# blades_v40.net
KiCad netlist of a schematic drawn in EAGLE
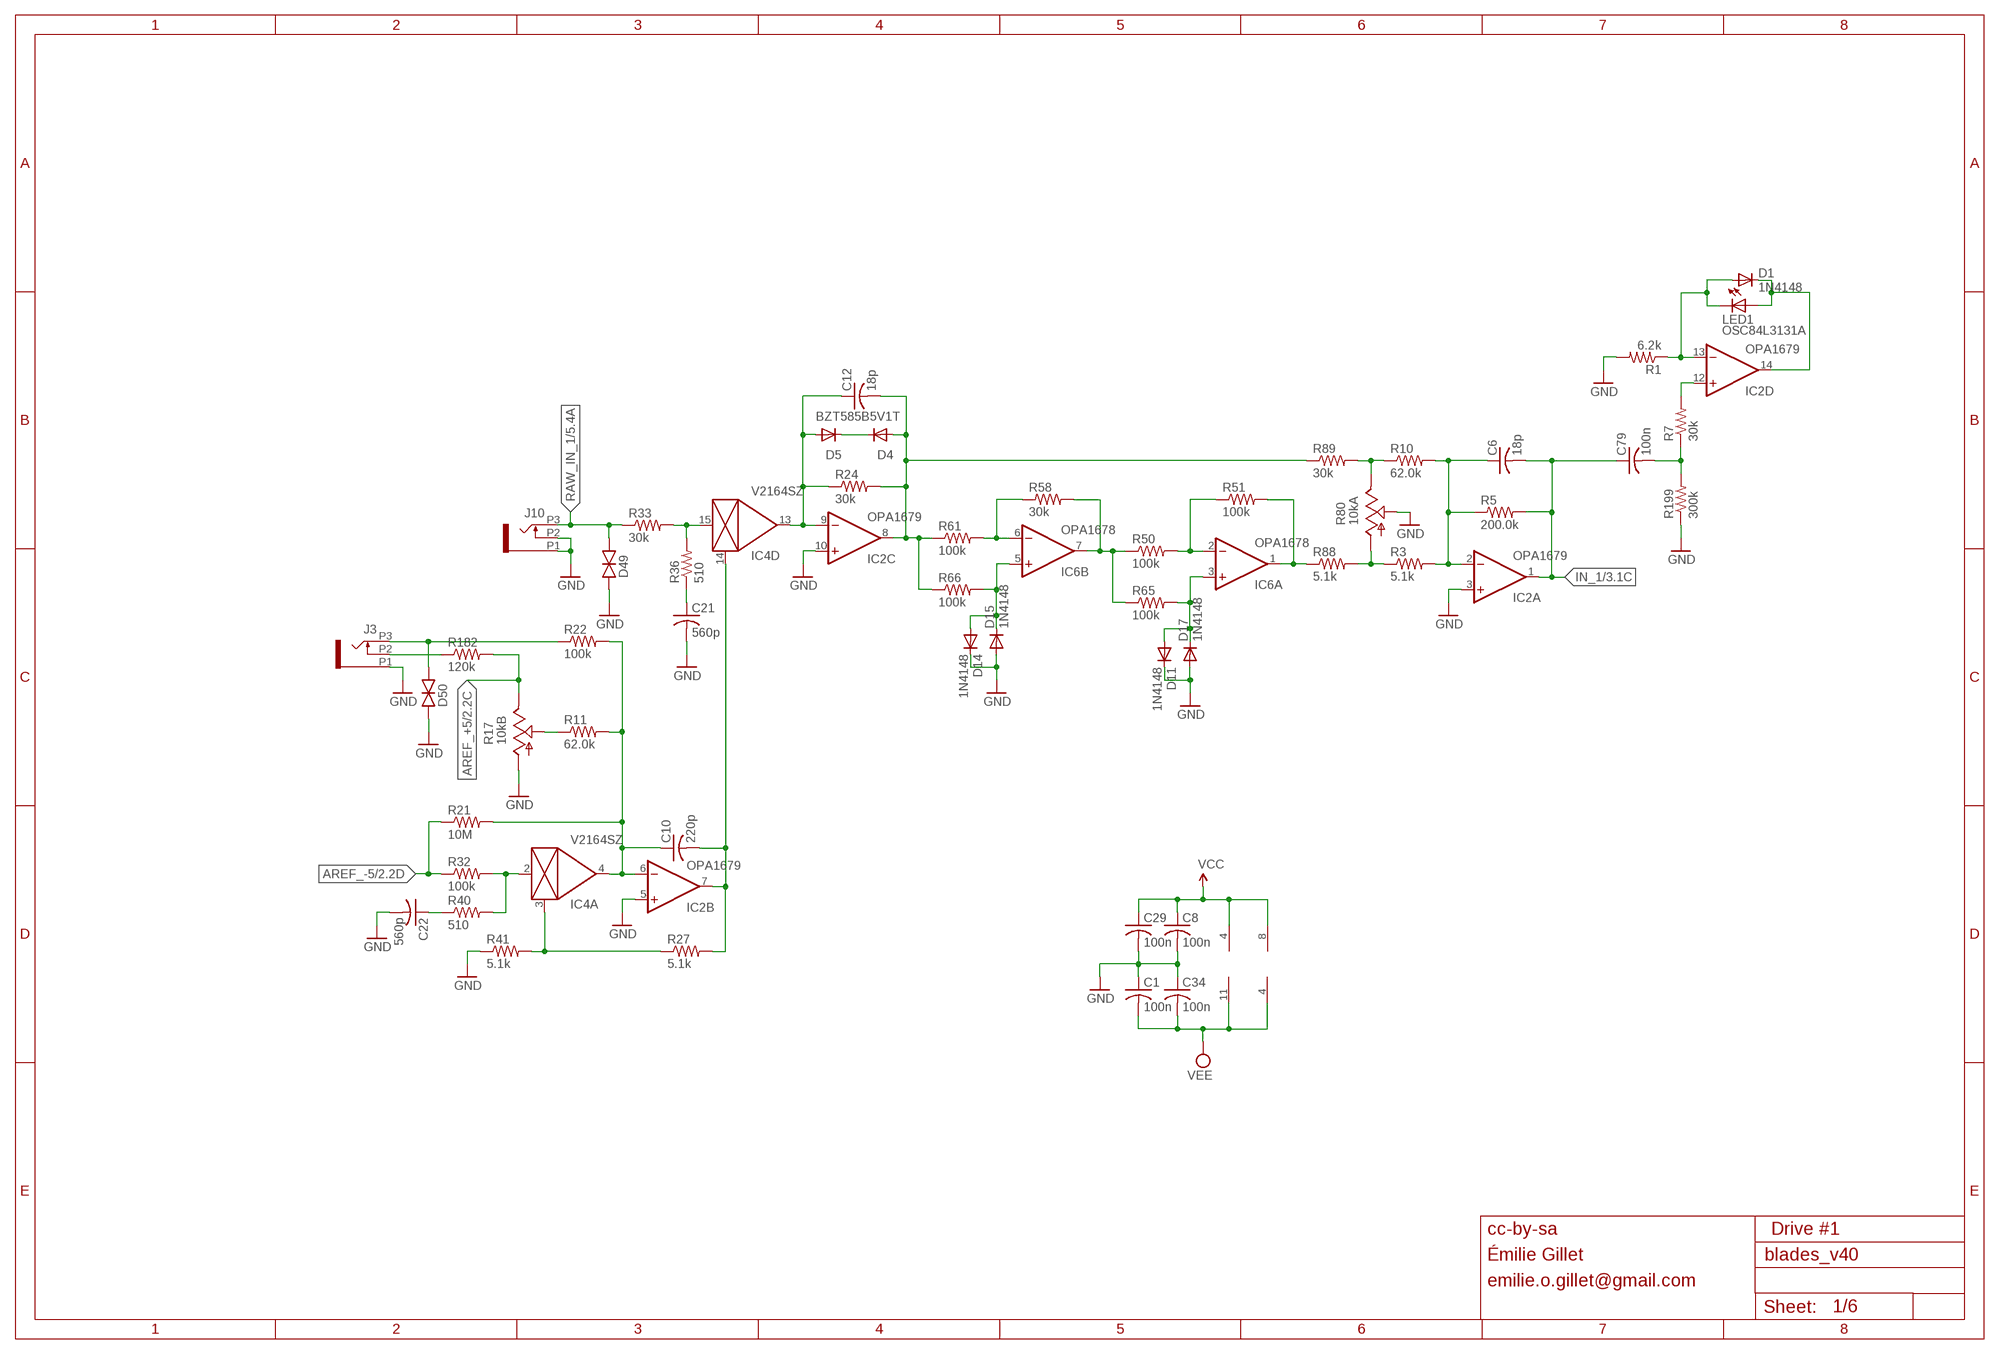
[diagram p0: schematic, sheet 1]
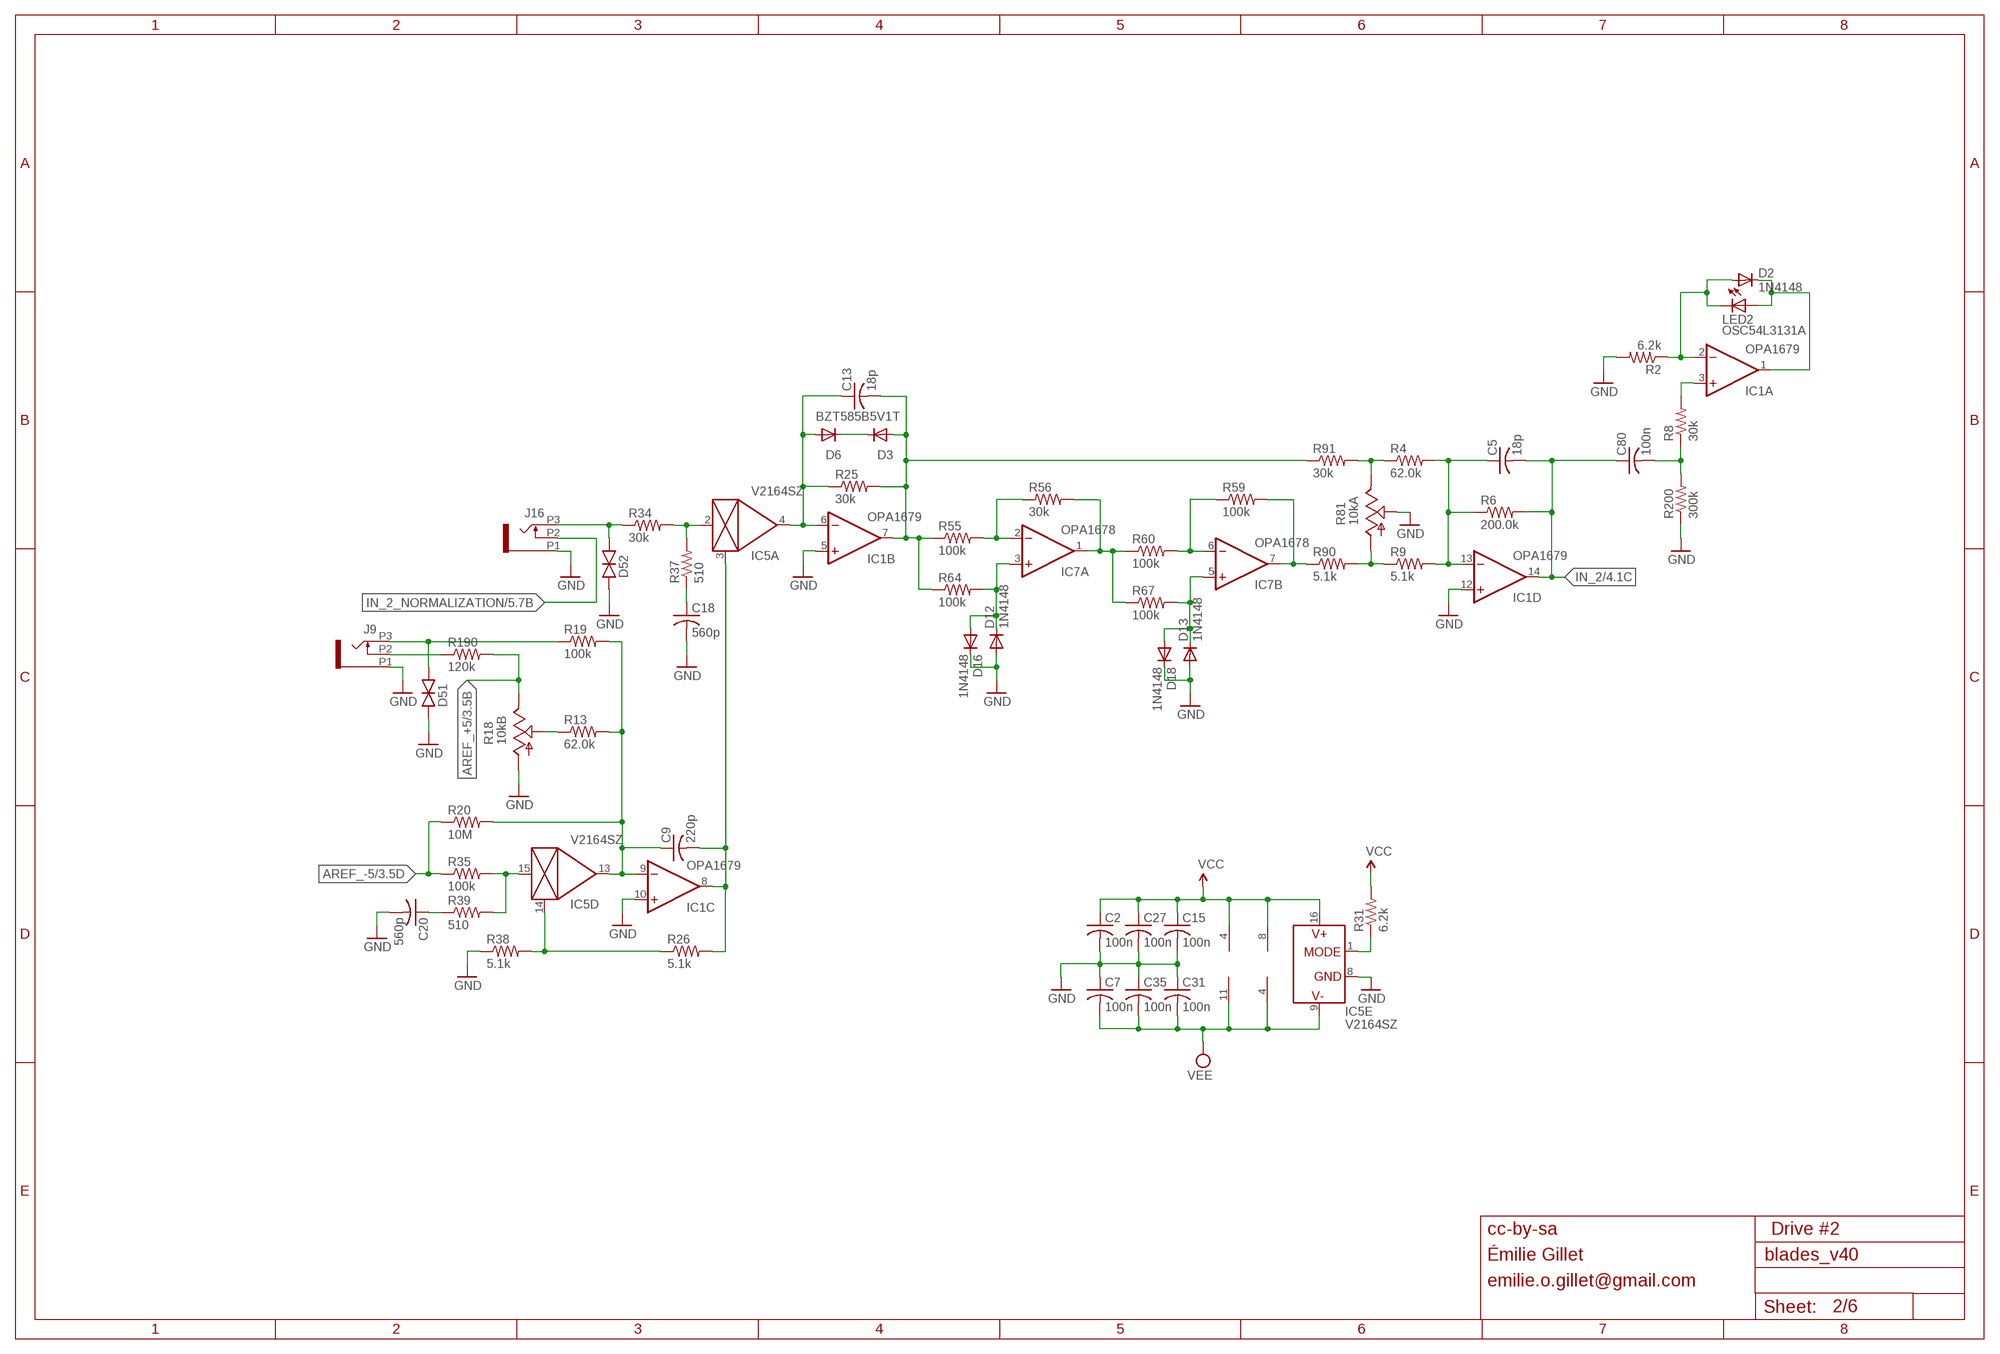
[diagram p1: schematic, sheet 2]
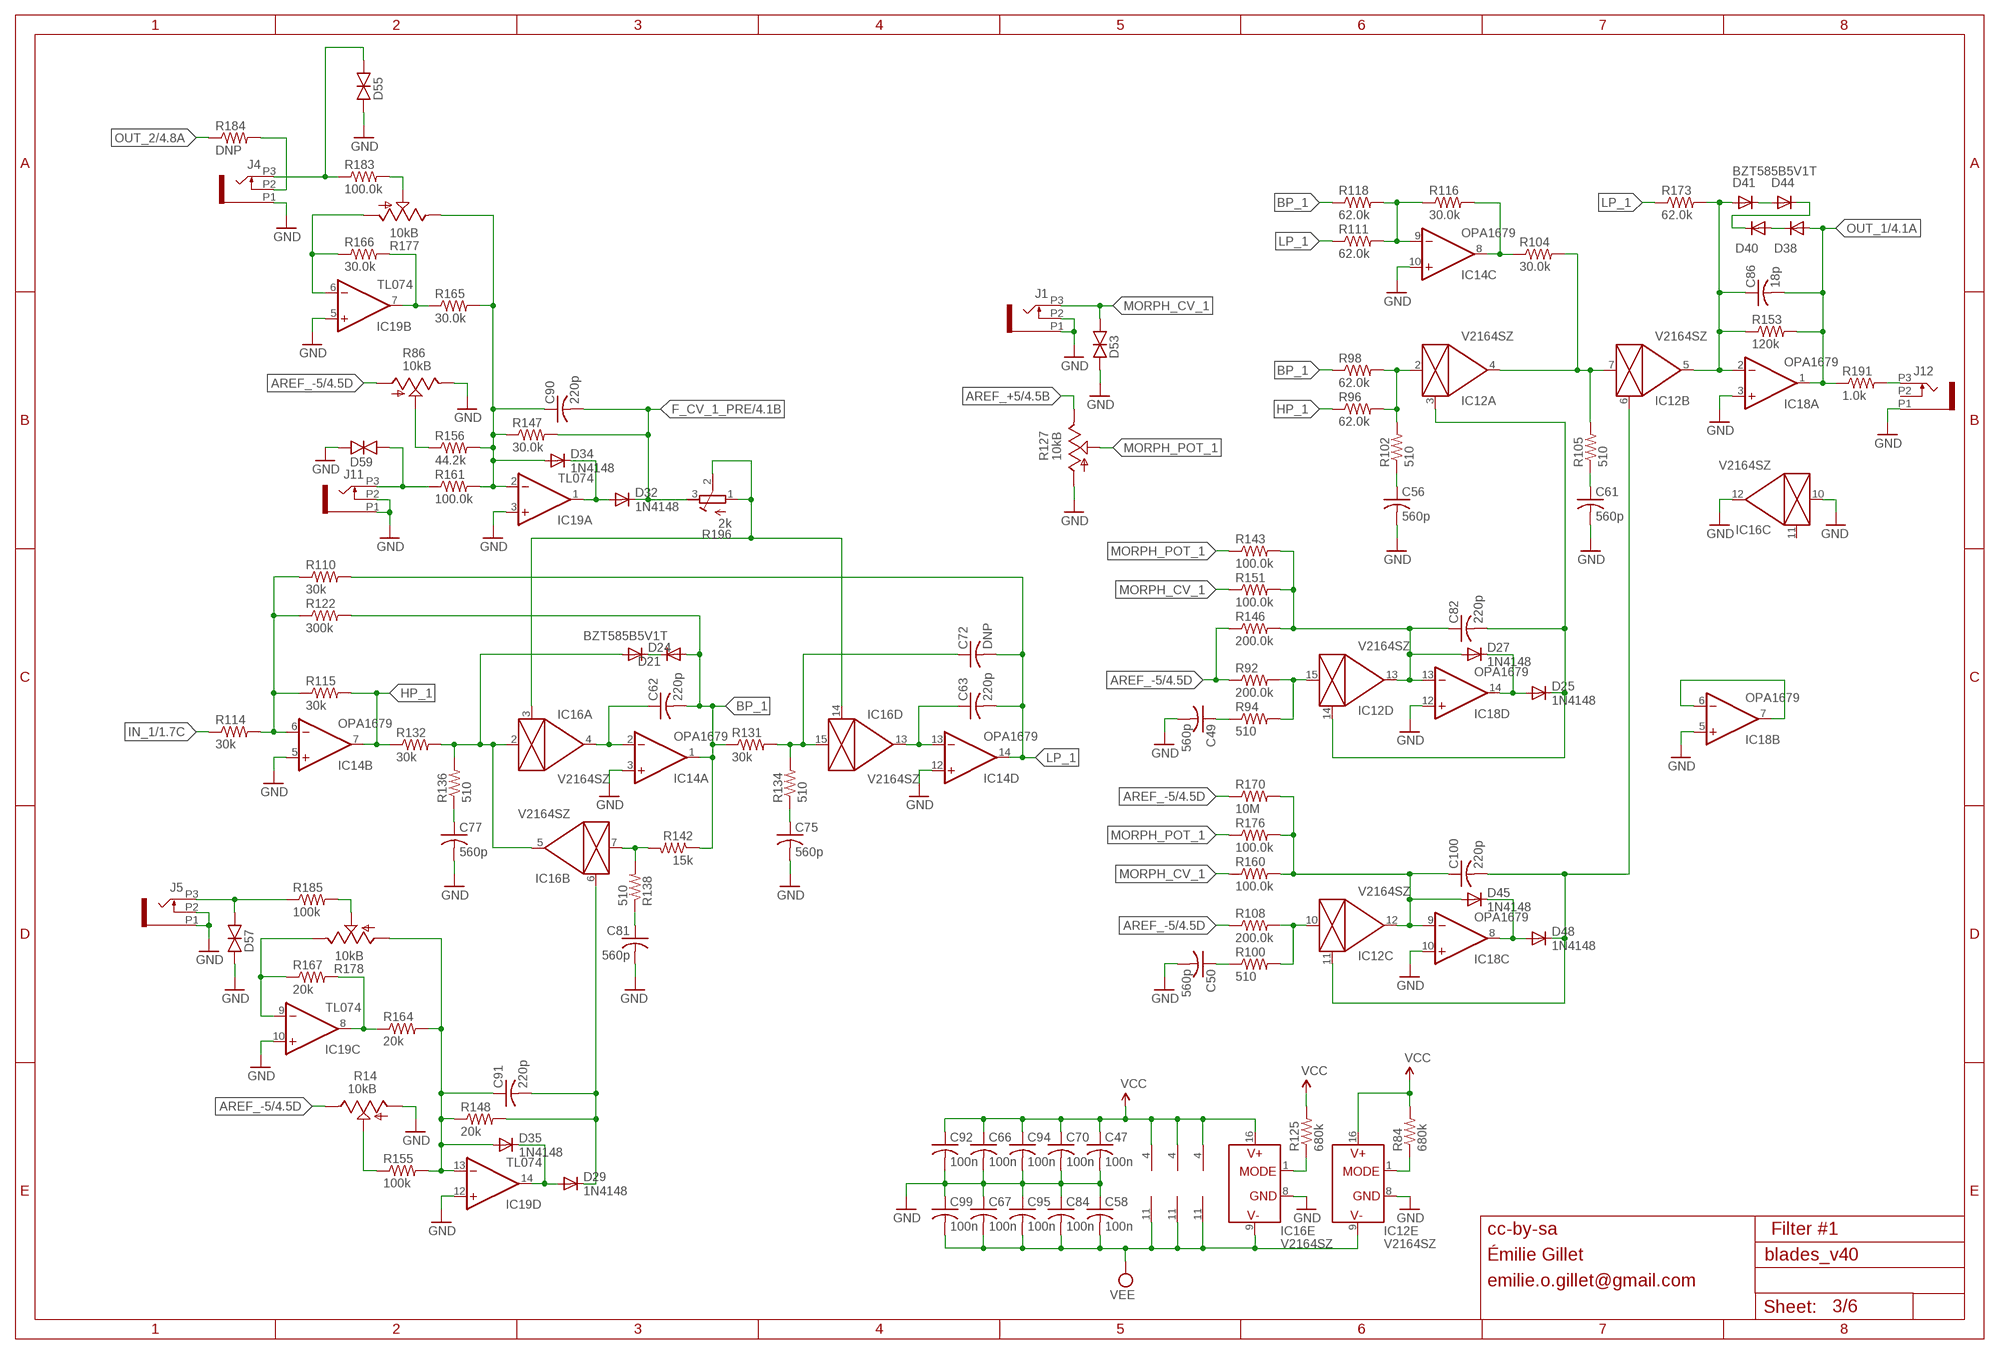
[diagram p2: schematic, sheet 3]
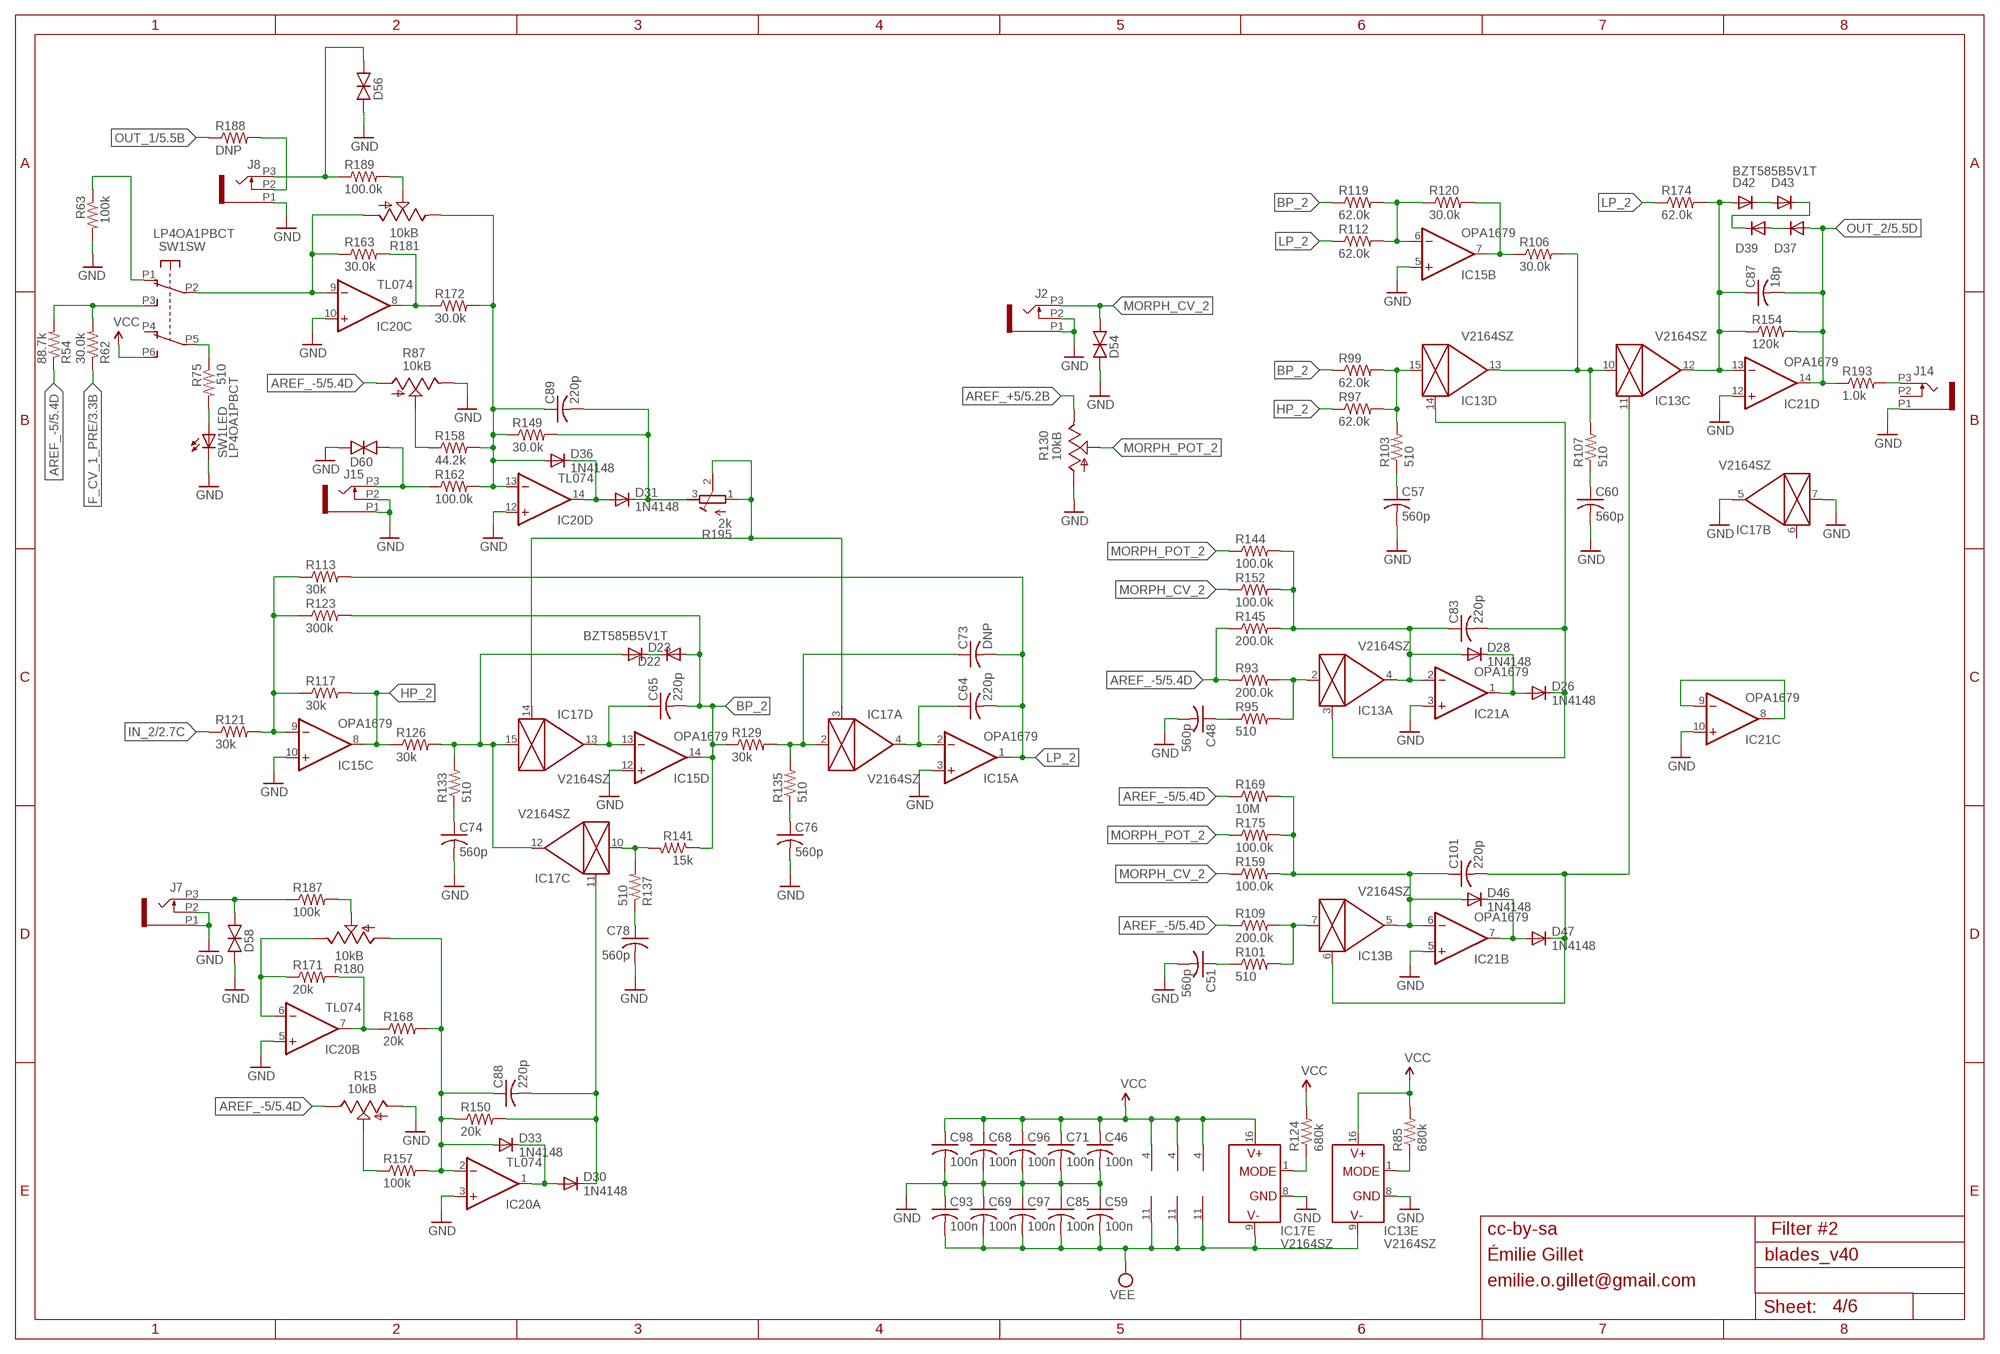
[diagram p3: schematic, sheet 4]
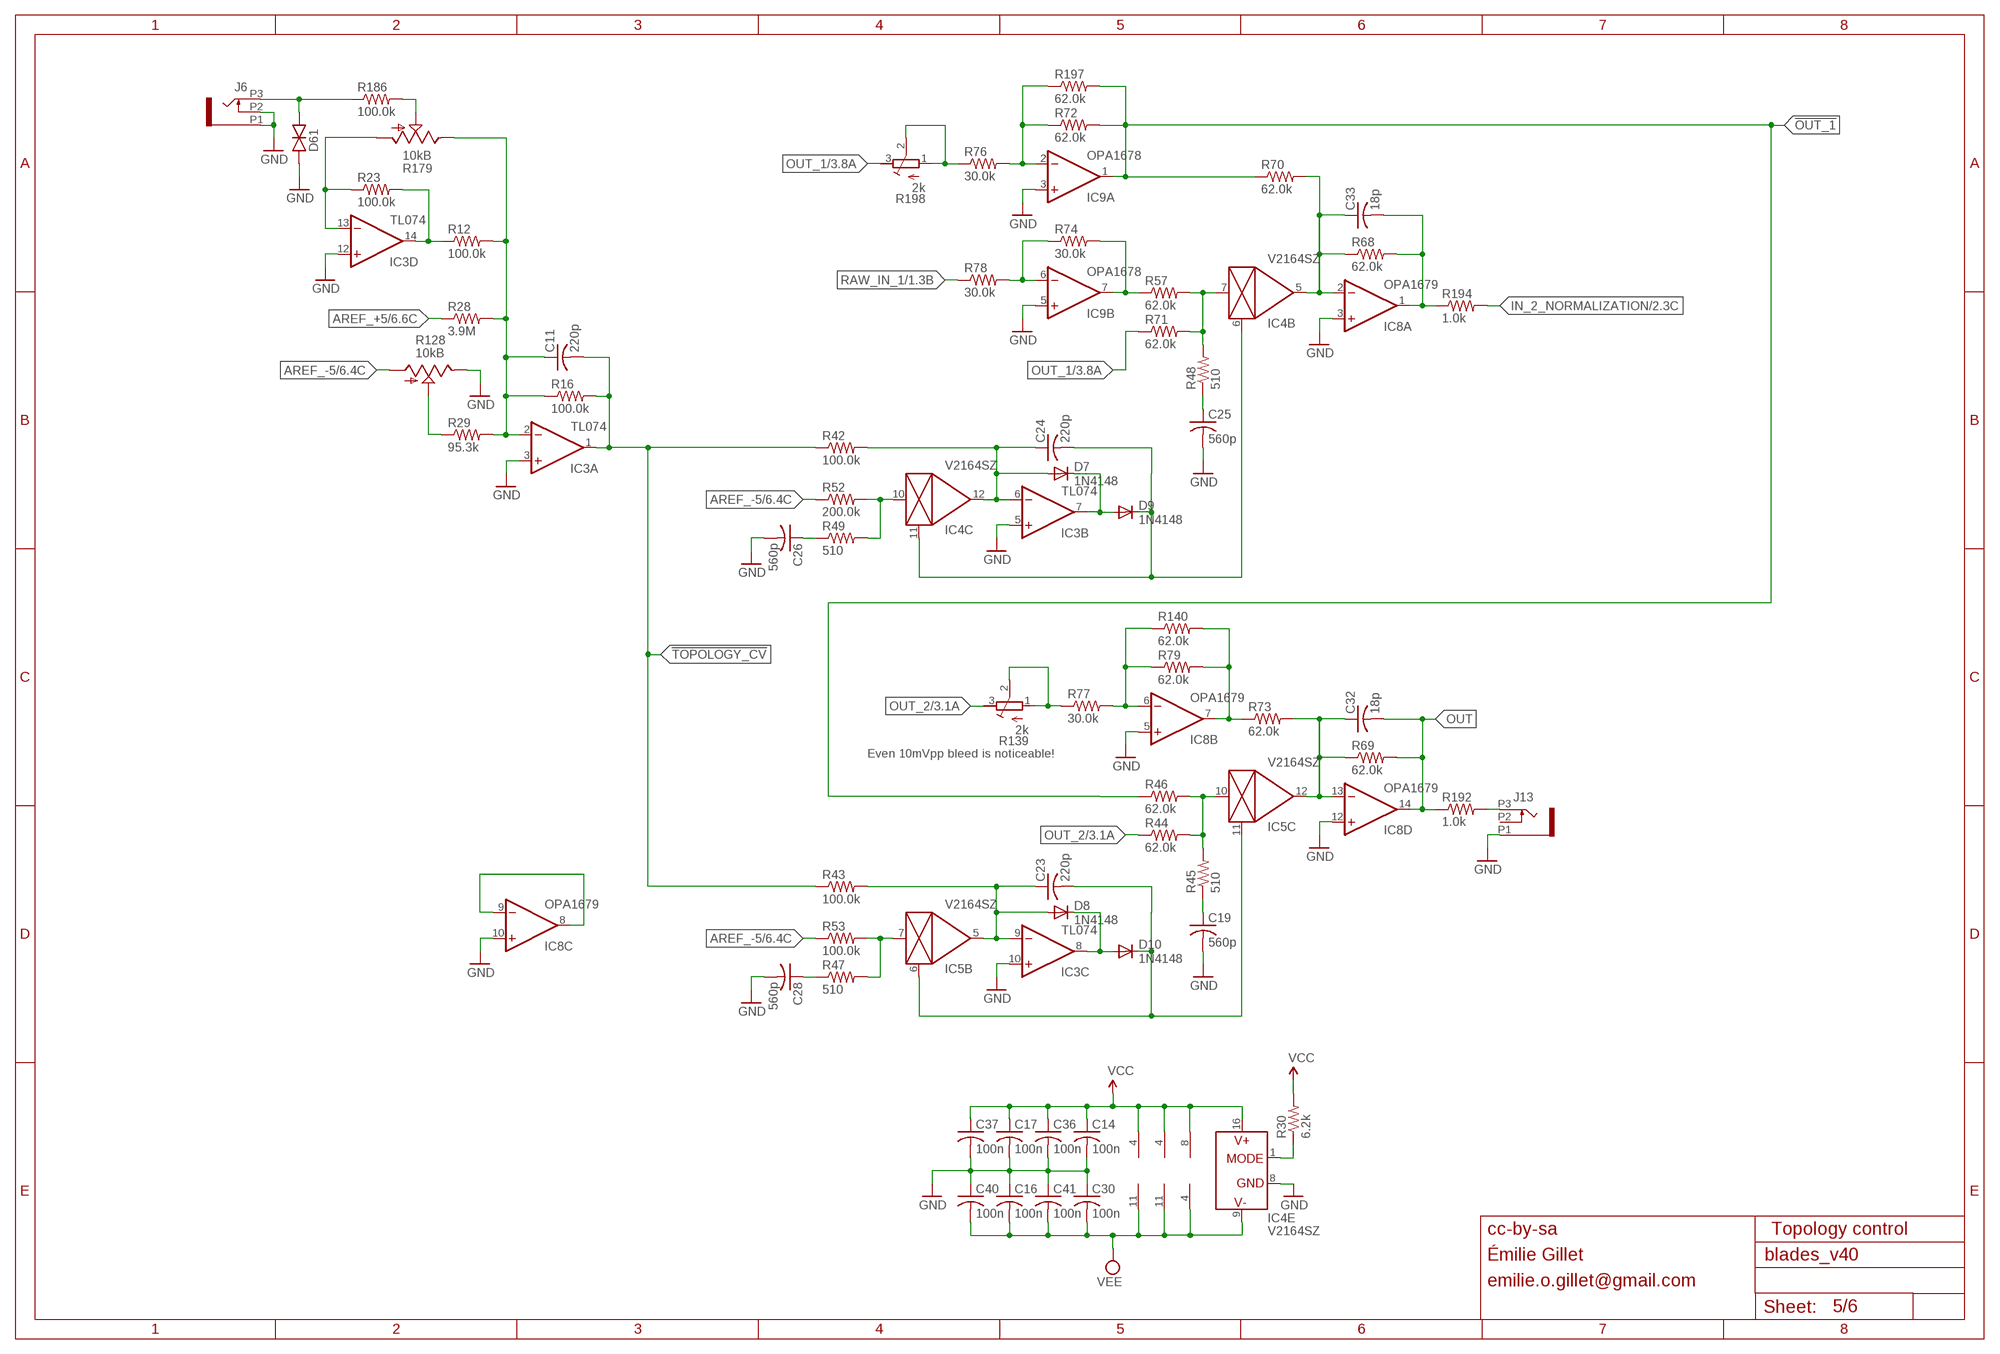
[diagram p4: schematic, sheet 5]
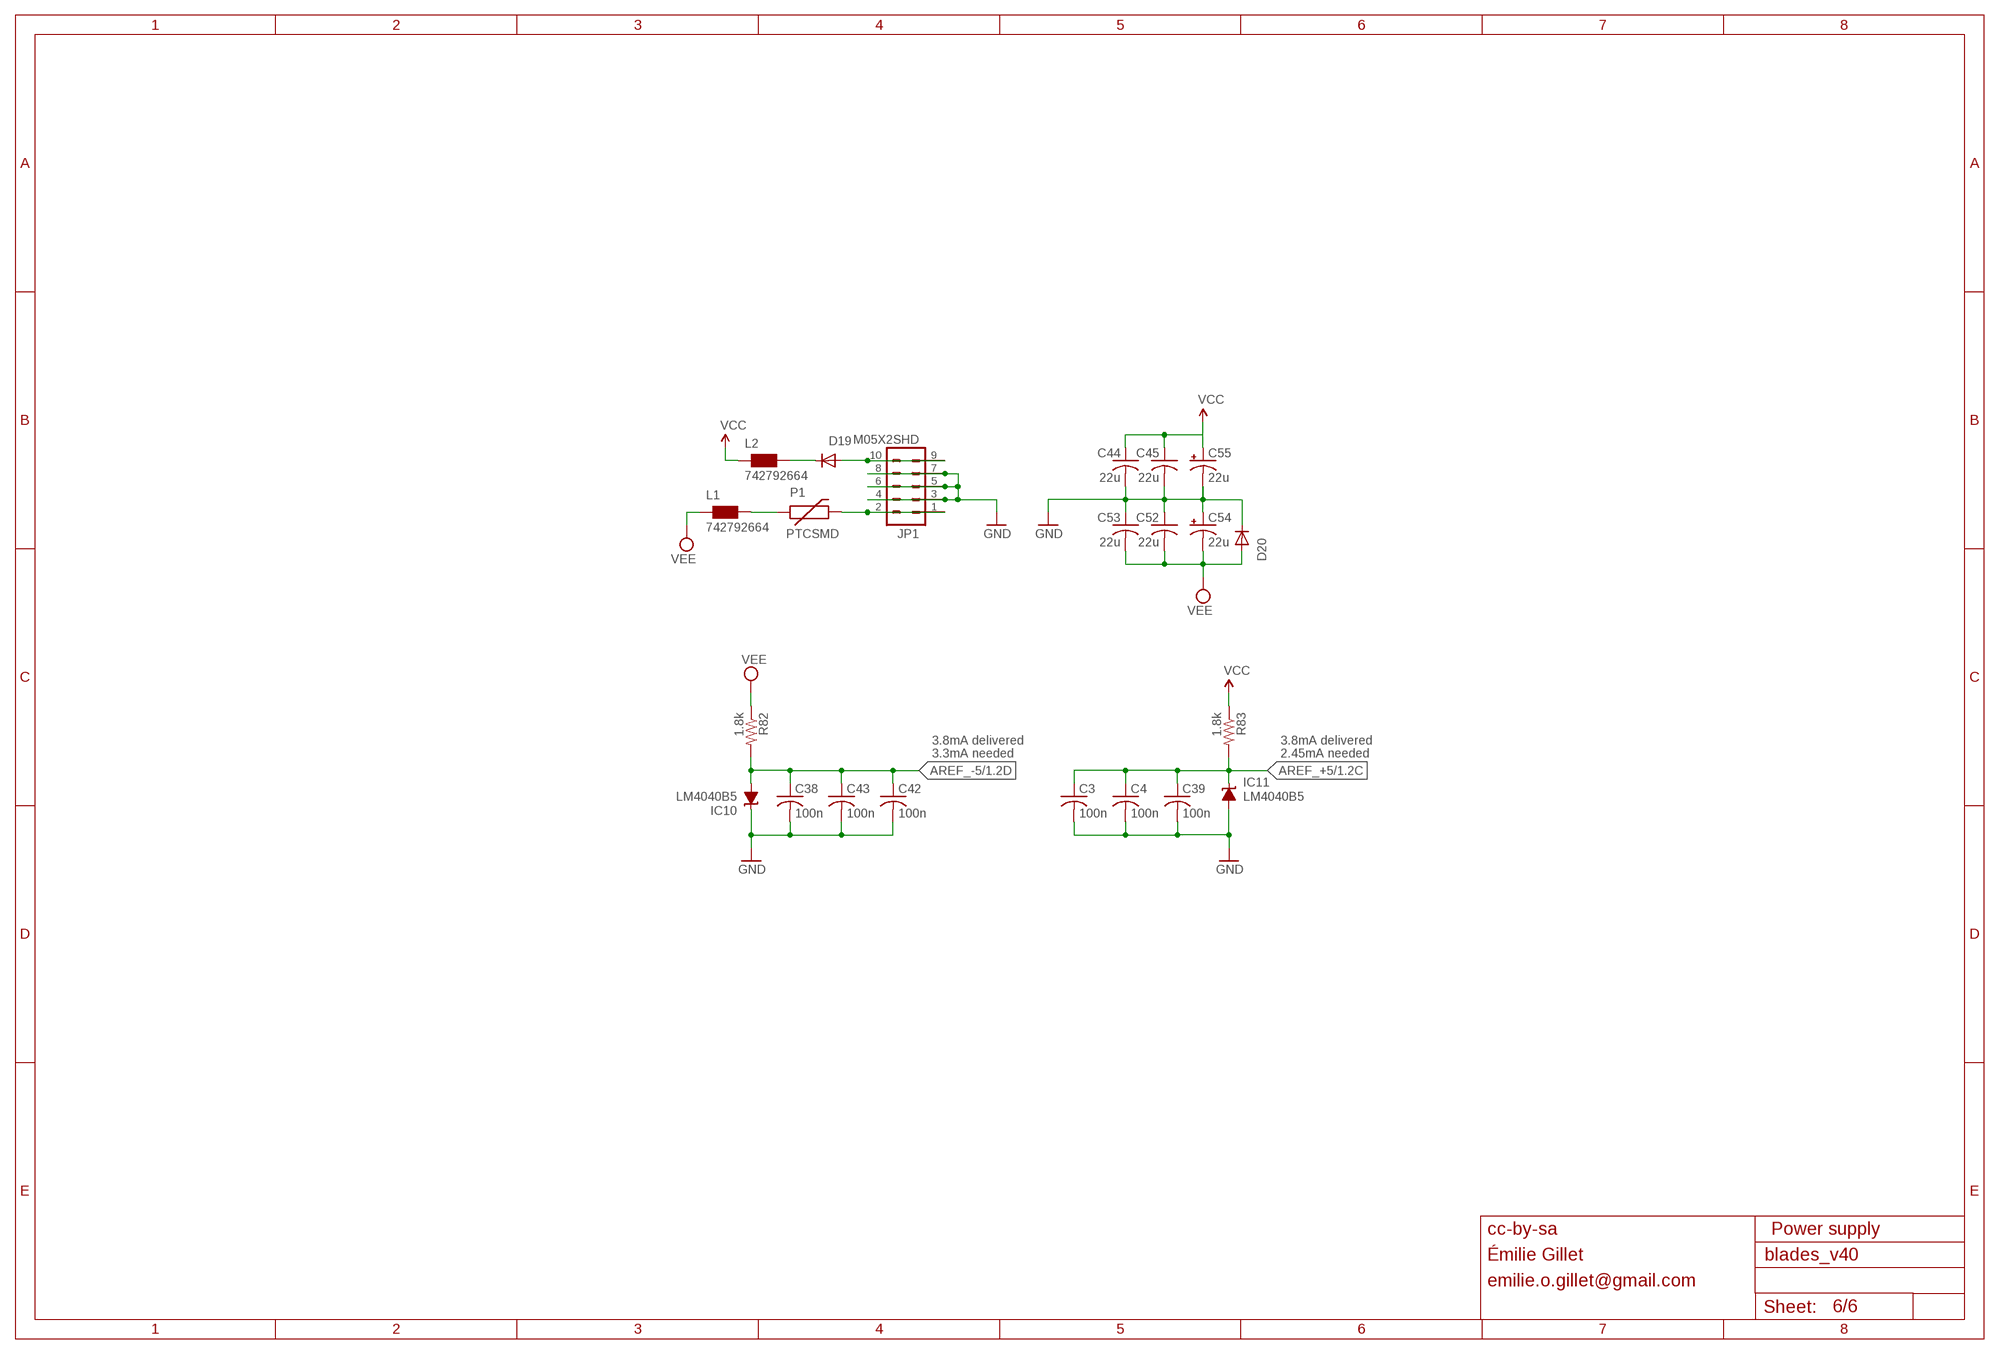
[diagram p5: schematic, sheet 6]

(export (version "E")
  (design (tool "Eeschema 10.0.6"))
  (components
    (comp (ref "C47")
      (value "100n")
      (footprint "eagle-import:C0402")
      (libsource (lib "eagle-import") (part "C-USC0402"))
    )
    (comp (ref "C49")
      (value "560p")
      (footprint "eagle-import:C0402")
      (libsource (lib "eagle-import") (part "C-USC0402"))
    )
    (comp (ref "C50")
      (value "560p")
      (footprint "eagle-import:C0402")
      (libsource (lib "eagle-import") (part "C-USC0402"))
    )
    (comp (ref "C56")
      (value "560p")
      (footprint "eagle-import:C0402")
      (libsource (lib "eagle-import") (part "C-USC0402"))
    )
    (comp (ref "C58")
      (value "100n")
      (footprint "eagle-import:C0402")
      (libsource (lib "eagle-import") (part "C-USC0402"))
    )
    (comp (ref "C61")
      (value "560p")
      (footprint "eagle-import:C0402")
      (libsource (lib "eagle-import") (part "C-USC0402"))
    )
    (comp (ref "C62")
      (value "220p")
      (footprint "eagle-import:C0402")
      (libsource (lib "eagle-import") (part "C-USC0402"))
    )
    (comp (ref "C63")
      (value "220p")
      (footprint "eagle-import:C0402")
      (libsource (lib "eagle-import") (part "C-USC0402"))
    )
    (comp (ref "C66")
      (value "100n")
      (footprint "eagle-import:C0402")
      (libsource (lib "eagle-import") (part "C-USC0402"))
    )
    (comp (ref "C67")
      (value "100n")
      (footprint "eagle-import:C0402")
      (libsource (lib "eagle-import") (part "C-USC0402"))
    )
    (comp (ref "C70")
      (value "100n")
      (footprint "eagle-import:C0402")
      (libsource (lib "eagle-import") (part "C-USC0402"))
    )
    (comp (ref "C72")
      (value "DNP")
      (footprint "eagle-import:C0402")
      (libsource (lib "eagle-import") (part "C-USC0402"))
    )
    (comp (ref "C75")
      (value "560p")
      (footprint "eagle-import:C0402")
      (libsource (lib "eagle-import") (part "C-USC0402"))
    )
    (comp (ref "C77")
      (value "560p")
      (footprint "eagle-import:C0402")
      (libsource (lib "eagle-import") (part "C-USC0402"))
    )
    (comp (ref "C81")
      (value "560p")
      (footprint "eagle-import:C0402")
      (libsource (lib "eagle-import") (part "C-USC0402"))
    )
    (comp (ref "C82")
      (value "220p")
      (footprint "eagle-import:C0402")
      (libsource (lib "eagle-import") (part "C-USC0402"))
    )
    (comp (ref "C84")
      (value "100n")
      (footprint "eagle-import:C0402")
      (libsource (lib "eagle-import") (part "C-USC0402"))
    )
    (comp (ref "C86")
      (value "18p")
      (footprint "eagle-import:C0402")
      (libsource (lib "eagle-import") (part "C-USC0402"))
    )
    (comp (ref "C90")
      (value "220p")
      (footprint "eagle-import:C0402")
      (libsource (lib "eagle-import") (part "C-USC0402"))
    )
    (comp (ref "C91")
      (value "220p")
      (footprint "eagle-import:C0402")
      (libsource (lib "eagle-import") (part "C-USC0402"))
    )
    (comp (ref "C92")
      (value "100n")
      (footprint "eagle-import:C0402")
      (libsource (lib "eagle-import") (part "C-USC0402"))
    )
    (comp (ref "C94")
      (value "100n")
      (footprint "eagle-import:C0402")
      (libsource (lib "eagle-import") (part "C-USC0402"))
    )
    (comp (ref "C95")
      (value "100n")
      (footprint "eagle-import:C0402")
      (libsource (lib "eagle-import") (part "C-USC0402"))
    )
    (comp (ref "C99")
      (value "100n")
      (footprint "eagle-import:C0402")
      (libsource (lib "eagle-import") (part "C-USC0402"))
    )
    (comp (ref "C100")
      (value "220p")
      (footprint "eagle-import:C0402")
      (libsource (lib "eagle-import") (part "C-USC0402"))
    )
    (comp (ref "D21")
      (value "BZT585B5V1T")
      (footprint "eagle-import:SOD523")
      (libsource (lib "eagle-import") (part "DIODE-SOD523"))
    )
    (comp (ref "D24")
      (value "BZT585B5V1T")
      (footprint "eagle-import:SOD523")
      (libsource (lib "eagle-import") (part "DIODE-SOD523"))
    )
    (comp (ref "D25")
      (value "1N4148")
      (footprint "eagle-import:SOD523")
      (libsource (lib "eagle-import") (part "DIODE-SOD523"))
    )
    (comp (ref "D27")
      (value "1N4148")
      (footprint "eagle-import:SOD523")
      (libsource (lib "eagle-import") (part "DIODE-SOD523"))
    )
    (comp (ref "D29")
      (value "1N4148")
      (footprint "eagle-import:SOD523")
      (libsource (lib "eagle-import") (part "DIODE-SOD523"))
    )
    (comp (ref "D32")
      (value "1N4148")
      (footprint "eagle-import:SOD523")
      (libsource (lib "eagle-import") (part "DIODE-SOD523"))
    )
    (comp (ref "D34")
      (value "1N4148")
      (footprint "eagle-import:SOD523")
      (libsource (lib "eagle-import") (part "DIODE-SOD523"))
    )
    (comp (ref "D35")
      (value "1N4148")
      (footprint "eagle-import:SOD523")
      (libsource (lib "eagle-import") (part "DIODE-SOD523"))
    )
    (comp (ref "D38")
      (value "BZT585B5V1T")
      (footprint "eagle-import:SOD523")
      (libsource (lib "eagle-import") (part "DIODE-SOD523"))
    )
    (comp (ref "D40")
      (value "BZT585B5V1T")
      (footprint "eagle-import:SOD523")
      (libsource (lib "eagle-import") (part "DIODE-SOD523"))
    )
    (comp (ref "D41")
      (value "BZT585B5V1T")
      (footprint "eagle-import:SOD523")
      (libsource (lib "eagle-import") (part "DIODE-SOD523"))
    )
    (comp (ref "D44")
      (value "BZT585B5V1T")
      (footprint "eagle-import:SOD523")
      (libsource (lib "eagle-import") (part "DIODE-SOD523"))
    )
    (comp (ref "D45")
      (value "1N4148")
      (footprint "eagle-import:SOD523")
      (libsource (lib "eagle-import") (part "DIODE-SOD523"))
    )
    (comp (ref "D48")
      (value "1N4148")
      (footprint "eagle-import:SOD523")
      (libsource (lib "eagle-import") (part "DIODE-SOD523"))
    )
    (comp (ref "D53")
      (value "TVS")
      (footprint "eagle-import:0603")
      (libsource (lib "eagle-import") (part "TVS"))
    )
    (comp (ref "D55")
      (value "TVS")
      (footprint "eagle-import:0603")
      (libsource (lib "eagle-import") (part "TVS"))
    )
    (comp (ref "D57")
      (value "TVS")
      (footprint "eagle-import:0603")
      (libsource (lib "eagle-import") (part "TVS"))
    )
    (comp (ref "D59")
      (value "TVS")
      (footprint "eagle-import:0603")
      (libsource (lib "eagle-import") (part "TVS"))
    )
    (comp (ref "IC12")
      (value "V2164SZ")
      (footprint "eagle-import:SOIC16N")
      (libsource (lib "eagle-import") (part "SSM2164S"))
    )
    (comp (ref "IC14")
      (value "OPA1679")
      (footprint "eagle-import:TSSOP14_065")
      (libsource (lib "eagle-import") (part "OPA1679PW"))
    )
    (comp (ref "IC16")
      (value "V2164SZ")
      (footprint "eagle-import:SOIC16N")
      (libsource (lib "eagle-import") (part "SSM2164S"))
    )
    (comp (ref "IC18")
      (value "OPA1679")
      (footprint "eagle-import:TSSOP14_065")
      (libsource (lib "eagle-import") (part "OPA1679PW"))
    )
    (comp (ref "IC19")
      (value "TL074")
      (footprint "eagle-import:TSSOP14_065")
      (libsource (lib "eagle-import") (part "TL074PW"))
    )
    (comp (ref "J1")
      (value "PJ301_THONKICONNTME")
      (footprint "eagle-import:WQP_PJ_301M_TME")
      (libsource (lib "eagle-import") (part "PJ301_THONKICONNTME"))
    )
    (comp (ref "J4")
      (value "PJ301_THONKICONNTME")
      (footprint "eagle-import:WQP_PJ_301M_TME")
      (libsource (lib "eagle-import") (part "PJ301_THONKICONNTME"))
    )
    (comp (ref "J5")
      (value "PJ301_THONKICONNTME")
      (footprint "eagle-import:WQP_PJ_301M_TME")
      (libsource (lib "eagle-import") (part "PJ301_THONKICONNTME"))
    )
    (comp (ref "J11")
      (value "PJ301_THONKICONNTME")
      (footprint "eagle-import:WQP_PJ_301M_TME")
      (libsource (lib "eagle-import") (part "PJ301_THONKICONNTME"))
    )
    (comp (ref "J12")
      (value "PJ301_THONKICONNTME")
      (footprint "eagle-import:WQP_PJ_301M_TME")
      (libsource (lib "eagle-import") (part "PJ301_THONKICONNTME"))
    )
    (comp (ref "R14")
      (value "10kB")
      (footprint "eagle-import:ALPS_POT_VERTICAL_PS")
      (libsource (lib "eagle-import") (part "pot-alps_POT_USVERTICAL_PS"))
    )
    (comp (ref "R84")
      (value "680k")
      (footprint "eagle-import:R0402")
      (libsource (lib "eagle-import") (part "R-US_R0402"))
    )
    (comp (ref "R86")
      (value "10kB")
      (footprint "eagle-import:ALPS_POT_VERTICAL_PS")
      (libsource (lib "eagle-import") (part "pot-alps_POT_USVERTICAL_PS"))
    )
    (comp (ref "R92")
      (value "200.0k")
      (footprint "eagle-import:R0402")
      (libsource (lib "eagle-import") (part "R-US_R0402"))
    )
    (comp (ref "R94")
      (value "510")
      (footprint "eagle-import:R0402")
      (libsource (lib "eagle-import") (part "R-US_R0402"))
    )
    (comp (ref "R96")
      (value "62.0k")
      (footprint "eagle-import:R0402")
      (libsource (lib "eagle-import") (part "R-US_R0402"))
    )
    (comp (ref "R98")
      (value "62.0k")
      (footprint "eagle-import:R0402")
      (libsource (lib "eagle-import") (part "R-US_R0402"))
    )
    (comp (ref "R100")
      (value "510")
      (footprint "eagle-import:R0402")
      (libsource (lib "eagle-import") (part "R-US_R0402"))
    )
    (comp (ref "R102")
      (value "510")
      (footprint "eagle-import:R0402")
      (libsource (lib "eagle-import") (part "R-US_R0402"))
    )
    (comp (ref "R104")
      (value "30.0k")
      (footprint "eagle-import:R0402")
      (libsource (lib "eagle-import") (part "R-US_R0402"))
    )
    (comp (ref "R105")
      (value "510")
      (footprint "eagle-import:R0402")
      (libsource (lib "eagle-import") (part "R-US_R0402"))
    )
    (comp (ref "R108")
      (value "200.0k")
      (footprint "eagle-import:R0402")
      (libsource (lib "eagle-import") (part "R-US_R0402"))
    )
    (comp (ref "R110")
      (value "30k")
      (footprint "eagle-import:R0402")
      (libsource (lib "eagle-import") (part "R-US_R0402"))
    )
    (comp (ref "R111")
      (value "62.0k")
      (footprint "eagle-import:R0402")
      (libsource (lib "eagle-import") (part "R-US_R0402"))
    )
    (comp (ref "R114")
      (value "30k")
      (footprint "eagle-import:R0402")
      (libsource (lib "eagle-import") (part "R-US_R0402"))
    )
    (comp (ref "R115")
      (value "30k")
      (footprint "eagle-import:R0402")
      (libsource (lib "eagle-import") (part "R-US_R0402"))
    )
    (comp (ref "R116")
      (value "30.0k")
      (footprint "eagle-import:R0402")
      (libsource (lib "eagle-import") (part "R-US_R0402"))
    )
    (comp (ref "R118")
      (value "62.0k")
      (footprint "eagle-import:R0402")
      (libsource (lib "eagle-import") (part "R-US_R0402"))
    )
    (comp (ref "R122")
      (value "300k")
      (footprint "eagle-import:R0402")
      (libsource (lib "eagle-import") (part "R-US_R0402"))
    )
    (comp (ref "R125")
      (value "680k")
      (footprint "eagle-import:R0402")
      (libsource (lib "eagle-import") (part "R-US_R0402"))
    )
    (comp (ref "R127")
      (value "10kB")
      (footprint "eagle-import:ALPS_POT_VERTICAL_PS")
      (libsource (lib "eagle-import") (part "pot-alps_POT_USVERTICAL_PS"))
    )
    (comp (ref "R131")
      (value "30k")
      (footprint "eagle-import:R0402")
      (libsource (lib "eagle-import") (part "R-US_R0402"))
    )
    (comp (ref "R132")
      (value "30k")
      (footprint "eagle-import:R0402")
      (libsource (lib "eagle-import") (part "R-US_R0402"))
    )
    (comp (ref "R134")
      (value "510")
      (footprint "eagle-import:R0402")
      (libsource (lib "eagle-import") (part "R-US_R0402"))
    )
    (comp (ref "R136")
      (value "510")
      (footprint "eagle-import:R0402")
      (libsource (lib "eagle-import") (part "R-US_R0402"))
    )
    (comp (ref "R138")
      (value "510")
      (footprint "eagle-import:R0402")
      (libsource (lib "eagle-import") (part "R-US_R0402"))
    )
    (comp (ref "R142")
      (value "15k")
      (footprint "eagle-import:R0402")
      (libsource (lib "eagle-import") (part "R-US_R0402"))
    )
    (comp (ref "R143")
      (value "100.0k")
      (footprint "eagle-import:R0402")
      (libsource (lib "eagle-import") (part "R-US_R0402"))
    )
    (comp (ref "R146")
      (value "200.0k")
      (footprint "eagle-import:R0402")
      (libsource (lib "eagle-import") (part "R-US_R0402"))
    )
    (comp (ref "R147")
      (value "30.0k")
      (footprint "eagle-import:R0402")
      (libsource (lib "eagle-import") (part "R-US_R0402"))
    )
    (comp (ref "R148")
      (value "20k")
      (footprint "eagle-import:R0402")
      (libsource (lib "eagle-import") (part "R-US_R0402"))
    )
    (comp (ref "R151")
      (value "100.0k")
      (footprint "eagle-import:R0402")
      (libsource (lib "eagle-import") (part "R-US_R0402"))
    )
    (comp (ref "R153")
      (value "120k")
      (footprint "eagle-import:R0402")
      (libsource (lib "eagle-import") (part "R-US_R0402"))
    )
    (comp (ref "R155")
      (value "100k")
      (footprint "eagle-import:R0402")
      (libsource (lib "eagle-import") (part "R-US_R0402"))
    )
    (comp (ref "R156")
      (value "44.2k")
      (footprint "eagle-import:R0402")
      (libsource (lib "eagle-import") (part "R-US_R0402"))
    )
    (comp (ref "R160")
      (value "100.0k")
      (footprint "eagle-import:R0402")
      (libsource (lib "eagle-import") (part "R-US_R0402"))
    )
    (comp (ref "R161")
      (value "100.0k")
      (footprint "eagle-import:R0402")
      (libsource (lib "eagle-import") (part "R-US_R0402"))
    )
    (comp (ref "R164")
      (value "20k")
      (footprint "eagle-import:R0402")
      (libsource (lib "eagle-import") (part "R-US_R0402"))
    )
    (comp (ref "R165")
      (value "30.0k")
      (footprint "eagle-import:R0402")
      (libsource (lib "eagle-import") (part "R-US_R0402"))
    )
    (comp (ref "R166")
      (value "30.0k")
      (footprint "eagle-import:R0402")
      (libsource (lib "eagle-import") (part "R-US_R0402"))
    )
    (comp (ref "R167")
      (value "20k")
      (footprint "eagle-import:R0402")
      (libsource (lib "eagle-import") (part "R-US_R0402"))
    )
    (comp (ref "R170")
      (value "10M")
      (footprint "eagle-import:R0402")
      (libsource (lib "eagle-import") (part "R-US_R0402"))
    )
    (comp (ref "R173")
      (value "62.0k")
      (footprint "eagle-import:R0402")
      (libsource (lib "eagle-import") (part "R-US_R0402"))
    )
    (comp (ref "R176")
      (value "100.0k")
      (footprint "eagle-import:R0402")
      (libsource (lib "eagle-import") (part "R-US_R0402"))
    )
    (comp (ref "R177")
      (value "10kB")
      (footprint "eagle-import:ALPS_POT_NARROW")
      (libsource (lib "eagle-import") (part "POT_USVERTICAL_NARROW"))
    )
    (comp (ref "R178")
      (value "10kB")
      (footprint "eagle-import:ALPS_POT_NARROW")
      (libsource (lib "eagle-import") (part "POT_USVERTICAL_NARROW"))
    )
    (comp (ref "R183")
      (value "100.0k")
      (footprint "eagle-import:R0402")
      (libsource (lib "eagle-import") (part "R-US_R0402"))
    )
    (comp (ref "R184")
      (value "DNP")
      (footprint "eagle-import:R0603")
      (libsource (lib "eagle-import") (part "R-US_R0603"))
    )
    (comp (ref "R185")
      (value "100k")
      (footprint "eagle-import:R0402")
      (libsource (lib "eagle-import") (part "R-US_R0402"))
    )
    (comp (ref "R191")
      (value "1.0k")
      (footprint "eagle-import:R0603")
      (libsource (lib "eagle-import") (part "R-US_R0603"))
    )
    (comp (ref "R196")
      (value "2k")
      (footprint "eagle-import:RTRIM3296W")
      (libsource (lib "eagle-import") (part "R-TRIMM3296W"))
    )
    (comp (ref "C2")
      (value "100n")
      (footprint "eagle-import:C0402")
      (libsource (lib "eagle-import") (part "C-USC0402"))
    )
    (comp (ref "C5")
      (value "18p")
      (footprint "eagle-import:C0402")
      (libsource (lib "eagle-import") (part "C-USC0402"))
    )
    (comp (ref "C7")
      (value "100n")
      (footprint "eagle-import:C0402")
      (libsource (lib "eagle-import") (part "C-USC0402"))
    )
    (comp (ref "C9")
      (value "220p")
      (footprint "eagle-import:C0402")
      (libsource (lib "eagle-import") (part "C-USC0402"))
    )
    (comp (ref "C13")
      (value "18p")
      (footprint "eagle-import:C0402")
      (libsource (lib "eagle-import") (part "C-USC0402"))
    )
    (comp (ref "C15")
      (value "100n")
      (footprint "eagle-import:C0402")
      (libsource (lib "eagle-import") (part "C-USC0402"))
    )
    (comp (ref "C18")
      (value "560p")
      (footprint "eagle-import:C0402")
      (libsource (lib "eagle-import") (part "C-USC0402"))
    )
    (comp (ref "C20")
      (value "560p")
      (footprint "eagle-import:C0402")
      (libsource (lib "eagle-import") (part "C-USC0402"))
    )
    (comp (ref "C27")
      (value "100n")
      (footprint "eagle-import:C0402")
      (libsource (lib "eagle-import") (part "C-USC0402"))
    )
    (comp (ref "C31")
      (value "100n")
      (footprint "eagle-import:C0402")
      (libsource (lib "eagle-import") (part "C-USC0402"))
    )
    (comp (ref "C35")
      (value "100n")
      (footprint "eagle-import:C0402")
      (libsource (lib "eagle-import") (part "C-USC0402"))
    )
    (comp (ref "C80")
      (value "100n")
      (footprint "eagle-import:C0402")
      (libsource (lib "eagle-import") (part "C-USC0402"))
    )
    (comp (ref "D2")
      (value "1N4148")
      (footprint "eagle-import:SOD523")
      (libsource (lib "eagle-import") (part "DIODE-SOD523"))
    )
    (comp (ref "D3")
      (value "BZT585B5V1T")
      (footprint "eagle-import:SOD523")
      (libsource (lib "eagle-import") (part "DIODE-SOD523"))
    )
    (comp (ref "D6")
      (value "BZT585B5V1T")
      (footprint "eagle-import:SOD523")
      (libsource (lib "eagle-import") (part "DIODE-SOD523"))
    )
    (comp (ref "D12")
      (value "1N4148")
      (footprint "eagle-import:SOD523")
      (libsource (lib "eagle-import") (part "DIODE-SOD523"))
    )
    (comp (ref "D13")
      (value "1N4148")
      (footprint "eagle-import:SOD523")
      (libsource (lib "eagle-import") (part "DIODE-SOD523"))
    )
    (comp (ref "D16")
      (value "1N4148")
      (footprint "eagle-import:SOD523")
      (libsource (lib "eagle-import") (part "DIODE-SOD523"))
    )
    (comp (ref "D18")
      (value "1N4148")
      (footprint "eagle-import:SOD523")
      (libsource (lib "eagle-import") (part "DIODE-SOD523"))
    )
    (comp (ref "D51")
      (value "TVS")
      (footprint "eagle-import:0603")
      (libsource (lib "eagle-import") (part "TVS"))
    )
    (comp (ref "D52")
      (value "TVS")
      (footprint "eagle-import:0603")
      (libsource (lib "eagle-import") (part "TVS"))
    )
    (comp (ref "IC1")
      (value "OPA1679")
      (footprint "eagle-import:TSSOP14_065")
      (libsource (lib "eagle-import") (part "OPA1679PW"))
    )
    (comp (ref "IC5")
      (value "V2164SZ")
      (footprint "eagle-import:SOIC16N")
      (libsource (lib "eagle-import") (part "SSM2164S"))
    )
    (comp (ref "IC7")
      (value "OPA1678")
      (footprint "eagle-import:VSSOP8")
      (libsource (lib "eagle-import") (part "OPA1678DGK"))
    )
    (comp (ref "J9")
      (value "PJ301_THONKICONNTME")
      (footprint "eagle-import:WQP_PJ_301M_TME")
      (libsource (lib "eagle-import") (part "PJ301_THONKICONNTME"))
    )
    (comp (ref "J16")
      (value "PJ301_THONKICONNTME")
      (footprint "eagle-import:WQP_PJ_301M_TME")
      (libsource (lib "eagle-import") (part "PJ301_THONKICONNTME"))
    )
    (comp (ref "LED2")
      (value "OSC54L3131A")
      (footprint "eagle-import:LED3MM")
      (libsource (lib "eagle-import") (part "LED3MM"))
    )
    (comp (ref "R2")
      (value "6.2k")
      (footprint "eagle-import:R0402")
      (libsource (lib "eagle-import") (part "R-US_R0402"))
    )
    (comp (ref "R4")
      (value "62.0k")
      (footprint "eagle-import:R0402")
      (libsource (lib "eagle-import") (part "R-US_R0402"))
    )
    (comp (ref "R6")
      (value "200.0k")
      (footprint "eagle-import:R0402")
      (libsource (lib "eagle-import") (part "R-US_R0402"))
    )
    (comp (ref "R8")
      (value "30k")
      (footprint "eagle-import:R0402")
      (libsource (lib "eagle-import") (part "R-US_R0402"))
    )
    (comp (ref "R9")
      (value "5.1k")
      (footprint "eagle-import:R0402")
      (libsource (lib "eagle-import") (part "R-US_R0402"))
    )
    (comp (ref "R13")
      (value "62.0k")
      (footprint "eagle-import:R0402")
      (libsource (lib "eagle-import") (part "R-US_R0402"))
    )
    (comp (ref "R18")
      (value "10kB")
      (footprint "eagle-import:ALPS_POT_VERTICAL_PS")
      (libsource (lib "eagle-import") (part "pot-alps_POT_USVERTICAL_PS"))
    )
    (comp (ref "R19")
      (value "100k")
      (footprint "eagle-import:R0402")
      (libsource (lib "eagle-import") (part "R-US_R0402"))
    )
    (comp (ref "R20")
      (value "10M")
      (footprint "eagle-import:R0402")
      (libsource (lib "eagle-import") (part "R-US_R0402"))
    )
    (comp (ref "R25")
      (value "30k")
      (footprint "eagle-import:R0402")
      (libsource (lib "eagle-import") (part "R-US_R0402"))
    )
    (comp (ref "R26")
      (value "5.1k")
      (footprint "eagle-import:R0402")
      (libsource (lib "eagle-import") (part "R-US_R0402"))
    )
    (comp (ref "R31")
      (value "6.2k")
      (footprint "eagle-import:R0402")
      (libsource (lib "eagle-import") (part "R-US_R0402"))
    )
    (comp (ref "R34")
      (value "30k")
      (footprint "eagle-import:R0402")
      (libsource (lib "eagle-import") (part "R-US_R0402"))
    )
    (comp (ref "R35")
      (value "100k")
      (footprint "eagle-import:R0402")
      (libsource (lib "eagle-import") (part "R-US_R0402"))
    )
    (comp (ref "R37")
      (value "510")
      (footprint "eagle-import:R0402")
      (libsource (lib "eagle-import") (part "R-US_R0402"))
    )
    (comp (ref "R38")
      (value "5.1k")
      (footprint "eagle-import:R0402")
      (libsource (lib "eagle-import") (part "R-US_R0402"))
    )
    (comp (ref "R39")
      (value "510")
      (footprint "eagle-import:R0402")
      (libsource (lib "eagle-import") (part "R-US_R0402"))
    )
    (comp (ref "R55")
      (value "100k")
      (footprint "eagle-import:R0402")
      (libsource (lib "eagle-import") (part "R-US_R0402"))
    )
    (comp (ref "R56")
      (value "30k")
      (footprint "eagle-import:R0402")
      (libsource (lib "eagle-import") (part "R-US_R0402"))
    )
    (comp (ref "R59")
      (value "100k")
      (footprint "eagle-import:R0402")
      (libsource (lib "eagle-import") (part "R-US_R0402"))
    )
    (comp (ref "R60")
      (value "100k")
      (footprint "eagle-import:R0402")
      (libsource (lib "eagle-import") (part "R-US_R0402"))
    )
    (comp (ref "R64")
      (value "100k")
      (footprint "eagle-import:R0402")
      (libsource (lib "eagle-import") (part "R-US_R0402"))
    )
    (comp (ref "R67")
      (value "100k")
      (footprint "eagle-import:R0402")
      (libsource (lib "eagle-import") (part "R-US_R0402"))
    )
    (comp (ref "R81")
      (value "10kA")
      (footprint "eagle-import:ALPS_POT_NARROW")
      (libsource (lib "eagle-import") (part "POT_USVERTICAL_NARROW"))
    )
    (comp (ref "R90")
      (value "5.1k")
      (footprint "eagle-import:R0402")
      (libsource (lib "eagle-import") (part "R-US_R0402"))
    )
    (comp (ref "R91")
      (value "30k")
      (footprint "eagle-import:R0402")
      (libsource (lib "eagle-import") (part "R-US_R0402"))
    )
    (comp (ref "R190")
      (value "120k")
      (footprint "eagle-import:R0402")
      (libsource (lib "eagle-import") (part "R-US_R0402"))
    )
    (comp (ref "R200")
      (value "300k")
      (footprint "eagle-import:R0402")
      (libsource (lib "eagle-import") (part "R-US_R0402"))
    )
    (comp (ref "C11")
      (value "220p")
      (footprint "eagle-import:C0402")
      (libsource (lib "eagle-import") (part "C-USC0402"))
    )
    (comp (ref "C14")
      (value "100n")
      (footprint "eagle-import:C0402")
      (libsource (lib "eagle-import") (part "C-USC0402"))
    )
    (comp (ref "C16")
      (value "100n")
      (footprint "eagle-import:C0402")
      (libsource (lib "eagle-import") (part "C-USC0402"))
    )
    (comp (ref "C17")
      (value "100n")
      (footprint "eagle-import:C0402")
      (libsource (lib "eagle-import") (part "C-USC0402"))
    )
    (comp (ref "C19")
      (value "560p")
      (footprint "eagle-import:C0402")
      (libsource (lib "eagle-import") (part "C-USC0402"))
    )
    (comp (ref "C23")
      (value "220p")
      (footprint "eagle-import:C0402")
      (libsource (lib "eagle-import") (part "C-USC0402"))
    )
    (comp (ref "C24")
      (value "220p")
      (footprint "eagle-import:C0402")
      (libsource (lib "eagle-import") (part "C-USC0402"))
    )
    (comp (ref "C25")
      (value "560p")
      (footprint "eagle-import:C0402")
      (libsource (lib "eagle-import") (part "C-USC0402"))
    )
    (comp (ref "C26")
      (value "560p")
      (footprint "eagle-import:C0402")
      (libsource (lib "eagle-import") (part "C-USC0402"))
    )
    (comp (ref "C28")
      (value "560p")
      (footprint "eagle-import:C0402")
      (libsource (lib "eagle-import") (part "C-USC0402"))
    )
    (comp (ref "C30")
      (value "100n")
      (footprint "eagle-import:C0402")
      (libsource (lib "eagle-import") (part "C-USC0402"))
    )
    (comp (ref "C32")
      (value "18p")
      (footprint "eagle-import:C0402")
      (libsource (lib "eagle-import") (part "C-USC0402"))
    )
    (comp (ref "C33")
      (value "18p")
      (footprint "eagle-import:C0402")
      (libsource (lib "eagle-import") (part "C-USC0402"))
    )
    (comp (ref "C36")
      (value "100n")
      (footprint "eagle-import:C0402")
      (libsource (lib "eagle-import") (part "C-USC0402"))
    )
    (comp (ref "C37")
      (value "100n")
      (footprint "eagle-import:C0402")
      (libsource (lib "eagle-import") (part "C-USC0402"))
    )
    (comp (ref "C40")
      (value "100n")
      (footprint "eagle-import:C0402")
      (libsource (lib "eagle-import") (part "C-USC0402"))
    )
    (comp (ref "C41")
      (value "100n")
      (footprint "eagle-import:C0402")
      (libsource (lib "eagle-import") (part "C-USC0402"))
    )
    (comp (ref "D7")
      (value "1N4148")
      (footprint "eagle-import:SOD523")
      (libsource (lib "eagle-import") (part "DIODE-SOD523"))
    )
    (comp (ref "D8")
      (value "1N4148")
      (footprint "eagle-import:SOD523")
      (libsource (lib "eagle-import") (part "DIODE-SOD523"))
    )
    (comp (ref "D9")
      (value "1N4148")
      (footprint "eagle-import:SOD523")
      (libsource (lib "eagle-import") (part "DIODE-SOD523"))
    )
    (comp (ref "D10")
      (value "1N4148")
      (footprint "eagle-import:SOD523")
      (libsource (lib "eagle-import") (part "DIODE-SOD523"))
    )
    (comp (ref "D61")
      (value "TVS")
      (footprint "eagle-import:0603")
      (libsource (lib "eagle-import") (part "TVS"))
    )
    (comp (ref "IC3")
      (value "TL074")
      (footprint "eagle-import:TSSOP14_065")
      (libsource (lib "eagle-import") (part "TL074PW"))
    )
    (comp (ref "IC4")
      (value "V2164SZ")
      (footprint "eagle-import:SOIC16N")
      (libsource (lib "eagle-import") (part "SSM2164S"))
    )
    (comp (ref "IC8")
      (value "OPA1679")
      (footprint "eagle-import:TSSOP14_065")
      (libsource (lib "eagle-import") (part "OPA1679PW"))
    )
    (comp (ref "IC9")
      (value "OPA1678")
      (footprint "eagle-import:VSSOP8")
      (libsource (lib "eagle-import") (part "OPA1678DGK"))
    )
    (comp (ref "J6")
      (value "PJ301_THONKICONNTME")
      (footprint "eagle-import:WQP_PJ_301M_TME")
      (libsource (lib "eagle-import") (part "PJ301_THONKICONNTME"))
    )
    (comp (ref "J13")
      (value "PJ301_THONKICONNTME")
      (footprint "eagle-import:WQP_PJ_301M_TME")
      (libsource (lib "eagle-import") (part "PJ301_THONKICONNTME"))
    )
    (comp (ref "R12")
      (value "100.0k")
      (footprint "eagle-import:R0402")
      (libsource (lib "eagle-import") (part "R-US_R0402"))
    )
    (comp (ref "R16")
      (value "100.0k")
      (footprint "eagle-import:R0402")
      (libsource (lib "eagle-import") (part "R-US_R0402"))
    )
    (comp (ref "R23")
      (value "100.0k")
      (footprint "eagle-import:R0402")
      (libsource (lib "eagle-import") (part "R-US_R0402"))
    )
    (comp (ref "R28")
      (value "3.9M")
      (footprint "eagle-import:R0402")
      (libsource (lib "eagle-import") (part "R-US_R0402"))
    )
    (comp (ref "R29")
      (value "95.3k")
      (footprint "eagle-import:R0402")
      (libsource (lib "eagle-import") (part "R-US_R0402"))
    )
    (comp (ref "R30")
      (value "6.2k")
      (footprint "eagle-import:R0402")
      (libsource (lib "eagle-import") (part "R-US_R0402"))
    )
    (comp (ref "R42")
      (value "100.0k")
      (footprint "eagle-import:R0402")
      (libsource (lib "eagle-import") (part "R-US_R0402"))
    )
    (comp (ref "R43")
      (value "100.0k")
      (footprint "eagle-import:R0402")
      (libsource (lib "eagle-import") (part "R-US_R0402"))
    )
    (comp (ref "R44")
      (value "62.0k")
      (footprint "eagle-import:R0402")
      (libsource (lib "eagle-import") (part "R-US_R0402"))
    )
    (comp (ref "R45")
      (value "510")
      (footprint "eagle-import:R0402")
      (libsource (lib "eagle-import") (part "R-US_R0402"))
    )
    (comp (ref "R46")
      (value "62.0k")
      (footprint "eagle-import:R0402")
      (libsource (lib "eagle-import") (part "R-US_R0402"))
    )
    (comp (ref "R47")
      (value "510")
      (footprint "eagle-import:R0402")
      (libsource (lib "eagle-import") (part "R-US_R0402"))
    )
    (comp (ref "R48")
      (value "510")
      (footprint "eagle-import:R0402")
      (libsource (lib "eagle-import") (part "R-US_R0402"))
    )
    (comp (ref "R49")
      (value "510")
      (footprint "eagle-import:R0402")
      (libsource (lib "eagle-import") (part "R-US_R0402"))
    )
    (comp (ref "R52")
      (value "200.0k")
      (footprint "eagle-import:R0402")
      (libsource (lib "eagle-import") (part "R-US_R0402"))
    )
    (comp (ref "R53")
      (value "100.0k")
      (footprint "eagle-import:R0402")
      (libsource (lib "eagle-import") (part "R-US_R0402"))
    )
    (comp (ref "R57")
      (value "62.0k")
      (footprint "eagle-import:R0402")
      (libsource (lib "eagle-import") (part "R-US_R0402"))
    )
    (comp (ref "R68")
      (value "62.0k")
      (footprint "eagle-import:R0402")
      (libsource (lib "eagle-import") (part "R-US_R0402"))
    )
    (comp (ref "R69")
      (value "62.0k")
      (footprint "eagle-import:R0402")
      (libsource (lib "eagle-import") (part "R-US_R0402"))
    )
    (comp (ref "R70")
      (value "62.0k")
      (footprint "eagle-import:R0402")
      (libsource (lib "eagle-import") (part "R-US_R0402"))
    )
    (comp (ref "R71")
      (value "62.0k")
      (footprint "eagle-import:R0402")
      (libsource (lib "eagle-import") (part "R-US_R0402"))
    )
    (comp (ref "R72")
      (value "62.0k")
      (footprint "eagle-import:R0402")
      (libsource (lib "eagle-import") (part "R-US_R0402"))
    )
    (comp (ref "R73")
      (value "62.0k")
      (footprint "eagle-import:R0402")
      (libsource (lib "eagle-import") (part "R-US_R0402"))
    )
    (comp (ref "R74")
      (value "30.0k")
      (footprint "eagle-import:R0402")
      (libsource (lib "eagle-import") (part "R-US_R0402"))
    )
    (comp (ref "R76")
      (value "30.0k")
      (footprint "eagle-import:R0402")
      (libsource (lib "eagle-import") (part "R-US_R0402"))
    )
    (comp (ref "R77")
      (value "30.0k")
      (footprint "eagle-import:R0402")
      (libsource (lib "eagle-import") (part "R-US_R0402"))
    )
    (comp (ref "R78")
      (value "30.0k")
      (footprint "eagle-import:R0402")
      (libsource (lib "eagle-import") (part "R-US_R0402"))
    )
    (comp (ref "R79")
      (value "62.0k")
      (footprint "eagle-import:R0402")
      (libsource (lib "eagle-import") (part "R-US_R0402"))
    )
    (comp (ref "R128")
      (value "10kB")
      (footprint "eagle-import:ALPS_POT_VERTICAL_PS")
      (libsource (lib "eagle-import") (part "pot-alps_POT_USVERTICAL_PS"))
    )
    (comp (ref "R139")
      (value "2k")
      (footprint "eagle-import:RTRIM3296W")
      (libsource (lib "eagle-import") (part "R-TRIMM3296W"))
    )
    (comp (ref "R140")
      (value "62.0k")
      (footprint "eagle-import:R0402")
      (libsource (lib "eagle-import") (part "R-US_R0402"))
    )
    (comp (ref "R179")
      (value "10kB")
      (footprint "eagle-import:ALPS_POT_NARROW")
      (libsource (lib "eagle-import") (part "POT_USVERTICAL_NARROW"))
    )
    (comp (ref "R186")
      (value "100.0k")
      (footprint "eagle-import:R0402")
      (libsource (lib "eagle-import") (part "R-US_R0402"))
    )
    (comp (ref "R192")
      (value "1.0k")
      (footprint "eagle-import:R0603")
      (libsource (lib "eagle-import") (part "R-US_R0603"))
    )
    (comp (ref "R194")
      (value "1.0k")
      (footprint "eagle-import:R0603")
      (libsource (lib "eagle-import") (part "R-US_R0603"))
    )
    (comp (ref "R197")
      (value "62.0k")
      (footprint "eagle-import:R0402")
      (libsource (lib "eagle-import") (part "R-US_R0402"))
    )
    (comp (ref "R198")
      (value "2k")
      (footprint "eagle-import:RTRIM3296W")
      (libsource (lib "eagle-import") (part "R-TRIMM3296W"))
    )
    (comp (ref "C46")
      (value "100n")
      (footprint "eagle-import:C0402")
      (libsource (lib "eagle-import") (part "C-USC0402"))
    )
    (comp (ref "C48")
      (value "560p")
      (footprint "eagle-import:C0402")
      (libsource (lib "eagle-import") (part "C-USC0402"))
    )
    (comp (ref "C51")
      (value "560p")
      (footprint "eagle-import:C0402")
      (libsource (lib "eagle-import") (part "C-USC0402"))
    )
    (comp (ref "C57")
      (value "560p")
      (footprint "eagle-import:C0402")
      (libsource (lib "eagle-import") (part "C-USC0402"))
    )
    (comp (ref "C59")
      (value "100n")
      (footprint "eagle-import:C0402")
      (libsource (lib "eagle-import") (part "C-USC0402"))
    )
    (comp (ref "C60")
      (value "560p")
      (footprint "eagle-import:C0402")
      (libsource (lib "eagle-import") (part "C-USC0402"))
    )
    (comp (ref "C64")
      (value "220p")
      (footprint "eagle-import:C0402")
      (libsource (lib "eagle-import") (part "C-USC0402"))
    )
    (comp (ref "C65")
      (value "220p")
      (footprint "eagle-import:C0402")
      (libsource (lib "eagle-import") (part "C-USC0402"))
    )
    (comp (ref "C68")
      (value "100n")
      (footprint "eagle-import:C0402")
      (libsource (lib "eagle-import") (part "C-USC0402"))
    )
    (comp (ref "C69")
      (value "100n")
      (footprint "eagle-import:C0402")
      (libsource (lib "eagle-import") (part "C-USC0402"))
    )
    (comp (ref "C71")
      (value "100n")
      (footprint "eagle-import:C0402")
      (libsource (lib "eagle-import") (part "C-USC0402"))
    )
    (comp (ref "C73")
      (value "DNP")
      (footprint "eagle-import:C0402")
      (libsource (lib "eagle-import") (part "C-USC0402"))
    )
    (comp (ref "C74")
      (value "560p")
      (footprint "eagle-import:C0402")
      (libsource (lib "eagle-import") (part "C-USC0402"))
    )
    (comp (ref "C76")
      (value "560p")
      (footprint "eagle-import:C0402")
      (libsource (lib "eagle-import") (part "C-USC0402"))
    )
    (comp (ref "C78")
      (value "560p")
      (footprint "eagle-import:C0402")
      (libsource (lib "eagle-import") (part "C-USC0402"))
    )
    (comp (ref "C83")
      (value "220p")
      (footprint "eagle-import:C0402")
      (libsource (lib "eagle-import") (part "C-USC0402"))
    )
    (comp (ref "C85")
      (value "100n")
      (footprint "eagle-import:C0402")
      (libsource (lib "eagle-import") (part "C-USC0402"))
    )
    (comp (ref "C87")
      (value "18p")
      (footprint "eagle-import:C0402")
      (libsource (lib "eagle-import") (part "C-USC0402"))
    )
    (comp (ref "C88")
      (value "220p")
      (footprint "eagle-import:C0402")
      (libsource (lib "eagle-import") (part "C-USC0402"))
    )
    (comp (ref "C89")
      (value "220p")
      (footprint "eagle-import:C0402")
      (libsource (lib "eagle-import") (part "C-USC0402"))
    )
    (comp (ref "C93")
      (value "100n")
      (footprint "eagle-import:C0402")
      (libsource (lib "eagle-import") (part "C-USC0402"))
    )
    (comp (ref "C96")
      (value "100n")
      (footprint "eagle-import:C0402")
      (libsource (lib "eagle-import") (part "C-USC0402"))
    )
    (comp (ref "C97")
      (value "100n")
      (footprint "eagle-import:C0402")
      (libsource (lib "eagle-import") (part "C-USC0402"))
    )
    (comp (ref "C98")
      (value "100n")
      (footprint "eagle-import:C0402")
      (libsource (lib "eagle-import") (part "C-USC0402"))
    )
    (comp (ref "C101")
      (value "220p")
      (footprint "eagle-import:C0402")
      (libsource (lib "eagle-import") (part "C-USC0402"))
    )
    (comp (ref "D22")
      (value "BZT585B5V1T")
      (footprint "eagle-import:SOD523")
      (libsource (lib "eagle-import") (part "DIODE-SOD523"))
    )
    (comp (ref "D23")
      (value "BZT585B5V1T")
      (footprint "eagle-import:SOD523")
      (libsource (lib "eagle-import") (part "DIODE-SOD523"))
    )
    (comp (ref "D26")
      (value "1N4148")
      (footprint "eagle-import:SOD523")
      (libsource (lib "eagle-import") (part "DIODE-SOD523"))
    )
    (comp (ref "D28")
      (value "1N4148")
      (footprint "eagle-import:SOD523")
      (libsource (lib "eagle-import") (part "DIODE-SOD523"))
    )
    (comp (ref "D30")
      (value "1N4148")
      (footprint "eagle-import:SOD523")
      (libsource (lib "eagle-import") (part "DIODE-SOD523"))
    )
    (comp (ref "D31")
      (value "1N4148")
      (footprint "eagle-import:SOD523")
      (libsource (lib "eagle-import") (part "DIODE-SOD523"))
    )
    (comp (ref "D33")
      (value "1N4148")
      (footprint "eagle-import:SOD523")
      (libsource (lib "eagle-import") (part "DIODE-SOD523"))
    )
    (comp (ref "D36")
      (value "1N4148")
      (footprint "eagle-import:SOD523")
      (libsource (lib "eagle-import") (part "DIODE-SOD523"))
    )
    (comp (ref "D37")
      (value "BZT585B5V1T")
      (footprint "eagle-import:SOD523")
      (libsource (lib "eagle-import") (part "DIODE-SOD523"))
    )
    (comp (ref "D39")
      (value "BZT585B5V1T")
      (footprint "eagle-import:SOD523")
      (libsource (lib "eagle-import") (part "DIODE-SOD523"))
    )
    (comp (ref "D42")
      (value "BZT585B5V1T")
      (footprint "eagle-import:SOD523")
      (libsource (lib "eagle-import") (part "DIODE-SOD523"))
    )
    (comp (ref "D43")
      (value "BZT585B5V1T")
      (footprint "eagle-import:SOD523")
      (libsource (lib "eagle-import") (part "DIODE-SOD523"))
    )
    (comp (ref "D46")
      (value "1N4148")
      (footprint "eagle-import:SOD523")
      (libsource (lib "eagle-import") (part "DIODE-SOD523"))
    )
    (comp (ref "D47")
      (value "1N4148")
      (footprint "eagle-import:SOD523")
      (libsource (lib "eagle-import") (part "DIODE-SOD523"))
    )
    (comp (ref "D54")
      (value "TVS")
      (footprint "eagle-import:0603")
      (libsource (lib "eagle-import") (part "TVS"))
    )
    (comp (ref "D56")
      (value "TVS")
      (footprint "eagle-import:0603")
      (libsource (lib "eagle-import") (part "TVS"))
    )
    (comp (ref "D58")
      (value "TVS")
      (footprint "eagle-import:0603")
      (libsource (lib "eagle-import") (part "TVS"))
    )
    (comp (ref "D60")
      (value "TVS")
      (footprint "eagle-import:0603")
      (libsource (lib "eagle-import") (part "TVS"))
    )
    (comp (ref "IC13")
      (value "V2164SZ")
      (footprint "eagle-import:SOIC16N")
      (libsource (lib "eagle-import") (part "SSM2164S"))
    )
    (comp (ref "IC15")
      (value "OPA1679")
      (footprint "eagle-import:TSSOP14_065")
      (libsource (lib "eagle-import") (part "OPA1679PW"))
    )
    (comp (ref "IC17")
      (value "V2164SZ")
      (footprint "eagle-import:SOIC16N")
      (libsource (lib "eagle-import") (part "SSM2164S"))
    )
    (comp (ref "IC20")
      (value "TL074")
      (footprint "eagle-import:TSSOP14_065")
      (libsource (lib "eagle-import") (part "TL074PW"))
    )
    (comp (ref "IC21")
      (value "OPA1679")
      (footprint "eagle-import:TSSOP14_065")
      (libsource (lib "eagle-import") (part "OPA1679PW"))
    )
    (comp (ref "J2")
      (value "PJ301_THONKICONNTME")
      (footprint "eagle-import:WQP_PJ_301M_TME")
      (libsource (lib "eagle-import") (part "PJ301_THONKICONNTME"))
    )
    (comp (ref "J7")
      (value "PJ301_THONKICONNTME")
      (footprint "eagle-import:WQP_PJ_301M_TME")
      (libsource (lib "eagle-import") (part "PJ301_THONKICONNTME"))
    )
    (comp (ref "J8")
      (value "PJ301_THONKICONNTME")
      (footprint "eagle-import:WQP_PJ_301M_TME")
      (libsource (lib "eagle-import") (part "PJ301_THONKICONNTME"))
    )
    (comp (ref "J14")
      (value "PJ301_THONKICONNTME")
      (footprint "eagle-import:WQP_PJ_301M_TME")
      (libsource (lib "eagle-import") (part "PJ301_THONKICONNTME"))
    )
    (comp (ref "J15")
      (value "PJ301_THONKICONNTME")
      (footprint "eagle-import:WQP_PJ_301M_TME")
      (libsource (lib "eagle-import") (part "PJ301_THONKICONNTME"))
    )
    (comp (ref "R15")
      (value "10kB")
      (footprint "eagle-import:ALPS_POT_VERTICAL_PS")
      (libsource (lib "eagle-import") (part "pot-alps_POT_USVERTICAL_PS"))
    )
    (comp (ref "R54")
      (value "88.7k")
      (footprint "eagle-import:R0402")
      (libsource (lib "eagle-import") (part "R-US_R0402"))
    )
    (comp (ref "R62")
      (value "30.0k")
      (footprint "eagle-import:R0402")
      (libsource (lib "eagle-import") (part "R-US_R0402"))
    )
    (comp (ref "R63")
      (value "100k")
      (footprint "eagle-import:R0402")
      (libsource (lib "eagle-import") (part "R-US_R0402"))
    )
    (comp (ref "R75")
      (value "510")
      (footprint "eagle-import:R0402")
      (libsource (lib "eagle-import") (part "R-US_R0402"))
    )
    (comp (ref "R85")
      (value "680k")
      (footprint "eagle-import:R0402")
      (libsource (lib "eagle-import") (part "R-US_R0402"))
    )
    (comp (ref "R87")
      (value "10kB")
      (footprint "eagle-import:ALPS_POT_VERTICAL_PS")
      (libsource (lib "eagle-import") (part "pot-alps_POT_USVERTICAL_PS"))
    )
    (comp (ref "R93")
      (value "200.0k")
      (footprint "eagle-import:R0402")
      (libsource (lib "eagle-import") (part "R-US_R0402"))
    )
    (comp (ref "R95")
      (value "510")
      (footprint "eagle-import:R0402")
      (libsource (lib "eagle-import") (part "R-US_R0402"))
    )
    (comp (ref "R97")
      (value "62.0k")
      (footprint "eagle-import:R0402")
      (libsource (lib "eagle-import") (part "R-US_R0402"))
    )
    (comp (ref "R99")
      (value "62.0k")
      (footprint "eagle-import:R0402")
      (libsource (lib "eagle-import") (part "R-US_R0402"))
    )
    (comp (ref "R101")
      (value "510")
      (footprint "eagle-import:R0402")
      (libsource (lib "eagle-import") (part "R-US_R0402"))
    )
    (comp (ref "R103")
      (value "510")
      (footprint "eagle-import:R0402")
      (libsource (lib "eagle-import") (part "R-US_R0402"))
    )
    (comp (ref "R106")
      (value "30.0k")
      (footprint "eagle-import:R0402")
      (libsource (lib "eagle-import") (part "R-US_R0402"))
    )
    (comp (ref "R107")
      (value "510")
      (footprint "eagle-import:R0402")
      (libsource (lib "eagle-import") (part "R-US_R0402"))
    )
    (comp (ref "R109")
      (value "200.0k")
      (footprint "eagle-import:R0402")
      (libsource (lib "eagle-import") (part "R-US_R0402"))
    )
    (comp (ref "R112")
      (value "62.0k")
      (footprint "eagle-import:R0402")
      (libsource (lib "eagle-import") (part "R-US_R0402"))
    )
    (comp (ref "R113")
      (value "30k")
      (footprint "eagle-import:R0402")
      (libsource (lib "eagle-import") (part "R-US_R0402"))
    )
    (comp (ref "R117")
      (value "30k")
      (footprint "eagle-import:R0402")
      (libsource (lib "eagle-import") (part "R-US_R0402"))
    )
    (comp (ref "R119")
      (value "62.0k")
      (footprint "eagle-import:R0402")
      (libsource (lib "eagle-import") (part "R-US_R0402"))
    )
    (comp (ref "R120")
      (value "30.0k")
      (footprint "eagle-import:R0402")
      (libsource (lib "eagle-import") (part "R-US_R0402"))
    )
    (comp (ref "R121")
      (value "30k")
      (footprint "eagle-import:R0402")
      (libsource (lib "eagle-import") (part "R-US_R0402"))
    )
    (comp (ref "R123")
      (value "300k")
      (footprint "eagle-import:R0402")
      (libsource (lib "eagle-import") (part "R-US_R0402"))
    )
    (comp (ref "R124")
      (value "680k")
      (footprint "eagle-import:R0402")
      (libsource (lib "eagle-import") (part "R-US_R0402"))
    )
    (comp (ref "R126")
      (value "30k")
      (footprint "eagle-import:R0402")
      (libsource (lib "eagle-import") (part "R-US_R0402"))
    )
    (comp (ref "R129")
      (value "30k")
      (footprint "eagle-import:R0402")
      (libsource (lib "eagle-import") (part "R-US_R0402"))
    )
    (comp (ref "R130")
      (value "10kB")
      (footprint "eagle-import:ALPS_POT_VERTICAL_PS")
      (libsource (lib "eagle-import") (part "pot-alps_POT_USVERTICAL_PS"))
    )
    (comp (ref "R133")
      (value "510")
      (footprint "eagle-import:R0402")
      (libsource (lib "eagle-import") (part "R-US_R0402"))
    )
    (comp (ref "R135")
      (value "510")
      (footprint "eagle-import:R0402")
      (libsource (lib "eagle-import") (part "R-US_R0402"))
    )
    (comp (ref "R137")
      (value "510")
      (footprint "eagle-import:R0402")
      (libsource (lib "eagle-import") (part "R-US_R0402"))
    )
    (comp (ref "R141")
      (value "15k")
      (footprint "eagle-import:R0402")
      (libsource (lib "eagle-import") (part "R-US_R0402"))
    )
    (comp (ref "R144")
      (value "100.0k")
      (footprint "eagle-import:R0402")
      (libsource (lib "eagle-import") (part "R-US_R0402"))
    )
    (comp (ref "R145")
      (value "200.0k")
      (footprint "eagle-import:R0402")
      (libsource (lib "eagle-import") (part "R-US_R0402"))
    )
    (comp (ref "R149")
      (value "30.0k")
      (footprint "eagle-import:R0402")
      (libsource (lib "eagle-import") (part "R-US_R0402"))
    )
    (comp (ref "R150")
      (value "20k")
      (footprint "eagle-import:R0402")
      (libsource (lib "eagle-import") (part "R-US_R0402"))
    )
    (comp (ref "R152")
      (value "100.0k")
      (footprint "eagle-import:R0402")
      (libsource (lib "eagle-import") (part "R-US_R0402"))
    )
    (comp (ref "R154")
      (value "120k")
      (footprint "eagle-import:R0402")
      (libsource (lib "eagle-import") (part "R-US_R0402"))
    )
    (comp (ref "R157")
      (value "100k")
      (footprint "eagle-import:R0402")
      (libsource (lib "eagle-import") (part "R-US_R0402"))
    )
    (comp (ref "R158")
      (value "44.2k")
      (footprint "eagle-import:R0402")
      (libsource (lib "eagle-import") (part "R-US_R0402"))
    )
    (comp (ref "R159")
      (value "100.0k")
      (footprint "eagle-import:R0402")
      (libsource (lib "eagle-import") (part "R-US_R0402"))
    )
    (comp (ref "R162")
      (value "100.0k")
      (footprint "eagle-import:R0402")
      (libsource (lib "eagle-import") (part "R-US_R0402"))
    )
    (comp (ref "R163")
      (value "30.0k")
      (footprint "eagle-import:R0402")
      (libsource (lib "eagle-import") (part "R-US_R0402"))
    )
    (comp (ref "R168")
      (value "20k")
      (footprint "eagle-import:R0402")
      (libsource (lib "eagle-import") (part "R-US_R0402"))
    )
    (comp (ref "R169")
      (value "10M")
      (footprint "eagle-import:R0402")
      (libsource (lib "eagle-import") (part "R-US_R0402"))
    )
    (comp (ref "R171")
      (value "20k")
      (footprint "eagle-import:R0402")
      (libsource (lib "eagle-import") (part "R-US_R0402"))
    )
    (comp (ref "R172")
      (value "30.0k")
      (footprint "eagle-import:R0402")
      (libsource (lib "eagle-import") (part "R-US_R0402"))
    )
    (comp (ref "R174")
      (value "62.0k")
      (footprint "eagle-import:R0402")
      (libsource (lib "eagle-import") (part "R-US_R0402"))
    )
    (comp (ref "R175")
      (value "100.0k")
      (footprint "eagle-import:R0402")
      (libsource (lib "eagle-import") (part "R-US_R0402"))
    )
    (comp (ref "R180")
      (value "10kB")
      (footprint "eagle-import:ALPS_POT_NARROW")
      (libsource (lib "eagle-import") (part "POT_USVERTICAL_NARROW"))
    )
    (comp (ref "R181")
      (value "10kB")
      (footprint "eagle-import:ALPS_POT_NARROW")
      (libsource (lib "eagle-import") (part "POT_USVERTICAL_NARROW"))
    )
    (comp (ref "R187")
      (value "100k")
      (footprint "eagle-import:R0402")
      (libsource (lib "eagle-import") (part "R-US_R0402"))
    )
    (comp (ref "R188")
      (value "DNP")
      (footprint "eagle-import:R0603")
      (libsource (lib "eagle-import") (part "R-US_R0603"))
    )
    (comp (ref "R189")
      (value "100.0k")
      (footprint "eagle-import:R0402")
      (libsource (lib "eagle-import") (part "R-US_R0402"))
    )
    (comp (ref "R193")
      (value "1.0k")
      (footprint "eagle-import:R0603")
      (libsource (lib "eagle-import") (part "R-US_R0603"))
    )
    (comp (ref "R195")
      (value "2k")
      (footprint "eagle-import:RTRIM3296W")
      (libsource (lib "eagle-import") (part "R-TRIMM3296W"))
    )
    (comp (ref "SW1")
      (value "LP4OA1PBCT")
      (footprint "eagle-import:LP4OA1PBCT")
      (libsource (lib "eagle-import") (part "LP4OA1PBCT"))
    )
    (comp (ref "C3")
      (value "100n")
      (footprint "eagle-import:C0402")
      (libsource (lib "eagle-import") (part "C-USC0402"))
    )
    (comp (ref "C4")
      (value "100n")
      (footprint "eagle-import:C0402")
      (libsource (lib "eagle-import") (part "C-USC0402"))
    )
    (comp (ref "C38")
      (value "100n")
      (footprint "eagle-import:C0402")
      (libsource (lib "eagle-import") (part "C-USC0402"))
    )
    (comp (ref "C39")
      (value "100n")
      (footprint "eagle-import:C0402")
      (libsource (lib "eagle-import") (part "C-USC0402"))
    )
    (comp (ref "C42")
      (value "100n")
      (footprint "eagle-import:C0402")
      (libsource (lib "eagle-import") (part "C-USC0402"))
    )
    (comp (ref "C43")
      (value "100n")
      (footprint "eagle-import:C0402")
      (libsource (lib "eagle-import") (part "C-USC0402"))
    )
    (comp (ref "C44")
      (value "22u")
      (footprint "eagle-import:C1206")
      (libsource (lib "eagle-import") (part "C-USC1206"))
    )
    (comp (ref "C45")
      (value "22u")
      (footprint "eagle-import:C1206")
      (libsource (lib "eagle-import") (part "C-USC1206"))
    )
    (comp (ref "C52")
      (value "22u")
      (footprint "eagle-import:C1206")
      (libsource (lib "eagle-import") (part "C-USC1206"))
    )
    (comp (ref "C53")
      (value "22u")
      (footprint "eagle-import:C1206")
      (libsource (lib "eagle-import") (part "C-USC1206"))
    )
    (comp (ref "C54")
      (value "22u")
      (footprint "eagle-import:PANASONIC_B")
      (libsource (lib "eagle-import") (part "CPOL-USB"))
    )
    (comp (ref "C55")
      (value "22u")
      (footprint "eagle-import:PANASONIC_B")
      (libsource (lib "eagle-import") (part "CPOL-USB"))
    )
    (comp (ref "D19")
      (value "1N5819HW")
      (footprint "eagle-import:SOD123")
      (libsource (lib "eagle-import") (part "DIODE-SOD123"))
    )
    (comp (ref "D20")
      (value "1N5819HW")
      (footprint "eagle-import:SOD123")
      (libsource (lib "eagle-import") (part "DIODE-SOD123"))
    )
    (comp (ref "IC10")
      (value "LM4040B5")
      (footprint "eagle-import:DBZ_R-PDSO-G3")
      (libsource (lib "eagle-import") (part "LM4041DBZB12"))
    )
    (comp (ref "IC11")
      (value "LM4040B5")
      (footprint "eagle-import:DBZ_R-PDSO-G3")
      (libsource (lib "eagle-import") (part "LM4041DBZB12"))
    )
    (comp (ref "JP1")
      (value "M05X2SHD")
      (footprint "eagle-import:2X5-SHROUDED")
      (libsource (lib "eagle-import") (part "M05X2SHD"))
    )
    (comp (ref "L1")
      (value "742792664")
      (footprint "eagle-import:0603")
      (libsource (lib "eagle-import") (part "WE-CBF_0603"))
    )
    (comp (ref "L2")
      (value "742792664")
      (footprint "eagle-import:0603")
      (libsource (lib "eagle-import") (part "WE-CBF_0603"))
    )
    (comp (ref "P1")
      (value "PTCSMD")
      (footprint "eagle-import:PTC-1206")
      (libsource (lib "eagle-import") (part "PTCSMD"))
    )
    (comp (ref "R82")
      (value "1.8k")
      (footprint "eagle-import:R0402")
      (libsource (lib "eagle-import") (part "R-US_R0402"))
    )
    (comp (ref "R83")
      (value "1.8k")
      (footprint "eagle-import:R0402")
      (libsource (lib "eagle-import") (part "R-US_R0402"))
    )
    (comp (ref "C1")
      (value "100n")
      (footprint "eagle-import:C0402")
      (libsource (lib "eagle-import") (part "C-USC0402"))
    )
    (comp (ref "C6")
      (value "18p")
      (footprint "eagle-import:C0402")
      (libsource (lib "eagle-import") (part "C-USC0402"))
    )
    (comp (ref "C8")
      (value "100n")
      (footprint "eagle-import:C0402")
      (libsource (lib "eagle-import") (part "C-USC0402"))
    )
    (comp (ref "C10")
      (value "220p")
      (footprint "eagle-import:C0402")
      (libsource (lib "eagle-import") (part "C-USC0402"))
    )
    (comp (ref "C12")
      (value "18p")
      (footprint "eagle-import:C0402")
      (libsource (lib "eagle-import") (part "C-USC0402"))
    )
    (comp (ref "C21")
      (value "560p")
      (footprint "eagle-import:C0402")
      (libsource (lib "eagle-import") (part "C-USC0402"))
    )
    (comp (ref "C22")
      (value "560p")
      (footprint "eagle-import:C0402")
      (libsource (lib "eagle-import") (part "C-USC0402"))
    )
    (comp (ref "C29")
      (value "100n")
      (footprint "eagle-import:C0402")
      (libsource (lib "eagle-import") (part "C-USC0402"))
    )
    (comp (ref "C34")
      (value "100n")
      (footprint "eagle-import:C0402")
      (libsource (lib "eagle-import") (part "C-USC0402"))
    )
    (comp (ref "C79")
      (value "100n")
      (footprint "eagle-import:C0402")
      (libsource (lib "eagle-import") (part "C-USC0402"))
    )
    (comp (ref "D1")
      (value "1N4148")
      (footprint "eagle-import:SOD523")
      (libsource (lib "eagle-import") (part "DIODE-SOD523"))
    )
    (comp (ref "D4")
      (value "BZT585B5V1T")
      (footprint "eagle-import:SOD523")
      (libsource (lib "eagle-import") (part "DIODE-SOD523"))
    )
    (comp (ref "D5")
      (value "BZT585B5V1T")
      (footprint "eagle-import:SOD523")
      (libsource (lib "eagle-import") (part "DIODE-SOD523"))
    )
    (comp (ref "D11")
      (value "1N4148")
      (footprint "eagle-import:SOD523")
      (libsource (lib "eagle-import") (part "DIODE-SOD523"))
    )
    (comp (ref "D14")
      (value "1N4148")
      (footprint "eagle-import:SOD523")
      (libsource (lib "eagle-import") (part "DIODE-SOD523"))
    )
    (comp (ref "D15")
      (value "1N4148")
      (footprint "eagle-import:SOD523")
      (libsource (lib "eagle-import") (part "DIODE-SOD523"))
    )
    (comp (ref "D17")
      (value "1N4148")
      (footprint "eagle-import:SOD523")
      (libsource (lib "eagle-import") (part "DIODE-SOD523"))
    )
    (comp (ref "D49")
      (value "TVS")
      (footprint "eagle-import:0603")
      (libsource (lib "eagle-import") (part "TVS"))
    )
    (comp (ref "D50")
      (value "TVS")
      (footprint "eagle-import:0603")
      (libsource (lib "eagle-import") (part "TVS"))
    )
    (comp (ref "IC2")
      (value "OPA1679")
      (footprint "eagle-import:TSSOP14_065")
      (libsource (lib "eagle-import") (part "OPA1679PW"))
    )
    (comp (ref "IC6")
      (value "OPA1678")
      (footprint "eagle-import:VSSOP8")
      (libsource (lib "eagle-import") (part "OPA1678DGK"))
    )
    (comp (ref "J3")
      (value "PJ301_THONKICONNTME")
      (footprint "eagle-import:WQP_PJ_301M_TME")
      (libsource (lib "eagle-import") (part "PJ301_THONKICONNTME"))
    )
    (comp (ref "J10")
      (value "PJ301_THONKICONNTME")
      (footprint "eagle-import:WQP_PJ_301M_TME")
      (libsource (lib "eagle-import") (part "PJ301_THONKICONNTME"))
    )
    (comp (ref "LED1")
      (value "OSC84L3131A")
      (footprint "eagle-import:LED3MM")
      (libsource (lib "eagle-import") (part "LED3MM"))
    )
    (comp (ref "R1")
      (value "6.2k")
      (footprint "eagle-import:R0402")
      (libsource (lib "eagle-import") (part "R-US_R0402"))
    )
    (comp (ref "R3")
      (value "5.1k")
      (footprint "eagle-import:R0402")
      (libsource (lib "eagle-import") (part "R-US_R0402"))
    )
    (comp (ref "R5")
      (value "200.0k")
      (footprint "eagle-import:R0402")
      (libsource (lib "eagle-import") (part "R-US_R0402"))
    )
    (comp (ref "R7")
      (value "30k")
      (footprint "eagle-import:R0402")
      (libsource (lib "eagle-import") (part "R-US_R0402"))
    )
    (comp (ref "R10")
      (value "62.0k")
      (footprint "eagle-import:R0402")
      (libsource (lib "eagle-import") (part "R-US_R0402"))
    )
    (comp (ref "R11")
      (value "62.0k")
      (footprint "eagle-import:R0402")
      (libsource (lib "eagle-import") (part "R-US_R0402"))
    )
    (comp (ref "R17")
      (value "10kB")
      (footprint "eagle-import:ALPS_POT_VERTICAL_PS")
      (libsource (lib "eagle-import") (part "pot-alps_POT_USVERTICAL_PS"))
    )
    (comp (ref "R21")
      (value "10M")
      (footprint "eagle-import:R0402")
      (libsource (lib "eagle-import") (part "R-US_R0402"))
    )
    (comp (ref "R22")
      (value "100k")
      (footprint "eagle-import:R0402")
      (libsource (lib "eagle-import") (part "R-US_R0402"))
    )
    (comp (ref "R24")
      (value "30k")
      (footprint "eagle-import:R0402")
      (libsource (lib "eagle-import") (part "R-US_R0402"))
    )
    (comp (ref "R27")
      (value "5.1k")
      (footprint "eagle-import:R0402")
      (libsource (lib "eagle-import") (part "R-US_R0402"))
    )
    (comp (ref "R32")
      (value "100k")
      (footprint "eagle-import:R0402")
      (libsource (lib "eagle-import") (part "R-US_R0402"))
    )
    (comp (ref "R33")
      (value "30k")
      (footprint "eagle-import:R0402")
      (libsource (lib "eagle-import") (part "R-US_R0402"))
    )
    (comp (ref "R36")
      (value "510")
      (footprint "eagle-import:R0402")
      (libsource (lib "eagle-import") (part "R-US_R0402"))
    )
    (comp (ref "R40")
      (value "510")
      (footprint "eagle-import:R0402")
      (libsource (lib "eagle-import") (part "R-US_R0402"))
    )
    (comp (ref "R41")
      (value "5.1k")
      (footprint "eagle-import:R0402")
      (libsource (lib "eagle-import") (part "R-US_R0402"))
    )
    (comp (ref "R50")
      (value "100k")
      (footprint "eagle-import:R0402")
      (libsource (lib "eagle-import") (part "R-US_R0402"))
    )
    (comp (ref "R51")
      (value "100k")
      (footprint "eagle-import:R0402")
      (libsource (lib "eagle-import") (part "R-US_R0402"))
    )
    (comp (ref "R58")
      (value "30k")
      (footprint "eagle-import:R0402")
      (libsource (lib "eagle-import") (part "R-US_R0402"))
    )
    (comp (ref "R61")
      (value "100k")
      (footprint "eagle-import:R0402")
      (libsource (lib "eagle-import") (part "R-US_R0402"))
    )
    (comp (ref "R65")
      (value "100k")
      (footprint "eagle-import:R0402")
      (libsource (lib "eagle-import") (part "R-US_R0402"))
    )
    (comp (ref "R66")
      (value "100k")
      (footprint "eagle-import:R0402")
      (libsource (lib "eagle-import") (part "R-US_R0402"))
    )
    (comp (ref "R80")
      (value "10kA")
      (footprint "eagle-import:ALPS_POT_NARROW")
      (libsource (lib "eagle-import") (part "POT_USVERTICAL_NARROW"))
    )
    (comp (ref "R88")
      (value "5.1k")
      (footprint "eagle-import:R0402")
      (libsource (lib "eagle-import") (part "R-US_R0402"))
    )
    (comp (ref "R89")
      (value "30k")
      (footprint "eagle-import:R0402")
      (libsource (lib "eagle-import") (part "R-US_R0402"))
    )
    (comp (ref "R182")
      (value "120k")
      (footprint "eagle-import:R0402")
      (libsource (lib "eagle-import") (part "R-US_R0402"))
    )
    (comp (ref "R199")
      (value "300k")
      (footprint "eagle-import:R0402")
      (libsource (lib "eagle-import") (part "R-US_R0402"))
    )
  )
  (nets
    (net (code "1") (name "AREF_+5") (class "Default")
      (node (ref "C3") (pin "1") (pinfunction "1_1") (pintype "passive"))
      (node (ref "C39") (pin "1") (pinfunction "1_1") (pintype "passive"))
      (node (ref "C4") (pin "1") (pinfunction "1_1") (pintype "passive"))
      (node (ref "IC11") (pin "1") (pinfunction "C_1") (pintype "passive"))
      (node (ref "R127") (pin "P$1") (pinfunction "E_P$1") (pintype "passive"))
      (node (ref "R130") (pin "P$1") (pinfunction "E_P$1") (pintype "passive"))
      (node (ref "R17") (pin "P$1") (pinfunction "E_P$1") (pintype "passive"))
      (node (ref "R18") (pin "P$1") (pinfunction "E_P$1") (pintype "passive"))
      (node (ref "R182") (pin "2") (pinfunction "2_2") (pintype "passive"))
      (node (ref "R190") (pin "2") (pinfunction "2_2") (pintype "passive"))
      (node (ref "R28") (pin "1") (pinfunction "1_1") (pintype "passive"))
      (node (ref "R83") (pin "2") (pinfunction "2_2") (pintype "passive"))
    )
    (net (code "2") (name "AREF_-5") (class "Default")
      (node (ref "C38") (pin "1") (pinfunction "1_1") (pintype "passive"))
      (node (ref "C42") (pin "1") (pinfunction "1_1") (pintype "passive"))
      (node (ref "C43") (pin "1") (pinfunction "1_1") (pintype "passive"))
      (node (ref "IC10") (pin "2") (pinfunction "A_2") (pintype "passive"))
      (node (ref "R108") (pin "1") (pinfunction "1_1") (pintype "passive"))
      (node (ref "R109") (pin "1") (pinfunction "1_1") (pintype "passive"))
      (node (ref "R128") (pin "P$3") (pinfunction "A_P$3") (pintype "passive"))
      (node (ref "R14") (pin "P$1") (pinfunction "E_P$1") (pintype "passive"))
      (node (ref "R145") (pin "1") (pinfunction "1_1") (pintype "passive"))
      (node (ref "R146") (pin "1") (pinfunction "1_1") (pintype "passive"))
      (node (ref "R15") (pin "P$1") (pinfunction "E_P$1") (pintype "passive"))
      (node (ref "R169") (pin "1") (pinfunction "1_1") (pintype "passive"))
      (node (ref "R170") (pin "1") (pinfunction "1_1") (pintype "passive"))
      (node (ref "R20") (pin "1") (pinfunction "1_1") (pintype "passive"))
      (node (ref "R21") (pin "1") (pinfunction "1_1") (pintype "passive"))
      (node (ref "R32") (pin "1") (pinfunction "1_1") (pintype "passive"))
      (node (ref "R35") (pin "1") (pinfunction "1_1") (pintype "passive"))
      (node (ref "R52") (pin "1") (pinfunction "1_1") (pintype "passive"))
      (node (ref "R53") (pin "1") (pinfunction "1_1") (pintype "passive"))
      (node (ref "R54") (pin "1") (pinfunction "1_1") (pintype "passive"))
      (node (ref "R82") (pin "2") (pinfunction "2_2") (pintype "passive"))
      (node (ref "R86") (pin "P$3") (pinfunction "A_P$3") (pintype "passive"))
      (node (ref "R87") (pin "P$3") (pinfunction "A_P$3") (pintype "passive"))
      (node (ref "R92") (pin "1") (pinfunction "1_1") (pintype "passive"))
      (node (ref "R93") (pin "1") (pinfunction "1_1") (pintype "passive"))
    )
    (net (code "3") (name "BP_1") (class "Default")
      (node (ref "C62") (pin "2") (pinfunction "2_2") (pintype "passive"))
      (node (ref "D21") (pin "A") (pinfunction "A_A") (pintype "passive"))
      (node (ref "IC14") (pin "1") (pinfunction "OUT_1") (pintype "output"))
      (node (ref "R118") (pin "1") (pinfunction "1_1") (pintype "passive"))
      (node (ref "R122") (pin "2") (pinfunction "2_2") (pintype "passive"))
      (node (ref "R131") (pin "1") (pinfunction "1_1") (pintype "passive"))
      (node (ref "R142") (pin "1") (pinfunction "1_1") (pintype "passive"))
      (node (ref "R98") (pin "1") (pinfunction "1_1") (pintype "passive"))
    )
    (net (code "4") (name "BP_2") (class "Default")
      (node (ref "C65") (pin "2") (pinfunction "2_2") (pintype "passive"))
      (node (ref "D22") (pin "A") (pinfunction "A_A") (pintype "passive"))
      (node (ref "IC15") (pin "14") (pinfunction "OUT_14") (pintype "output"))
      (node (ref "R119") (pin "1") (pinfunction "1_1") (pintype "passive"))
      (node (ref "R123") (pin "2") (pinfunction "2_2") (pintype "passive"))
      (node (ref "R129") (pin "1") (pinfunction "1_1") (pintype "passive"))
      (node (ref "R141") (pin "1") (pinfunction "1_1") (pintype "passive"))
      (node (ref "R99") (pin "1") (pinfunction "1_1") (pintype "passive"))
    )
    (net (code "5") (name "F_CV_1_PRE") (class "Default")
      (node (ref "C90") (pin "2") (pinfunction "2_2") (pintype "passive"))
      (node (ref "D32") (pin "C") (pinfunction "C_C") (pintype "passive"))
      (node (ref "R147") (pin "2") (pinfunction "2_2") (pintype "passive"))
      (node (ref "R196") (pin "3") (pinfunction "A_3") (pintype "passive"))
      (node (ref "R62") (pin "1") (pinfunction "1_1") (pintype "passive"))
    )
    (net (code "6") (name "GND") (class "Default")
      (node (ref "C1") (pin "1") (pinfunction "1_1") (pintype "passive"))
      (node (ref "C14") (pin "2") (pinfunction "2_2") (pintype "passive"))
      (node (ref "C15") (pin "2") (pinfunction "2_2") (pintype "passive"))
      (node (ref "C16") (pin "1") (pinfunction "1_1") (pintype "passive"))
      (node (ref "C17") (pin "2") (pinfunction "2_2") (pintype "passive"))
      (node (ref "C18") (pin "2") (pinfunction "2_2") (pintype "passive"))
      (node (ref "C19") (pin "2") (pinfunction "2_2") (pintype "passive"))
      (node (ref "C2") (pin "2") (pinfunction "2_2") (pintype "passive"))
      (node (ref "C20") (pin "2") (pinfunction "2_2") (pintype "passive"))
      (node (ref "C21") (pin "2") (pinfunction "2_2") (pintype "passive"))
      (node (ref "C22") (pin "2") (pinfunction "2_2") (pintype "passive"))
      (node (ref "C25") (pin "2") (pinfunction "2_2") (pintype "passive"))
      (node (ref "C26") (pin "2") (pinfunction "2_2") (pintype "passive"))
      (node (ref "C27") (pin "2") (pinfunction "2_2") (pintype "passive"))
      (node (ref "C28") (pin "2") (pinfunction "2_2") (pintype "passive"))
      (node (ref "C29") (pin "2") (pinfunction "2_2") (pintype "passive"))
      (node (ref "C3") (pin "2") (pinfunction "2_2") (pintype "passive"))
      (node (ref "C30") (pin "1") (pinfunction "1_1") (pintype "passive"))
      (node (ref "C31") (pin "1") (pinfunction "1_1") (pintype "passive"))
      (node (ref "C34") (pin "1") (pinfunction "1_1") (pintype "passive"))
      (node (ref "C35") (pin "1") (pinfunction "1_1") (pintype "passive"))
      (node (ref "C36") (pin "2") (pinfunction "2_2") (pintype "passive"))
      (node (ref "C37") (pin "2") (pinfunction "2_2") (pintype "passive"))
      (node (ref "C38") (pin "2") (pinfunction "2_2") (pintype "passive"))
      (node (ref "C39") (pin "2") (pinfunction "2_2") (pintype "passive"))
      (node (ref "C4") (pin "2") (pinfunction "2_2") (pintype "passive"))
      (node (ref "C40") (pin "1") (pinfunction "1_1") (pintype "passive"))
      (node (ref "C41") (pin "1") (pinfunction "1_1") (pintype "passive"))
      (node (ref "C42") (pin "2") (pinfunction "2_2") (pintype "passive"))
      (node (ref "C43") (pin "2") (pinfunction "2_2") (pintype "passive"))
      (node (ref "C44") (pin "2") (pinfunction "2_2") (pintype "passive"))
      (node (ref "C45") (pin "2") (pinfunction "2_2") (pintype "passive"))
      (node (ref "C46") (pin "2") (pinfunction "2_2") (pintype "passive"))
      (node (ref "C47") (pin "2") (pinfunction "2_2") (pintype "passive"))
      (node (ref "C48") (pin "2") (pinfunction "2_2") (pintype "passive"))
      (node (ref "C49") (pin "2") (pinfunction "2_2") (pintype "passive"))
      (node (ref "C50") (pin "2") (pinfunction "2_2") (pintype "passive"))
      (node (ref "C51") (pin "2") (pinfunction "2_2") (pintype "passive"))
      (node (ref "C52") (pin "1") (pinfunction "1_1") (pintype "passive"))
      (node (ref "C53") (pin "1") (pinfunction "1_1") (pintype "passive"))
      (node (ref "C54") (pin "+") (pinfunction "+_+") (pintype "passive"))
      (node (ref "C55") (pin "-") (pinfunction "-_-") (pintype "passive"))
      (node (ref "C56") (pin "2") (pinfunction "2_2") (pintype "passive"))
      (node (ref "C57") (pin "2") (pinfunction "2_2") (pintype "passive"))
      (node (ref "C58") (pin "1") (pinfunction "1_1") (pintype "passive"))
      (node (ref "C59") (pin "1") (pinfunction "1_1") (pintype "passive"))
      (node (ref "C60") (pin "2") (pinfunction "2_2") (pintype "passive"))
      (node (ref "C61") (pin "2") (pinfunction "2_2") (pintype "passive"))
      (node (ref "C66") (pin "2") (pinfunction "2_2") (pintype "passive"))
      (node (ref "C67") (pin "1") (pinfunction "1_1") (pintype "passive"))
      (node (ref "C68") (pin "2") (pinfunction "2_2") (pintype "passive"))
      (node (ref "C69") (pin "1") (pinfunction "1_1") (pintype "passive"))
      (node (ref "C7") (pin "1") (pinfunction "1_1") (pintype "passive"))
      (node (ref "C70") (pin "2") (pinfunction "2_2") (pintype "passive"))
      (node (ref "C71") (pin "2") (pinfunction "2_2") (pintype "passive"))
      (node (ref "C74") (pin "2") (pinfunction "2_2") (pintype "passive"))
      (node (ref "C75") (pin "2") (pinfunction "2_2") (pintype "passive"))
      (node (ref "C76") (pin "2") (pinfunction "2_2") (pintype "passive"))
      (node (ref "C77") (pin "2") (pinfunction "2_2") (pintype "passive"))
      (node (ref "C78") (pin "2") (pinfunction "2_2") (pintype "passive"))
      (node (ref "C8") (pin "2") (pinfunction "2_2") (pintype "passive"))
      (node (ref "C81") (pin "2") (pinfunction "2_2") (pintype "passive"))
      (node (ref "C84") (pin "1") (pinfunction "1_1") (pintype "passive"))
      (node (ref "C85") (pin "1") (pinfunction "1_1") (pintype "passive"))
      (node (ref "C92") (pin "2") (pinfunction "2_2") (pintype "passive"))
      (node (ref "C93") (pin "1") (pinfunction "1_1") (pintype "passive"))
      (node (ref "C94") (pin "2") (pinfunction "2_2") (pintype "passive"))
      (node (ref "C95") (pin "1") (pinfunction "1_1") (pintype "passive"))
      (node (ref "C96") (pin "2") (pinfunction "2_2") (pintype "passive"))
      (node (ref "C97") (pin "1") (pinfunction "1_1") (pintype "passive"))
      (node (ref "C98") (pin "2") (pinfunction "2_2") (pintype "passive"))
      (node (ref "C99") (pin "1") (pinfunction "1_1") (pintype "passive"))
      (node (ref "D11") (pin "C") (pinfunction "C_C") (pintype "passive"))
      (node (ref "D12") (pin "A") (pinfunction "A_A") (pintype "passive"))
      (node (ref "D13") (pin "A") (pinfunction "A_A") (pintype "passive"))
      (node (ref "D14") (pin "C") (pinfunction "C_C") (pintype "passive"))
      (node (ref "D15") (pin "A") (pinfunction "A_A") (pintype "passive"))
      (node (ref "D16") (pin "C") (pinfunction "C_C") (pintype "passive"))
      (node (ref "D17") (pin "A") (pinfunction "A_A") (pintype "passive"))
      (node (ref "D18") (pin "C") (pinfunction "C_C") (pintype "passive"))
      (node (ref "D20") (pin "C") (pinfunction "C_C") (pintype "passive"))
      (node (ref "D49") (pin "1") (pinfunction "A_1") (pintype "passive"))
      (node (ref "D50") (pin "1") (pinfunction "A_1") (pintype "passive"))
      (node (ref "D51") (pin "1") (pinfunction "A_1") (pintype "passive"))
      (node (ref "D52") (pin "1") (pinfunction "A_1") (pintype "passive"))
      (node (ref "D53") (pin "1") (pinfunction "A_1") (pintype "passive"))
      (node (ref "D54") (pin "1") (pinfunction "A_1") (pintype "passive"))
      (node (ref "D55") (pin "1") (pinfunction "A_1") (pintype "passive"))
      (node (ref "D56") (pin "1") (pinfunction "A_1") (pintype "passive"))
      (node (ref "D57") (pin "1") (pinfunction "A_1") (pintype "passive"))
      (node (ref "D58") (pin "1") (pinfunction "A_1") (pintype "passive"))
      (node (ref "D59") (pin "1") (pinfunction "A_1") (pintype "passive"))
      (node (ref "D60") (pin "1") (pinfunction "A_1") (pintype "passive"))
      (node (ref "D61") (pin "1") (pinfunction "A_1") (pintype "passive"))
      (node (ref "IC1") (pin "10") (pinfunction "+IN_10") (pintype "input"))
      (node (ref "IC1") (pin "12") (pinfunction "+IN_12") (pintype "input"))
      (node (ref "IC1") (pin "5") (pinfunction "+IN_5") (pintype "input"))
      (node (ref "IC10") (pin "1") (pinfunction "C_1") (pintype "passive"))
      (node (ref "IC11") (pin "2") (pinfunction "A_2") (pintype "passive"))
      (node (ref "IC12") (pin "8") (pinfunction "GND_8") (pintype "power_in"))
      (node (ref "IC13") (pin "8") (pinfunction "GND_8") (pintype "power_in"))
      (node (ref "IC14") (pin "10") (pinfunction "+IN_10") (pintype "input"))
      (node (ref "IC14") (pin "12") (pinfunction "+IN_12") (pintype "input"))
      (node (ref "IC14") (pin "3") (pinfunction "+IN_3") (pintype "input"))
      (node (ref "IC14") (pin "5") (pinfunction "+IN_5") (pintype "input"))
      (node (ref "IC15") (pin "10") (pinfunction "+IN_10") (pintype "input"))
      (node (ref "IC15") (pin "12") (pinfunction "+IN_12") (pintype "input"))
      (node (ref "IC15") (pin "3") (pinfunction "+IN_3") (pintype "input"))
      (node (ref "IC15") (pin "5") (pinfunction "+IN_5") (pintype "input"))
      (node (ref "IC16") (pin "10") (pinfunction "IN_10") (pintype "input"))
      (node (ref "IC16") (pin "12") (pinfunction "OUT_12") (pintype "output"))
      (node (ref "IC16") (pin "8") (pinfunction "GND_8") (pintype "power_in"))
      (node (ref "IC17") (pin "5") (pinfunction "OUT_5") (pintype "output"))
      (node (ref "IC17") (pin "7") (pinfunction "IN_7") (pintype "input"))
      (node (ref "IC17") (pin "8") (pinfunction "GND_8") (pintype "power_in"))
      (node (ref "IC18") (pin "10") (pinfunction "+IN_10") (pintype "input"))
      (node (ref "IC18") (pin "12") (pinfunction "+IN_12") (pintype "input"))
      (node (ref "IC18") (pin "3") (pinfunction "+IN_3") (pintype "input"))
      (node (ref "IC18") (pin "5") (pinfunction "+IN_5") (pintype "input"))
      (node (ref "IC19") (pin "10") (pinfunction "+IN_10") (pintype "input"))
      (node (ref "IC19") (pin "12") (pinfunction "+IN_12") (pintype "input"))
      (node (ref "IC19") (pin "3") (pinfunction "+IN_3") (pintype "input"))
      (node (ref "IC19") (pin "5") (pinfunction "+IN_5") (pintype "input"))
      (node (ref "IC2") (pin "10") (pinfunction "+IN_10") (pintype "input"))
      (node (ref "IC2") (pin "3") (pinfunction "+IN_3") (pintype "input"))
      (node (ref "IC2") (pin "5") (pinfunction "+IN_5") (pintype "input"))
      (node (ref "IC20") (pin "10") (pinfunction "+IN_10") (pintype "input"))
      (node (ref "IC20") (pin "12") (pinfunction "+IN_12") (pintype "input"))
      (node (ref "IC20") (pin "3") (pinfunction "+IN_3") (pintype "input"))
      (node (ref "IC20") (pin "5") (pinfunction "+IN_5") (pintype "input"))
      (node (ref "IC21") (pin "10") (pinfunction "+IN_10") (pintype "input"))
      (node (ref "IC21") (pin "12") (pinfunction "+IN_12") (pintype "input"))
      (node (ref "IC21") (pin "3") (pinfunction "+IN_3") (pintype "input"))
      (node (ref "IC21") (pin "5") (pinfunction "+IN_5") (pintype "input"))
      (node (ref "IC3") (pin "10") (pinfunction "+IN_10") (pintype "input"))
      (node (ref "IC3") (pin "12") (pinfunction "+IN_12") (pintype "input"))
      (node (ref "IC3") (pin "3") (pinfunction "+IN_3") (pintype "input"))
      (node (ref "IC3") (pin "5") (pinfunction "+IN_5") (pintype "input"))
      (node (ref "IC4") (pin "8") (pinfunction "GND_8") (pintype "power_in"))
      (node (ref "IC5") (pin "8") (pinfunction "GND_8") (pintype "power_in"))
      (node (ref "IC8") (pin "10") (pinfunction "+IN_10") (pintype "input"))
      (node (ref "IC8") (pin "12") (pinfunction "+IN_12") (pintype "input"))
      (node (ref "IC8") (pin "3") (pinfunction "+IN_3") (pintype "input"))
      (node (ref "IC8") (pin "5") (pinfunction "+IN_5") (pintype "input"))
      (node (ref "IC9") (pin "3") (pinfunction "+IN_3") (pintype "input"))
      (node (ref "IC9") (pin "5") (pinfunction "+IN_5") (pintype "input"))
      (node (ref "J1") (pin "P1") (pinfunction "1_P1") (pintype "passive"))
      (node (ref "J1") (pin "P2") (pinfunction "2_P2") (pintype "passive"))
      (node (ref "J10") (pin "P1") (pinfunction "1_P1") (pintype "passive"))
      (node (ref "J10") (pin "P2") (pinfunction "2_P2") (pintype "passive"))
      (node (ref "J11") (pin "P1") (pinfunction "1_P1") (pintype "passive"))
      (node (ref "J11") (pin "P2") (pinfunction "2_P2") (pintype "passive"))
      (node (ref "J12") (pin "P1") (pinfunction "1_P1") (pintype "passive"))
      (node (ref "J13") (pin "P1") (pinfunction "1_P1") (pintype "passive"))
      (node (ref "J14") (pin "P1") (pinfunction "1_P1") (pintype "passive"))
      (node (ref "J15") (pin "P1") (pinfunction "1_P1") (pintype "passive"))
      (node (ref "J15") (pin "P2") (pinfunction "2_P2") (pintype "passive"))
      (node (ref "J16") (pin "P1") (pinfunction "1_P1") (pintype "passive"))
      (node (ref "J2") (pin "P1") (pinfunction "1_P1") (pintype "passive"))
      (node (ref "J2") (pin "P2") (pinfunction "2_P2") (pintype "passive"))
      (node (ref "J3") (pin "P1") (pinfunction "1_P1") (pintype "passive"))
      (node (ref "J4") (pin "P1") (pinfunction "1_P1") (pintype "passive"))
      (node (ref "J5") (pin "P1") (pinfunction "1_P1") (pintype "passive"))
      (node (ref "J5") (pin "P2") (pinfunction "2_P2") (pintype "passive"))
      (node (ref "J6") (pin "P1") (pinfunction "1_P1") (pintype "passive"))
      (node (ref "J6") (pin "P2") (pinfunction "2_P2") (pintype "passive"))
      (node (ref "J7") (pin "P1") (pinfunction "1_P1") (pintype "passive"))
      (node (ref "J7") (pin "P2") (pinfunction "2_P2") (pintype "passive"))
      (node (ref "J8") (pin "P1") (pinfunction "1_P1") (pintype "passive"))
      (node (ref "J9") (pin "P1") (pinfunction "1_P1") (pintype "passive"))
      (node (ref "JP1") (pin "3") (pinfunction "3_3") (pintype "passive"))
      (node (ref "JP1") (pin "4") (pinfunction "4_4") (pintype "passive"))
      (node (ref "JP1") (pin "5") (pinfunction "5_5") (pintype "passive"))
      (node (ref "JP1") (pin "6") (pinfunction "6_6") (pintype "passive"))
      (node (ref "JP1") (pin "7") (pinfunction "7_7") (pintype "passive"))
      (node (ref "JP1") (pin "8") (pinfunction "8_8") (pintype "passive"))
      (node (ref "R1") (pin "2") (pinfunction "2_2") (pintype "passive"))
      (node (ref "R127") (pin "P$3") (pinfunction "A_P$3") (pintype "passive"))
      (node (ref "R128") (pin "P$1") (pinfunction "E_P$1") (pintype "passive"))
      (node (ref "R130") (pin "P$3") (pinfunction "A_P$3") (pintype "passive"))
      (node (ref "R14") (pin "P$3") (pinfunction "A_P$3") (pintype "passive"))
      (node (ref "R15") (pin "P$3") (pinfunction "A_P$3") (pintype "passive"))
      (node (ref "R17") (pin "P$3") (pinfunction "A_P$3") (pintype "passive"))
      (node (ref "R18") (pin "P$3") (pinfunction "A_P$3") (pintype "passive"))
      (node (ref "R199") (pin "1") (pinfunction "1_1") (pintype "passive"))
      (node (ref "R2") (pin "2") (pinfunction "2_2") (pintype "passive"))
      (node (ref "R200") (pin "1") (pinfunction "1_1") (pintype "passive"))
      (node (ref "R38") (pin "1") (pinfunction "1_1") (pintype "passive"))
      (node (ref "R41") (pin "1") (pinfunction "1_1") (pintype "passive"))
      (node (ref "R63") (pin "2") (pinfunction "2_2") (pintype "passive"))
      (node (ref "R80") (pin "P$2") (pinfunction "S_P$2") (pintype "passive"))
      (node (ref "R81") (pin "P$2") (pinfunction "S_P$2") (pintype "passive"))
      (node (ref "R86") (pin "P$1") (pinfunction "E_P$1") (pintype "passive"))
      (node (ref "R87") (pin "P$1") (pinfunction "E_P$1") (pintype "passive"))
      (node (ref "SW1") (pin "L2") (pinfunction "L2_L2") (pintype "passive"))
    )
    (net (code "7") (name "HP_1") (class "Default")
      (node (ref "IC14") (pin "7") (pinfunction "OUT_7") (pintype "output"))
      (node (ref "R115") (pin "2") (pinfunction "2_2") (pintype "passive"))
      (node (ref "R132") (pin "1") (pinfunction "1_1") (pintype "passive"))
      (node (ref "R96") (pin "1") (pinfunction "1_1") (pintype "passive"))
    )
    (net (code "8") (name "HP_2") (class "Default")
      (node (ref "IC15") (pin "8") (pinfunction "OUT_8") (pintype "output"))
      (node (ref "R117") (pin "2") (pinfunction "2_2") (pintype "passive"))
      (node (ref "R126") (pin "1") (pinfunction "1_1") (pintype "passive"))
      (node (ref "R97") (pin "1") (pinfunction "1_1") (pintype "passive"))
    )
    (net (code "9") (name "IN_1") (class "Default")
      (node (ref "C6") (pin "2") (pinfunction "2_2") (pintype "passive"))
      (node (ref "C79") (pin "1") (pinfunction "1_1") (pintype "passive"))
      (node (ref "IC2") (pin "1") (pinfunction "OUT_1") (pintype "output"))
      (node (ref "R114") (pin "1") (pinfunction "1_1") (pintype "passive"))
      (node (ref "R5") (pin "2") (pinfunction "2_2") (pintype "passive"))
    )
    (net (code "10") (name "IN_2") (class "Default")
      (node (ref "C5") (pin "2") (pinfunction "2_2") (pintype "passive"))
      (node (ref "C80") (pin "1") (pinfunction "1_1") (pintype "passive"))
      (node (ref "IC1") (pin "14") (pinfunction "OUT_14") (pintype "output"))
      (node (ref "R121") (pin "1") (pinfunction "1_1") (pintype "passive"))
      (node (ref "R6") (pin "2") (pinfunction "2_2") (pintype "passive"))
    )
    (net (code "11") (name "IN_2_NORMALIZATION") (class "Default")
      (node (ref "J16") (pin "P2") (pinfunction "2_P2") (pintype "passive"))
      (node (ref "R194") (pin "2") (pinfunction "2_2") (pintype "passive"))
    )
    (net (code "12") (name "LP_1") (class "Default")
      (node (ref "C63") (pin "2") (pinfunction "2_2") (pintype "passive"))
      (node (ref "C72") (pin "2") (pinfunction "2_2") (pintype "passive"))
      (node (ref "IC14") (pin "14") (pinfunction "OUT_14") (pintype "output"))
      (node (ref "R110") (pin "2") (pinfunction "2_2") (pintype "passive"))
      (node (ref "R111") (pin "1") (pinfunction "1_1") (pintype "passive"))
      (node (ref "R173") (pin "1") (pinfunction "1_1") (pintype "passive"))
    )
    (net (code "13") (name "LP_2") (class "Default")
      (node (ref "C64") (pin "2") (pinfunction "2_2") (pintype "passive"))
      (node (ref "C73") (pin "2") (pinfunction "2_2") (pintype "passive"))
      (node (ref "IC15") (pin "1") (pinfunction "OUT_1") (pintype "output"))
      (node (ref "R112") (pin "1") (pinfunction "1_1") (pintype "passive"))
      (node (ref "R113") (pin "2") (pinfunction "2_2") (pintype "passive"))
      (node (ref "R174") (pin "1") (pinfunction "1_1") (pintype "passive"))
    )
    (net (code "14") (name "MORPH_CV_1") (class "Default")
      (node (ref "D53") (pin "2") (pinfunction "C_2") (pintype "passive"))
      (node (ref "J1") (pin "P3") (pinfunction "3_P3") (pintype "passive"))
      (node (ref "R151") (pin "1") (pinfunction "1_1") (pintype "passive"))
      (node (ref "R160") (pin "1") (pinfunction "1_1") (pintype "passive"))
    )
    (net (code "15") (name "MORPH_CV_2") (class "Default")
      (node (ref "D54") (pin "2") (pinfunction "C_2") (pintype "passive"))
      (node (ref "J2") (pin "P3") (pinfunction "3_P3") (pintype "passive"))
      (node (ref "R152") (pin "1") (pinfunction "1_1") (pintype "passive"))
      (node (ref "R159") (pin "1") (pinfunction "1_1") (pintype "passive"))
    )
    (net (code "16") (name "MORPH_POT_1") (class "Default")
      (node (ref "R127") (pin "P$2") (pinfunction "S_P$2") (pintype "passive"))
      (node (ref "R143") (pin "1") (pinfunction "1_1") (pintype "passive"))
      (node (ref "R176") (pin "1") (pinfunction "1_1") (pintype "passive"))
    )
    (net (code "17") (name "MORPH_POT_2") (class "Default")
      (node (ref "R130") (pin "P$2") (pinfunction "S_P$2") (pintype "passive"))
      (node (ref "R144") (pin "1") (pinfunction "1_1") (pintype "passive"))
      (node (ref "R175") (pin "1") (pinfunction "1_1") (pintype "passive"))
    )
    (net (code "18") (name "Net-(C18-Pad1)") (class "Default")
      (node (ref "C18") (pin "1") (pinfunction "1_1") (pintype "passive"))
      (node (ref "R37") (pin "1") (pinfunction "1_1") (pintype "passive"))
    )
    (net (code "19") (name "Net-(C19-Pad1)") (class "Default")
      (node (ref "C19") (pin "1") (pinfunction "1_1") (pintype "passive"))
      (node (ref "R45") (pin "1") (pinfunction "1_1") (pintype "passive"))
    )
    (net (code "20") (name "Net-(C20-Pad1)") (class "Default")
      (node (ref "C20") (pin "1") (pinfunction "1_1") (pintype "passive"))
      (node (ref "R39") (pin "1") (pinfunction "1_1") (pintype "passive"))
    )
    (net (code "21") (name "Net-(C21-Pad1)") (class "Default")
      (node (ref "C21") (pin "1") (pinfunction "1_1") (pintype "passive"))
      (node (ref "R36") (pin "1") (pinfunction "1_1") (pintype "passive"))
    )
    (net (code "22") (name "Net-(C22-Pad1)") (class "Default")
      (node (ref "C22") (pin "1") (pinfunction "1_1") (pintype "passive"))
      (node (ref "R40") (pin "1") (pinfunction "1_1") (pintype "passive"))
    )
    (net (code "23") (name "Net-(C25-Pad1)") (class "Default")
      (node (ref "C25") (pin "1") (pinfunction "1_1") (pintype "passive"))
      (node (ref "R48") (pin "1") (pinfunction "1_1") (pintype "passive"))
    )
    (net (code "24") (name "Net-(C26-Pad1)") (class "Default")
      (node (ref "C26") (pin "1") (pinfunction "1_1") (pintype "passive"))
      (node (ref "R49") (pin "1") (pinfunction "1_1") (pintype "passive"))
    )
    (net (code "25") (name "Net-(C28-Pad1)") (class "Default")
      (node (ref "C28") (pin "1") (pinfunction "1_1") (pintype "passive"))
      (node (ref "R47") (pin "1") (pinfunction "1_1") (pintype "passive"))
    )
    (net (code "26") (name "Net-(C48-Pad1)") (class "Default")
      (node (ref "C48") (pin "1") (pinfunction "1_1") (pintype "passive"))
      (node (ref "R95") (pin "1") (pinfunction "1_1") (pintype "passive"))
    )
    (net (code "27") (name "Net-(C49-Pad1)") (class "Default")
      (node (ref "C49") (pin "1") (pinfunction "1_1") (pintype "passive"))
      (node (ref "R94") (pin "1") (pinfunction "1_1") (pintype "passive"))
    )
    (net (code "28") (name "Net-(C50-Pad1)") (class "Default")
      (node (ref "C50") (pin "1") (pinfunction "1_1") (pintype "passive"))
      (node (ref "R100") (pin "1") (pinfunction "1_1") (pintype "passive"))
    )
    (net (code "29") (name "Net-(C51-Pad1)") (class "Default")
      (node (ref "C51") (pin "1") (pinfunction "1_1") (pintype "passive"))
      (node (ref "R101") (pin "1") (pinfunction "1_1") (pintype "passive"))
    )
    (net (code "30") (name "Net-(C56-Pad1)") (class "Default")
      (node (ref "C56") (pin "1") (pinfunction "1_1") (pintype "passive"))
      (node (ref "R102") (pin "1") (pinfunction "1_1") (pintype "passive"))
    )
    (net (code "31") (name "Net-(C57-Pad1)") (class "Default")
      (node (ref "C57") (pin "1") (pinfunction "1_1") (pintype "passive"))
      (node (ref "R103") (pin "1") (pinfunction "1_1") (pintype "passive"))
    )
    (net (code "32") (name "Net-(C60-Pad1)") (class "Default")
      (node (ref "C60") (pin "1") (pinfunction "1_1") (pintype "passive"))
      (node (ref "R107") (pin "1") (pinfunction "1_1") (pintype "passive"))
    )
    (net (code "33") (name "Net-(C61-Pad1)") (class "Default")
      (node (ref "C61") (pin "1") (pinfunction "1_1") (pintype "passive"))
      (node (ref "R105") (pin "1") (pinfunction "1_1") (pintype "passive"))
    )
    (net (code "34") (name "Net-(C74-Pad1)") (class "Default")
      (node (ref "C74") (pin "1") (pinfunction "1_1") (pintype "passive"))
      (node (ref "R133") (pin "1") (pinfunction "1_1") (pintype "passive"))
    )
    (net (code "35") (name "Net-(C75-Pad1)") (class "Default")
      (node (ref "C75") (pin "1") (pinfunction "1_1") (pintype "passive"))
      (node (ref "R134") (pin "1") (pinfunction "1_1") (pintype "passive"))
    )
    (net (code "36") (name "Net-(C76-Pad1)") (class "Default")
      (node (ref "C76") (pin "1") (pinfunction "1_1") (pintype "passive"))
      (node (ref "R135") (pin "1") (pinfunction "1_1") (pintype "passive"))
    )
    (net (code "37") (name "Net-(C77-Pad1)") (class "Default")
      (node (ref "C77") (pin "1") (pinfunction "1_1") (pintype "passive"))
      (node (ref "R136") (pin "1") (pinfunction "1_1") (pintype "passive"))
    )
    (net (code "38") (name "Net-(C78-Pad1)") (class "Default")
      (node (ref "C78") (pin "1") (pinfunction "1_1") (pintype "passive"))
      (node (ref "R137") (pin "1") (pinfunction "1_1") (pintype "passive"))
    )
    (net (code "39") (name "Net-(C79-Pad2)") (class "Default")
      (node (ref "C79") (pin "2") (pinfunction "2_2") (pintype "passive"))
      (node (ref "R199") (pin "2") (pinfunction "2_2") (pintype "passive"))
      (node (ref "R7") (pin "1") (pinfunction "1_1") (pintype "passive"))
    )
    (net (code "40") (name "Net-(C80-Pad2)") (class "Default")
      (node (ref "C80") (pin "2") (pinfunction "2_2") (pintype "passive"))
      (node (ref "R200") (pin "2") (pinfunction "2_2") (pintype "passive"))
      (node (ref "R8") (pin "1") (pinfunction "1_1") (pintype "passive"))
    )
    (net (code "41") (name "Net-(C81-Pad1)") (class "Default")
      (node (ref "C81") (pin "1") (pinfunction "1_1") (pintype "passive"))
      (node (ref "R138") (pin "1") (pinfunction "1_1") (pintype "passive"))
    )
    (net (code "42") (name "Net-(D3-PadC)") (class "Default")
      (node (ref "D3") (pin "C") (pinfunction "C_C") (pintype "passive"))
      (node (ref "D6") (pin "C") (pinfunction "C_C") (pintype "passive"))
    )
    (net (code "43") (name "Net-(D4-PadC)") (class "Default")
      (node (ref "D4") (pin "C") (pinfunction "C_C") (pintype "passive"))
      (node (ref "D5") (pin "C") (pinfunction "C_C") (pintype "passive"))
    )
    (net (code "44") (name "Net-(D19-PadA)") (class "Default")
      (node (ref "D19") (pin "A") (pinfunction "A_A") (pintype "passive"))
      (node (ref "JP1") (pin "10") (pinfunction "10_10") (pintype "passive"))
      (node (ref "JP1") (pin "9") (pinfunction "9_9") (pintype "passive"))
    )
    (net (code "45") (name "Net-(D19-PadC)") (class "Default")
      (node (ref "D19") (pin "C") (pinfunction "C_C") (pintype "passive"))
      (node (ref "L2") (pin "2") (pinfunction "2_2") (pintype "passive"))
    )
    (net (code "46") (name "Net-(D21-PadC)") (class "Default")
      (node (ref "D21") (pin "C") (pinfunction "C_C") (pintype "passive"))
      (node (ref "D24") (pin "C") (pinfunction "C_C") (pintype "passive"))
    )
    (net (code "47") (name "Net-(D22-PadC)") (class "Default")
      (node (ref "D22") (pin "C") (pinfunction "C_C") (pintype "passive"))
      (node (ref "D23") (pin "C") (pinfunction "C_C") (pintype "passive"))
    )
    (net (code "48") (name "Net-(D37-PadC)") (class "Default")
      (node (ref "D37") (pin "C") (pinfunction "C_C") (pintype "passive"))
      (node (ref "D39") (pin "A") (pinfunction "A_A") (pintype "passive"))
    )
    (net (code "49") (name "Net-(D38-PadC)") (class "Default")
      (node (ref "D38") (pin "C") (pinfunction "C_C") (pintype "passive"))
      (node (ref "D40") (pin "A") (pinfunction "A_A") (pintype "passive"))
    )
    (net (code "50") (name "Net-(D39-PadC)") (class "Default")
      (node (ref "D39") (pin "C") (pinfunction "C_C") (pintype "passive"))
      (node (ref "D43") (pin "C") (pinfunction "C_C") (pintype "passive"))
    )
    (net (code "51") (name "Net-(D40-PadC)") (class "Default")
      (node (ref "D40") (pin "C") (pinfunction "C_C") (pintype "passive"))
      (node (ref "D44") (pin "C") (pinfunction "C_C") (pintype "passive"))
    )
    (net (code "52") (name "Net-(D41-PadC)") (class "Default")
      (node (ref "D41") (pin "C") (pinfunction "C_C") (pintype "passive"))
      (node (ref "D44") (pin "A") (pinfunction "A_A") (pintype "passive"))
    )
    (net (code "53") (name "Net-(D42-PadC)") (class "Default")
      (node (ref "D42") (pin "C") (pinfunction "C_C") (pintype "passive"))
      (node (ref "D43") (pin "A") (pinfunction "A_A") (pintype "passive"))
    )
    (net (code "54") (name "Net-(D50-C)") (class "Default")
      (node (ref "D50") (pin "2") (pinfunction "C_2") (pintype "passive"))
      (node (ref "J3") (pin "P3") (pinfunction "3_P3") (pintype "passive"))
      (node (ref "R22") (pin "1") (pinfunction "1_1") (pintype "passive"))
    )
    (net (code "55") (name "Net-(D51-C)") (class "Default")
      (node (ref "D51") (pin "2") (pinfunction "C_2") (pintype "passive"))
      (node (ref "J9") (pin "P3") (pinfunction "3_P3") (pintype "passive"))
      (node (ref "R19") (pin "1") (pinfunction "1_1") (pintype "passive"))
    )
    (net (code "56") (name "Net-(D52-C)") (class "Default")
      (node (ref "D52") (pin "2") (pinfunction "C_2") (pintype "passive"))
      (node (ref "J16") (pin "P3") (pinfunction "3_P3") (pintype "passive"))
      (node (ref "R34") (pin "1") (pinfunction "1_1") (pintype "passive"))
    )
    (net (code "57") (name "Net-(D55-C)") (class "Default")
      (node (ref "D55") (pin "2") (pinfunction "C_2") (pintype "passive"))
      (node (ref "J4") (pin "P3") (pinfunction "3_P3") (pintype "passive"))
      (node (ref "R183") (pin "1") (pinfunction "1_1") (pintype "passive"))
    )
    (net (code "58") (name "Net-(D56-C)") (class "Default")
      (node (ref "D56") (pin "2") (pinfunction "C_2") (pintype "passive"))
      (node (ref "J8") (pin "P3") (pinfunction "3_P3") (pintype "passive"))
      (node (ref "R189") (pin "1") (pinfunction "1_1") (pintype "passive"))
    )
    (net (code "59") (name "Net-(D57-C)") (class "Default")
      (node (ref "D57") (pin "2") (pinfunction "C_2") (pintype "passive"))
      (node (ref "J5") (pin "P3") (pinfunction "3_P3") (pintype "passive"))
      (node (ref "R185") (pin "1") (pinfunction "1_1") (pintype "passive"))
    )
    (net (code "60") (name "Net-(D58-C)") (class "Default")
      (node (ref "D58") (pin "2") (pinfunction "C_2") (pintype "passive"))
      (node (ref "J7") (pin "P3") (pinfunction "3_P3") (pintype "passive"))
      (node (ref "R187") (pin "1") (pinfunction "1_1") (pintype "passive"))
    )
    (net (code "61") (name "Net-(D59-C)") (class "Default")
      (node (ref "D59") (pin "2") (pinfunction "C_2") (pintype "passive"))
      (node (ref "J11") (pin "P3") (pinfunction "3_P3") (pintype "passive"))
      (node (ref "R161") (pin "1") (pinfunction "1_1") (pintype "passive"))
    )
    (net (code "62") (name "Net-(D60-C)") (class "Default")
      (node (ref "D60") (pin "2") (pinfunction "C_2") (pintype "passive"))
      (node (ref "J15") (pin "P3") (pinfunction "3_P3") (pintype "passive"))
      (node (ref "R162") (pin "1") (pinfunction "1_1") (pintype "passive"))
    )
    (net (code "63") (name "Net-(D61-C)") (class "Default")
      (node (ref "D61") (pin "2") (pinfunction "C_2") (pintype "passive"))
      (node (ref "J6") (pin "P3") (pinfunction "3_P3") (pintype "passive"))
      (node (ref "R186") (pin "1") (pinfunction "1_1") (pintype "passive"))
    )
    (net (code "64") (name "Net-(IC1A-+IN)") (class "Default")
      (node (ref "IC1") (pin "3") (pinfunction "+IN_3") (pintype "input"))
      (node (ref "R8") (pin "2") (pinfunction "2_2") (pintype "passive"))
    )
    (net (code "65") (name "Net-(IC1A--IN)") (class "Default")
      (node (ref "D2") (pin "A") (pinfunction "A_A") (pintype "passive"))
      (node (ref "IC1") (pin "2") (pinfunction "-IN_2") (pintype "input"))
      (node (ref "LED2") (pin "K") (pinfunction "C_K") (pintype "passive"))
      (node (ref "R2") (pin "1") (pinfunction "1_1") (pintype "passive"))
    )
    (net (code "66") (name "Net-(IC1A-OUT)") (class "Default")
      (node (ref "D2") (pin "C") (pinfunction "C_C") (pintype "passive"))
      (node (ref "IC1") (pin "1") (pinfunction "OUT_1") (pintype "output"))
      (node (ref "LED2") (pin "A") (pinfunction "A_A") (pintype "passive"))
    )
    (net (code "67") (name "Net-(IC1B--IN)") (class "Default")
      (node (ref "C13") (pin "1") (pinfunction "1_1") (pintype "passive"))
      (node (ref "D6") (pin "A") (pinfunction "A_A") (pintype "passive"))
      (node (ref "IC1") (pin "6") (pinfunction "-IN_6") (pintype "input"))
      (node (ref "IC5") (pin "4") (pinfunction "OUT_4") (pintype "output"))
      (node (ref "R25") (pin "1") (pinfunction "1_1") (pintype "passive"))
    )
    (net (code "68") (name "Net-(IC1B-OUT)") (class "Default")
      (node (ref "C13") (pin "2") (pinfunction "2_2") (pintype "passive"))
      (node (ref "D3") (pin "A") (pinfunction "A_A") (pintype "passive"))
      (node (ref "IC1") (pin "7") (pinfunction "OUT_7") (pintype "output"))
      (node (ref "R25") (pin "2") (pinfunction "2_2") (pintype "passive"))
      (node (ref "R55") (pin "1") (pinfunction "1_1") (pintype "passive"))
      (node (ref "R64") (pin "1") (pinfunction "1_1") (pintype "passive"))
      (node (ref "R91") (pin "1") (pinfunction "1_1") (pintype "passive"))
    )
    (net (code "69") (name "Net-(IC1C--IN)") (class "Default")
      (node (ref "C9") (pin "1") (pinfunction "1_1") (pintype "passive"))
      (node (ref "IC1") (pin "9") (pinfunction "-IN_9") (pintype "input"))
      (node (ref "IC5") (pin "13") (pinfunction "OUT_13") (pintype "output"))
      (node (ref "R13") (pin "2") (pinfunction "2_2") (pintype "passive"))
      (node (ref "R19") (pin "2") (pinfunction "2_2") (pintype "passive"))
      (node (ref "R20") (pin "2") (pinfunction "2_2") (pintype "passive"))
    )
    (net (code "70") (name "Net-(IC1C-OUT)") (class "Default")
      (node (ref "C9") (pin "2") (pinfunction "2_2") (pintype "passive"))
      (node (ref "IC1") (pin "8") (pinfunction "OUT_8") (pintype "output"))
      (node (ref "IC5") (pin "3") (pinfunction "CTRL_3") (pintype "input"))
      (node (ref "R26") (pin "2") (pinfunction "2_2") (pintype "passive"))
    )
    (net (code "71") (name "Net-(IC1D--IN)") (class "Default")
      (node (ref "C5") (pin "1") (pinfunction "1_1") (pintype "passive"))
      (node (ref "IC1") (pin "13") (pinfunction "-IN_13") (pintype "input"))
      (node (ref "R4") (pin "2") (pinfunction "2_2") (pintype "passive"))
      (node (ref "R6") (pin "1") (pinfunction "1_1") (pintype "passive"))
      (node (ref "R9") (pin "2") (pinfunction "2_2") (pintype "passive"))
    )
    (net (code "72") (name "Net-(IC2A--IN)") (class "Default")
      (node (ref "C6") (pin "1") (pinfunction "1_1") (pintype "passive"))
      (node (ref "IC2") (pin "2") (pinfunction "-IN_2") (pintype "input"))
      (node (ref "R10") (pin "2") (pinfunction "2_2") (pintype "passive"))
      (node (ref "R3") (pin "2") (pinfunction "2_2") (pintype "passive"))
      (node (ref "R5") (pin "1") (pinfunction "1_1") (pintype "passive"))
    )
    (net (code "73") (name "Net-(IC2B--IN)") (class "Default")
      (node (ref "C10") (pin "1") (pinfunction "1_1") (pintype "passive"))
      (node (ref "IC2") (pin "6") (pinfunction "-IN_6") (pintype "input"))
      (node (ref "IC4") (pin "4") (pinfunction "OUT_4") (pintype "output"))
      (node (ref "R11") (pin "2") (pinfunction "2_2") (pintype "passive"))
      (node (ref "R21") (pin "2") (pinfunction "2_2") (pintype "passive"))
      (node (ref "R22") (pin "2") (pinfunction "2_2") (pintype "passive"))
    )
    (net (code "74") (name "Net-(IC2B-OUT)") (class "Default")
      (node (ref "C10") (pin "2") (pinfunction "2_2") (pintype "passive"))
      (node (ref "IC2") (pin "7") (pinfunction "OUT_7") (pintype "output"))
      (node (ref "IC4") (pin "14") (pinfunction "CTRL_14") (pintype "input"))
      (node (ref "R27") (pin "2") (pinfunction "2_2") (pintype "passive"))
    )
    (net (code "75") (name "Net-(IC2C--IN)") (class "Default")
      (node (ref "C12") (pin "1") (pinfunction "1_1") (pintype "passive"))
      (node (ref "D5") (pin "A") (pinfunction "A_A") (pintype "passive"))
      (node (ref "IC2") (pin "9") (pinfunction "-IN_9") (pintype "input"))
      (node (ref "IC4") (pin "13") (pinfunction "OUT_13") (pintype "output"))
      (node (ref "R24") (pin "1") (pinfunction "1_1") (pintype "passive"))
    )
    (net (code "76") (name "Net-(IC2C-OUT)") (class "Default")
      (node (ref "C12") (pin "2") (pinfunction "2_2") (pintype "passive"))
      (node (ref "D4") (pin "A") (pinfunction "A_A") (pintype "passive"))
      (node (ref "IC2") (pin "8") (pinfunction "OUT_8") (pintype "output"))
      (node (ref "R24") (pin "2") (pinfunction "2_2") (pintype "passive"))
      (node (ref "R61") (pin "1") (pinfunction "1_1") (pintype "passive"))
      (node (ref "R66") (pin "1") (pinfunction "1_1") (pintype "passive"))
      (node (ref "R89") (pin "1") (pinfunction "1_1") (pintype "passive"))
    )
    (net (code "77") (name "Net-(IC2D-+IN)") (class "Default")
      (node (ref "IC2") (pin "12") (pinfunction "+IN_12") (pintype "input"))
      (node (ref "R7") (pin "2") (pinfunction "2_2") (pintype "passive"))
    )
    (net (code "78") (name "Net-(IC2D--IN)") (class "Default")
      (node (ref "D1") (pin "A") (pinfunction "A_A") (pintype "passive"))
      (node (ref "IC2") (pin "13") (pinfunction "-IN_13") (pintype "input"))
      (node (ref "LED1") (pin "K") (pinfunction "C_K") (pintype "passive"))
      (node (ref "R1") (pin "1") (pinfunction "1_1") (pintype "passive"))
    )
    (net (code "79") (name "Net-(IC2D-OUT)") (class "Default")
      (node (ref "D1") (pin "C") (pinfunction "C_C") (pintype "passive"))
      (node (ref "IC2") (pin "14") (pinfunction "OUT_14") (pintype "output"))
      (node (ref "LED1") (pin "A") (pinfunction "A_A") (pintype "passive"))
    )
    (net (code "80") (name "Net-(IC3A--IN)") (class "Default")
      (node (ref "C11") (pin "1") (pinfunction "1_1") (pintype "passive"))
      (node (ref "IC3") (pin "2") (pinfunction "-IN_2") (pintype "input"))
      (node (ref "R12") (pin "2") (pinfunction "2_2") (pintype "passive"))
      (node (ref "R16") (pin "1") (pinfunction "1_1") (pintype "passive"))
      (node (ref "R179") (pin "P$1") (pinfunction "E_P$1") (pintype "passive"))
      (node (ref "R28") (pin "2") (pinfunction "2_2") (pintype "passive"))
      (node (ref "R29") (pin "2") (pinfunction "2_2") (pintype "passive"))
    )
    (net (code "81") (name "Net-(IC3B--IN)") (class "Default")
      (node (ref "C24") (pin "1") (pinfunction "1_1") (pintype "passive"))
      (node (ref "D7") (pin "A") (pinfunction "A_A") (pintype "passive"))
      (node (ref "IC3") (pin "6") (pinfunction "-IN_6") (pintype "input"))
      (node (ref "IC4") (pin "12") (pinfunction "OUT_12") (pintype "output"))
      (node (ref "R42") (pin "2") (pinfunction "2_2") (pintype "passive"))
    )
    (net (code "82") (name "Net-(IC3B-OUT)") (class "Default")
      (node (ref "D7") (pin "C") (pinfunction "C_C") (pintype "passive"))
      (node (ref "D9") (pin "A") (pinfunction "A_A") (pintype "passive"))
      (node (ref "IC3") (pin "7") (pinfunction "OUT_7") (pintype "output"))
    )
    (net (code "83") (name "Net-(IC3C--IN)") (class "Default")
      (node (ref "C23") (pin "1") (pinfunction "1_1") (pintype "passive"))
      (node (ref "D8") (pin "A") (pinfunction "A_A") (pintype "passive"))
      (node (ref "IC3") (pin "9") (pinfunction "-IN_9") (pintype "input"))
      (node (ref "IC5") (pin "5") (pinfunction "OUT_5") (pintype "output"))
      (node (ref "R43") (pin "2") (pinfunction "2_2") (pintype "passive"))
    )
    (net (code "84") (name "Net-(IC3C-OUT)") (class "Default")
      (node (ref "D10") (pin "A") (pinfunction "A_A") (pintype "passive"))
      (node (ref "D8") (pin "C") (pinfunction "C_C") (pintype "passive"))
      (node (ref "IC3") (pin "8") (pinfunction "OUT_8") (pintype "output"))
    )
    (net (code "85") (name "Net-(IC3D--IN)") (class "Default")
      (node (ref "IC3") (pin "13") (pinfunction "-IN_13") (pintype "input"))
      (node (ref "R179") (pin "P$3") (pinfunction "A_P$3") (pintype "passive"))
      (node (ref "R23") (pin "1") (pinfunction "1_1") (pintype "passive"))
    )
    (net (code "86") (name "Net-(IC3D-OUT)") (class "Default")
      (node (ref "IC3") (pin "14") (pinfunction "OUT_14") (pintype "output"))
      (node (ref "R12") (pin "1") (pinfunction "1_1") (pintype "passive"))
      (node (ref "R23") (pin "2") (pinfunction "2_2") (pintype "passive"))
    )
    (net (code "87") (name "Net-(IC4A-CTRL)") (class "Default")
      (node (ref "IC4") (pin "3") (pinfunction "CTRL_3") (pintype "input"))
      (node (ref "R27") (pin "1") (pinfunction "1_1") (pintype "passive"))
      (node (ref "R41") (pin "2") (pinfunction "2_2") (pintype "passive"))
    )
    (net (code "88") (name "Net-(IC4A-IN)") (class "Default")
      (node (ref "IC4") (pin "2") (pinfunction "IN_2") (pintype "input"))
      (node (ref "R32") (pin "2") (pinfunction "2_2") (pintype "passive"))
      (node (ref "R40") (pin "2") (pinfunction "2_2") (pintype "passive"))
    )
    (net (code "89") (name "Net-(IC4B-CTRL)") (class "Default")
      (node (ref "C24") (pin "2") (pinfunction "2_2") (pintype "passive"))
      (node (ref "D9") (pin "C") (pinfunction "C_C") (pintype "passive"))
      (node (ref "IC4") (pin "11") (pinfunction "CTRL_11") (pintype "input"))
      (node (ref "IC4") (pin "6") (pinfunction "CTRL_6") (pintype "input"))
    )
    (net (code "90") (name "Net-(IC4B-IN)") (class "Default")
      (node (ref "IC4") (pin "7") (pinfunction "IN_7") (pintype "input"))
      (node (ref "R48") (pin "2") (pinfunction "2_2") (pintype "passive"))
      (node (ref "R57") (pin "2") (pinfunction "2_2") (pintype "passive"))
      (node (ref "R71") (pin "2") (pinfunction "2_2") (pintype "passive"))
    )
    (net (code "91") (name "Net-(IC4B-OUT)") (class "Default")
      (node (ref "C33") (pin "1") (pinfunction "1_1") (pintype "passive"))
      (node (ref "IC4") (pin "5") (pinfunction "OUT_5") (pintype "output"))
      (node (ref "IC8") (pin "2") (pinfunction "-IN_2") (pintype "input"))
      (node (ref "R68") (pin "1") (pinfunction "1_1") (pintype "passive"))
      (node (ref "R70") (pin "2") (pinfunction "2_2") (pintype "passive"))
    )
    (net (code "92") (name "Net-(IC4C-IN)") (class "Default")
      (node (ref "IC4") (pin "10") (pinfunction "IN_10") (pintype "input"))
      (node (ref "R49") (pin "2") (pinfunction "2_2") (pintype "passive"))
      (node (ref "R52") (pin "2") (pinfunction "2_2") (pintype "passive"))
    )
    (net (code "93") (name "Net-(IC4D-IN)") (class "Default")
      (node (ref "IC4") (pin "15") (pinfunction "IN_15") (pintype "input"))
      (node (ref "R33") (pin "2") (pinfunction "2_2") (pintype "passive"))
      (node (ref "R36") (pin "2") (pinfunction "2_2") (pintype "passive"))
    )
    (net (code "94") (name "Net-(IC4E-MODE)") (class "Default")
      (node (ref "IC4") (pin "1") (pinfunction "MODE_1") (pintype "input"))
      (node (ref "R30") (pin "1") (pinfunction "1_1") (pintype "passive"))
    )
    (net (code "95") (name "Net-(IC5A-IN)") (class "Default")
      (node (ref "IC5") (pin "2") (pinfunction "IN_2") (pintype "input"))
      (node (ref "R34") (pin "2") (pinfunction "2_2") (pintype "passive"))
      (node (ref "R37") (pin "2") (pinfunction "2_2") (pintype "passive"))
    )
    (net (code "96") (name "Net-(IC5B-CTRL)") (class "Default")
      (node (ref "C23") (pin "2") (pinfunction "2_2") (pintype "passive"))
      (node (ref "D10") (pin "C") (pinfunction "C_C") (pintype "passive"))
      (node (ref "IC5") (pin "11") (pinfunction "CTRL_11") (pintype "input"))
      (node (ref "IC5") (pin "6") (pinfunction "CTRL_6") (pintype "input"))
    )
    (net (code "97") (name "Net-(IC5B-IN)") (class "Default")
      (node (ref "IC5") (pin "7") (pinfunction "IN_7") (pintype "input"))
      (node (ref "R47") (pin "2") (pinfunction "2_2") (pintype "passive"))
      (node (ref "R53") (pin "2") (pinfunction "2_2") (pintype "passive"))
    )
    (net (code "98") (name "Net-(IC5C-IN)") (class "Default")
      (node (ref "IC5") (pin "10") (pinfunction "IN_10") (pintype "input"))
      (node (ref "R44") (pin "2") (pinfunction "2_2") (pintype "passive"))
      (node (ref "R45") (pin "2") (pinfunction "2_2") (pintype "passive"))
      (node (ref "R46") (pin "2") (pinfunction "2_2") (pintype "passive"))
    )
    (net (code "99") (name "Net-(IC5C-OUT)") (class "Default")
      (node (ref "C32") (pin "1") (pinfunction "1_1") (pintype "passive"))
      (node (ref "IC5") (pin "12") (pinfunction "OUT_12") (pintype "output"))
      (node (ref "IC8") (pin "13") (pinfunction "-IN_13") (pintype "input"))
      (node (ref "R69") (pin "1") (pinfunction "1_1") (pintype "passive"))
      (node (ref "R73") (pin "2") (pinfunction "2_2") (pintype "passive"))
    )
    (net (code "100") (name "Net-(IC5D-CTRL)") (class "Default")
      (node (ref "IC5") (pin "14") (pinfunction "CTRL_14") (pintype "input"))
      (node (ref "R26") (pin "1") (pinfunction "1_1") (pintype "passive"))
      (node (ref "R38") (pin "2") (pinfunction "2_2") (pintype "passive"))
    )
    (net (code "101") (name "Net-(IC5D-IN)") (class "Default")
      (node (ref "IC5") (pin "15") (pinfunction "IN_15") (pintype "input"))
      (node (ref "R35") (pin "2") (pinfunction "2_2") (pintype "passive"))
      (node (ref "R39") (pin "2") (pinfunction "2_2") (pintype "passive"))
    )
    (net (code "102") (name "Net-(IC5E-MODE)") (class "Default")
      (node (ref "IC5") (pin "1") (pinfunction "MODE_1") (pintype "input"))
      (node (ref "R31") (pin "1") (pinfunction "1_1") (pintype "passive"))
    )
    (net (code "103") (name "Net-(IC6A-+IN)") (class "Default")
      (node (ref "D11") (pin "A") (pinfunction "A_A") (pintype "passive"))
      (node (ref "D17") (pin "C") (pinfunction "C_C") (pintype "passive"))
      (node (ref "IC6") (pin "3") (pinfunction "+IN_3") (pintype "input"))
      (node (ref "R65") (pin "2") (pinfunction "2_2") (pintype "passive"))
    )
    (net (code "104") (name "Net-(IC6A--IN)") (class "Default")
      (node (ref "IC6") (pin "2") (pinfunction "-IN_2") (pintype "input"))
      (node (ref "R50") (pin "2") (pinfunction "2_2") (pintype "passive"))
      (node (ref "R51") (pin "1") (pinfunction "1_1") (pintype "passive"))
    )
    (net (code "105") (name "Net-(IC6A-OUT)") (class "Default")
      (node (ref "IC6") (pin "1") (pinfunction "OUT_1") (pintype "output"))
      (node (ref "R51") (pin "2") (pinfunction "2_2") (pintype "passive"))
      (node (ref "R88") (pin "1") (pinfunction "1_1") (pintype "passive"))
    )
    (net (code "106") (name "Net-(IC6B-+IN)") (class "Default")
      (node (ref "D14") (pin "A") (pinfunction "A_A") (pintype "passive"))
      (node (ref "D15") (pin "C") (pinfunction "C_C") (pintype "passive"))
      (node (ref "IC6") (pin "5") (pinfunction "+IN_5") (pintype "input"))
      (node (ref "R66") (pin "2") (pinfunction "2_2") (pintype "passive"))
    )
    (net (code "107") (name "Net-(IC6B--IN)") (class "Default")
      (node (ref "IC6") (pin "6") (pinfunction "-IN_6") (pintype "input"))
      (node (ref "R58") (pin "1") (pinfunction "1_1") (pintype "passive"))
      (node (ref "R61") (pin "2") (pinfunction "2_2") (pintype "passive"))
    )
    (net (code "108") (name "Net-(IC6B-OUT)") (class "Default")
      (node (ref "IC6") (pin "7") (pinfunction "OUT_7") (pintype "output"))
      (node (ref "R50") (pin "1") (pinfunction "1_1") (pintype "passive"))
      (node (ref "R58") (pin "2") (pinfunction "2_2") (pintype "passive"))
      (node (ref "R65") (pin "1") (pinfunction "1_1") (pintype "passive"))
    )
    (net (code "109") (name "Net-(IC7A-+IN)") (class "Default")
      (node (ref "D12") (pin "C") (pinfunction "C_C") (pintype "passive"))
      (node (ref "D16") (pin "A") (pinfunction "A_A") (pintype "passive"))
      (node (ref "IC7") (pin "3") (pinfunction "+IN_3") (pintype "input"))
      (node (ref "R64") (pin "2") (pinfunction "2_2") (pintype "passive"))
    )
    (net (code "110") (name "Net-(IC7A--IN)") (class "Default")
      (node (ref "IC7") (pin "2") (pinfunction "-IN_2") (pintype "input"))
      (node (ref "R55") (pin "2") (pinfunction "2_2") (pintype "passive"))
      (node (ref "R56") (pin "1") (pinfunction "1_1") (pintype "passive"))
    )
    (net (code "111") (name "Net-(IC7A-OUT)") (class "Default")
      (node (ref "IC7") (pin "1") (pinfunction "OUT_1") (pintype "output"))
      (node (ref "R56") (pin "2") (pinfunction "2_2") (pintype "passive"))
      (node (ref "R60") (pin "1") (pinfunction "1_1") (pintype "passive"))
      (node (ref "R67") (pin "1") (pinfunction "1_1") (pintype "passive"))
    )
    (net (code "112") (name "Net-(IC7B-+IN)") (class "Default")
      (node (ref "D13") (pin "C") (pinfunction "C_C") (pintype "passive"))
      (node (ref "D18") (pin "A") (pinfunction "A_A") (pintype "passive"))
      (node (ref "IC7") (pin "5") (pinfunction "+IN_5") (pintype "input"))
      (node (ref "R67") (pin "2") (pinfunction "2_2") (pintype "passive"))
    )
    (net (code "113") (name "Net-(IC7B--IN)") (class "Default")
      (node (ref "IC7") (pin "6") (pinfunction "-IN_6") (pintype "input"))
      (node (ref "R59") (pin "1") (pinfunction "1_1") (pintype "passive"))
      (node (ref "R60") (pin "2") (pinfunction "2_2") (pintype "passive"))
    )
    (net (code "114") (name "Net-(IC7B-OUT)") (class "Default")
      (node (ref "IC7") (pin "7") (pinfunction "OUT_7") (pintype "output"))
      (node (ref "R59") (pin "2") (pinfunction "2_2") (pintype "passive"))
      (node (ref "R90") (pin "1") (pinfunction "1_1") (pintype "passive"))
    )
    (net (code "115") (name "Net-(IC8A-OUT)") (class "Default")
      (node (ref "C33") (pin "2") (pinfunction "2_2") (pintype "passive"))
      (node (ref "IC8") (pin "1") (pinfunction "OUT_1") (pintype "output"))
      (node (ref "R194") (pin "1") (pinfunction "1_1") (pintype "passive"))
      (node (ref "R68") (pin "2") (pinfunction "2_2") (pintype "passive"))
    )
    (net (code "116") (name "Net-(IC8B--IN)") (class "Default")
      (node (ref "IC8") (pin "6") (pinfunction "-IN_6") (pintype "input"))
      (node (ref "R140") (pin "1") (pinfunction "1_1") (pintype "passive"))
      (node (ref "R77") (pin "2") (pinfunction "2_2") (pintype "passive"))
      (node (ref "R79") (pin "1") (pinfunction "1_1") (pintype "passive"))
    )
    (net (code "117") (name "Net-(IC8B-OUT)") (class "Default")
      (node (ref "IC8") (pin "7") (pinfunction "OUT_7") (pintype "output"))
      (node (ref "R140") (pin "2") (pinfunction "2_2") (pintype "passive"))
      (node (ref "R73") (pin "1") (pinfunction "1_1") (pintype "passive"))
      (node (ref "R79") (pin "2") (pinfunction "2_2") (pintype "passive"))
    )
    (net (code "118") (name "Net-(IC8C--IN)") (class "Default")
      (node (ref "IC8") (pin "8") (pinfunction "OUT_8") (pintype "output"))
      (node (ref "IC8") (pin "9") (pinfunction "-IN_9") (pintype "input"))
    )
    (net (code "119") (name "Net-(IC9A--IN)") (class "Default")
      (node (ref "IC9") (pin "2") (pinfunction "-IN_2") (pintype "input"))
      (node (ref "R197") (pin "1") (pinfunction "1_1") (pintype "passive"))
      (node (ref "R72") (pin "1") (pinfunction "1_1") (pintype "passive"))
      (node (ref "R76") (pin "2") (pinfunction "2_2") (pintype "passive"))
    )
    (net (code "120") (name "Net-(IC9B--IN)") (class "Default")
      (node (ref "IC9") (pin "6") (pinfunction "-IN_6") (pintype "input"))
      (node (ref "R74") (pin "1") (pinfunction "1_1") (pintype "passive"))
      (node (ref "R78") (pin "2") (pinfunction "2_2") (pintype "passive"))
    )
    (net (code "121") (name "Net-(IC9B-OUT)") (class "Default")
      (node (ref "IC9") (pin "7") (pinfunction "OUT_7") (pintype "output"))
      (node (ref "R57") (pin "1") (pinfunction "1_1") (pintype "passive"))
      (node (ref "R74") (pin "2") (pinfunction "2_2") (pintype "passive"))
    )
    (net (code "122") (name "Net-(IC12A-CTRL)") (class "Default")
      (node (ref "C82") (pin "2") (pinfunction "2_2") (pintype "passive"))
      (node (ref "D25") (pin "C") (pinfunction "C_C") (pintype "passive"))
      (node (ref "IC12") (pin "14") (pinfunction "CTRL_14") (pintype "input"))
      (node (ref "IC12") (pin "3") (pinfunction "CTRL_3") (pintype "input"))
    )
    (net (code "123") (name "Net-(IC12A-IN)") (class "Default")
      (node (ref "IC12") (pin "2") (pinfunction "IN_2") (pintype "input"))
      (node (ref "R102") (pin "2") (pinfunction "2_2") (pintype "passive"))
      (node (ref "R96") (pin "2") (pinfunction "2_2") (pintype "passive"))
      (node (ref "R98") (pin "2") (pinfunction "2_2") (pintype "passive"))
    )
    (net (code "124") (name "Net-(IC12A-OUT)") (class "Default")
      (node (ref "IC12") (pin "4") (pinfunction "OUT_4") (pintype "output"))
      (node (ref "IC12") (pin "7") (pinfunction "IN_7") (pintype "input"))
      (node (ref "R104") (pin "2") (pinfunction "2_2") (pintype "passive"))
      (node (ref "R105") (pin "2") (pinfunction "2_2") (pintype "passive"))
    )
    (net (code "125") (name "Net-(IC12B-CTRL)") (class "Default")
      (node (ref "C100") (pin "2") (pinfunction "2_2") (pintype "passive"))
      (node (ref "D48") (pin "C") (pinfunction "C_C") (pintype "passive"))
      (node (ref "IC12") (pin "11") (pinfunction "CTRL_11") (pintype "input"))
      (node (ref "IC12") (pin "6") (pinfunction "CTRL_6") (pintype "input"))
    )
    (net (code "126") (name "Net-(IC12B-OUT)") (class "Default")
      (node (ref "C86") (pin "1") (pinfunction "1_1") (pintype "passive"))
      (node (ref "D41") (pin "A") (pinfunction "A_A") (pintype "passive"))
      (node (ref "IC12") (pin "5") (pinfunction "OUT_5") (pintype "output"))
      (node (ref "IC18") (pin "2") (pinfunction "-IN_2") (pintype "input"))
      (node (ref "R153") (pin "1") (pinfunction "1_1") (pintype "passive"))
      (node (ref "R173") (pin "2") (pinfunction "2_2") (pintype "passive"))
    )
    (net (code "127") (name "Net-(IC12C-IN)") (class "Default")
      (node (ref "IC12") (pin "10") (pinfunction "IN_10") (pintype "input"))
      (node (ref "R100") (pin "2") (pinfunction "2_2") (pintype "passive"))
      (node (ref "R108") (pin "2") (pinfunction "2_2") (pintype "passive"))
    )
    (net (code "128") (name "Net-(IC12C-OUT)") (class "Default")
      (node (ref "C100") (pin "1") (pinfunction "1_1") (pintype "passive"))
      (node (ref "D45") (pin "A") (pinfunction "A_A") (pintype "passive"))
      (node (ref "IC12") (pin "12") (pinfunction "OUT_12") (pintype "output"))
      (node (ref "IC18") (pin "9") (pinfunction "-IN_9") (pintype "input"))
      (node (ref "R160") (pin "2") (pinfunction "2_2") (pintype "passive"))
      (node (ref "R170") (pin "2") (pinfunction "2_2") (pintype "passive"))
      (node (ref "R176") (pin "2") (pinfunction "2_2") (pintype "passive"))
    )
    (net (code "129") (name "Net-(IC12D-IN)") (class "Default")
      (node (ref "IC12") (pin "15") (pinfunction "IN_15") (pintype "input"))
      (node (ref "R92") (pin "2") (pinfunction "2_2") (pintype "passive"))
      (node (ref "R94") (pin "2") (pinfunction "2_2") (pintype "passive"))
    )
    (net (code "130") (name "Net-(IC12D-OUT)") (class "Default")
      (node (ref "C82") (pin "1") (pinfunction "1_1") (pintype "passive"))
      (node (ref "D27") (pin "A") (pinfunction "A_A") (pintype "passive"))
      (node (ref "IC12") (pin "13") (pinfunction "OUT_13") (pintype "output"))
      (node (ref "IC18") (pin "13") (pinfunction "-IN_13") (pintype "input"))
      (node (ref "R143") (pin "2") (pinfunction "2_2") (pintype "passive"))
      (node (ref "R146") (pin "2") (pinfunction "2_2") (pintype "passive"))
      (node (ref "R151") (pin "2") (pinfunction "2_2") (pintype "passive"))
    )
    (net (code "131") (name "Net-(IC12E-MODE)") (class "Default")
      (node (ref "IC12") (pin "1") (pinfunction "MODE_1") (pintype "input"))
      (node (ref "R84") (pin "1") (pinfunction "1_1") (pintype "passive"))
    )
    (net (code "132") (name "Net-(IC13A-CTRL)") (class "Default")
      (node (ref "C83") (pin "2") (pinfunction "2_2") (pintype "passive"))
      (node (ref "D26") (pin "C") (pinfunction "C_C") (pintype "passive"))
      (node (ref "IC13") (pin "14") (pinfunction "CTRL_14") (pintype "input"))
      (node (ref "IC13") (pin "3") (pinfunction "CTRL_3") (pintype "input"))
    )
    (net (code "133") (name "Net-(IC13A-IN)") (class "Default")
      (node (ref "IC13") (pin "2") (pinfunction "IN_2") (pintype "input"))
      (node (ref "R93") (pin "2") (pinfunction "2_2") (pintype "passive"))
      (node (ref "R95") (pin "2") (pinfunction "2_2") (pintype "passive"))
    )
    (net (code "134") (name "Net-(IC13A-OUT)") (class "Default")
      (node (ref "C83") (pin "1") (pinfunction "1_1") (pintype "passive"))
      (node (ref "D28") (pin "A") (pinfunction "A_A") (pintype "passive"))
      (node (ref "IC13") (pin "4") (pinfunction "OUT_4") (pintype "output"))
      (node (ref "IC21") (pin "2") (pinfunction "-IN_2") (pintype "input"))
      (node (ref "R144") (pin "2") (pinfunction "2_2") (pintype "passive"))
      (node (ref "R145") (pin "2") (pinfunction "2_2") (pintype "passive"))
      (node (ref "R152") (pin "2") (pinfunction "2_2") (pintype "passive"))
    )
    (net (code "135") (name "Net-(IC13B-CTRL)") (class "Default")
      (node (ref "C101") (pin "2") (pinfunction "2_2") (pintype "passive"))
      (node (ref "D47") (pin "C") (pinfunction "C_C") (pintype "passive"))
      (node (ref "IC13") (pin "11") (pinfunction "CTRL_11") (pintype "input"))
      (node (ref "IC13") (pin "6") (pinfunction "CTRL_6") (pintype "input"))
    )
    (net (code "136") (name "Net-(IC13B-IN)") (class "Default")
      (node (ref "IC13") (pin "7") (pinfunction "IN_7") (pintype "input"))
      (node (ref "R101") (pin "2") (pinfunction "2_2") (pintype "passive"))
      (node (ref "R109") (pin "2") (pinfunction "2_2") (pintype "passive"))
    )
    (net (code "137") (name "Net-(IC13B-OUT)") (class "Default")
      (node (ref "C101") (pin "1") (pinfunction "1_1") (pintype "passive"))
      (node (ref "D46") (pin "A") (pinfunction "A_A") (pintype "passive"))
      (node (ref "IC13") (pin "5") (pinfunction "OUT_5") (pintype "output"))
      (node (ref "IC21") (pin "6") (pinfunction "-IN_6") (pintype "input"))
      (node (ref "R159") (pin "2") (pinfunction "2_2") (pintype "passive"))
      (node (ref "R169") (pin "2") (pinfunction "2_2") (pintype "passive"))
      (node (ref "R175") (pin "2") (pinfunction "2_2") (pintype "passive"))
    )
    (net (code "138") (name "Net-(IC13C-IN)") (class "Default")
      (node (ref "IC13") (pin "10") (pinfunction "IN_10") (pintype "input"))
      (node (ref "IC13") (pin "13") (pinfunction "OUT_13") (pintype "output"))
      (node (ref "R106") (pin "2") (pinfunction "2_2") (pintype "passive"))
      (node (ref "R107") (pin "2") (pinfunction "2_2") (pintype "passive"))
    )
    (net (code "139") (name "Net-(IC13C-OUT)") (class "Default")
      (node (ref "C87") (pin "1") (pinfunction "1_1") (pintype "passive"))
      (node (ref "D42") (pin "A") (pinfunction "A_A") (pintype "passive"))
      (node (ref "IC13") (pin "12") (pinfunction "OUT_12") (pintype "output"))
      (node (ref "IC21") (pin "13") (pinfunction "-IN_13") (pintype "input"))
      (node (ref "R154") (pin "1") (pinfunction "1_1") (pintype "passive"))
      (node (ref "R174") (pin "2") (pinfunction "2_2") (pintype "passive"))
    )
    (net (code "140") (name "Net-(IC13D-IN)") (class "Default")
      (node (ref "IC13") (pin "15") (pinfunction "IN_15") (pintype "input"))
      (node (ref "R103") (pin "2") (pinfunction "2_2") (pintype "passive"))
      (node (ref "R97") (pin "2") (pinfunction "2_2") (pintype "passive"))
      (node (ref "R99") (pin "2") (pinfunction "2_2") (pintype "passive"))
    )
    (net (code "141") (name "Net-(IC13E-MODE)") (class "Default")
      (node (ref "IC13") (pin "1") (pinfunction "MODE_1") (pintype "input"))
      (node (ref "R85") (pin "1") (pinfunction "1_1") (pintype "passive"))
    )
    (net (code "142") (name "Net-(IC14A--IN)") (class "Default")
      (node (ref "C62") (pin "1") (pinfunction "1_1") (pintype "passive"))
      (node (ref "IC14") (pin "2") (pinfunction "-IN_2") (pintype "input"))
      (node (ref "IC16") (pin "4") (pinfunction "OUT_4") (pintype "output"))
    )
    (net (code "143") (name "Net-(IC14B--IN)") (class "Default")
      (node (ref "IC14") (pin "6") (pinfunction "-IN_6") (pintype "input"))
      (node (ref "R110") (pin "1") (pinfunction "1_1") (pintype "passive"))
      (node (ref "R114") (pin "2") (pinfunction "2_2") (pintype "passive"))
      (node (ref "R115") (pin "1") (pinfunction "1_1") (pintype "passive"))
      (node (ref "R122") (pin "1") (pinfunction "1_1") (pintype "passive"))
    )
    (net (code "144") (name "Net-(IC14C--IN)") (class "Default")
      (node (ref "IC14") (pin "9") (pinfunction "-IN_9") (pintype "input"))
      (node (ref "R111") (pin "2") (pinfunction "2_2") (pintype "passive"))
      (node (ref "R116") (pin "1") (pinfunction "1_1") (pintype "passive"))
      (node (ref "R118") (pin "2") (pinfunction "2_2") (pintype "passive"))
    )
    (net (code "145") (name "Net-(IC14C-OUT)") (class "Default")
      (node (ref "IC14") (pin "8") (pinfunction "OUT_8") (pintype "output"))
      (node (ref "R104") (pin "1") (pinfunction "1_1") (pintype "passive"))
      (node (ref "R116") (pin "2") (pinfunction "2_2") (pintype "passive"))
    )
    (net (code "146") (name "Net-(IC14D--IN)") (class "Default")
      (node (ref "C63") (pin "1") (pinfunction "1_1") (pintype "passive"))
      (node (ref "IC14") (pin "13") (pinfunction "-IN_13") (pintype "input"))
      (node (ref "IC16") (pin "13") (pinfunction "OUT_13") (pintype "output"))
    )
    (net (code "147") (name "Net-(IC15A--IN)") (class "Default")
      (node (ref "C64") (pin "1") (pinfunction "1_1") (pintype "passive"))
      (node (ref "IC15") (pin "2") (pinfunction "-IN_2") (pintype "input"))
      (node (ref "IC17") (pin "4") (pinfunction "OUT_4") (pintype "output"))
    )
    (net (code "148") (name "Net-(IC15B--IN)") (class "Default")
      (node (ref "IC15") (pin "6") (pinfunction "-IN_6") (pintype "input"))
      (node (ref "R112") (pin "2") (pinfunction "2_2") (pintype "passive"))
      (node (ref "R119") (pin "2") (pinfunction "2_2") (pintype "passive"))
      (node (ref "R120") (pin "1") (pinfunction "1_1") (pintype "passive"))
    )
    (net (code "149") (name "Net-(IC15B-OUT)") (class "Default")
      (node (ref "IC15") (pin "7") (pinfunction "OUT_7") (pintype "output"))
      (node (ref "R106") (pin "1") (pinfunction "1_1") (pintype "passive"))
      (node (ref "R120") (pin "2") (pinfunction "2_2") (pintype "passive"))
    )
    (net (code "150") (name "Net-(IC15C--IN)") (class "Default")
      (node (ref "IC15") (pin "9") (pinfunction "-IN_9") (pintype "input"))
      (node (ref "R113") (pin "1") (pinfunction "1_1") (pintype "passive"))
      (node (ref "R117") (pin "1") (pinfunction "1_1") (pintype "passive"))
      (node (ref "R121") (pin "2") (pinfunction "2_2") (pintype "passive"))
      (node (ref "R123") (pin "1") (pinfunction "1_1") (pintype "passive"))
    )
    (net (code "151") (name "Net-(IC15D--IN)") (class "Default")
      (node (ref "C65") (pin "1") (pinfunction "1_1") (pintype "passive"))
      (node (ref "IC15") (pin "13") (pinfunction "-IN_13") (pintype "input"))
      (node (ref "IC17") (pin "13") (pinfunction "OUT_13") (pintype "output"))
    )
    (net (code "152") (name "Net-(IC16A-CTRL)") (class "Default")
      (node (ref "IC16") (pin "14") (pinfunction "CTRL_14") (pintype "input"))
      (node (ref "IC16") (pin "3") (pinfunction "CTRL_3") (pintype "input"))
      (node (ref "R196") (pin "1") (pinfunction "E_1") (pintype "passive"))
      (node (ref "R196") (pin "2") (pinfunction "S_2") (pintype "passive"))
    )
    (net (code "153") (name "Net-(IC16A-IN)") (class "Default")
      (node (ref "D24") (pin "A") (pinfunction "A_A") (pintype "passive"))
      (node (ref "IC16") (pin "2") (pinfunction "IN_2") (pintype "input"))
      (node (ref "IC16") (pin "5") (pinfunction "OUT_5") (pintype "output"))
      (node (ref "R132") (pin "2") (pinfunction "2_2") (pintype "passive"))
      (node (ref "R136") (pin "2") (pinfunction "2_2") (pintype "passive"))
    )
    (net (code "154") (name "Net-(IC16B-CTRL)") (class "Default")
      (node (ref "C91") (pin "2") (pinfunction "2_2") (pintype "passive"))
      (node (ref "D29") (pin "C") (pinfunction "C_C") (pintype "passive"))
      (node (ref "IC16") (pin "6") (pinfunction "CTRL_6") (pintype "input"))
      (node (ref "R148") (pin "2") (pinfunction "2_2") (pintype "passive"))
    )
    (net (code "155") (name "Net-(IC16B-IN)") (class "Default")
      (node (ref "IC16") (pin "7") (pinfunction "IN_7") (pintype "input"))
      (node (ref "R138") (pin "2") (pinfunction "2_2") (pintype "passive"))
      (node (ref "R142") (pin "2") (pinfunction "2_2") (pintype "passive"))
    )
    (net (code "156") (name "Net-(IC16D-IN)") (class "Default")
      (node (ref "C72") (pin "1") (pinfunction "1_1") (pintype "passive"))
      (node (ref "IC16") (pin "15") (pinfunction "IN_15") (pintype "input"))
      (node (ref "R131") (pin "2") (pinfunction "2_2") (pintype "passive"))
      (node (ref "R134") (pin "2") (pinfunction "2_2") (pintype "passive"))
    )
    (net (code "157") (name "Net-(IC16E-MODE)") (class "Default")
      (node (ref "IC16") (pin "1") (pinfunction "MODE_1") (pintype "input"))
      (node (ref "R125") (pin "1") (pinfunction "1_1") (pintype "passive"))
    )
    (net (code "158") (name "Net-(IC17A-CTRL)") (class "Default")
      (node (ref "IC17") (pin "14") (pinfunction "CTRL_14") (pintype "input"))
      (node (ref "IC17") (pin "3") (pinfunction "CTRL_3") (pintype "input"))
      (node (ref "R195") (pin "1") (pinfunction "E_1") (pintype "passive"))
      (node (ref "R195") (pin "2") (pinfunction "S_2") (pintype "passive"))
    )
    (net (code "159") (name "Net-(IC17A-IN)") (class "Default")
      (node (ref "C73") (pin "1") (pinfunction "1_1") (pintype "passive"))
      (node (ref "IC17") (pin "2") (pinfunction "IN_2") (pintype "input"))
      (node (ref "R129") (pin "2") (pinfunction "2_2") (pintype "passive"))
      (node (ref "R135") (pin "2") (pinfunction "2_2") (pintype "passive"))
    )
    (net (code "160") (name "Net-(IC17C-CTRL)") (class "Default")
      (node (ref "C88") (pin "2") (pinfunction "2_2") (pintype "passive"))
      (node (ref "D30") (pin "C") (pinfunction "C_C") (pintype "passive"))
      (node (ref "IC17") (pin "11") (pinfunction "CTRL_11") (pintype "input"))
      (node (ref "R150") (pin "2") (pinfunction "2_2") (pintype "passive"))
    )
    (net (code "161") (name "Net-(IC17C-IN)") (class "Default")
      (node (ref "IC17") (pin "10") (pinfunction "IN_10") (pintype "input"))
      (node (ref "R137") (pin "2") (pinfunction "2_2") (pintype "passive"))
      (node (ref "R141") (pin "2") (pinfunction "2_2") (pintype "passive"))
    )
    (net (code "162") (name "Net-(IC17C-OUT)") (class "Default")
      (node (ref "D23") (pin "A") (pinfunction "A_A") (pintype "passive"))
      (node (ref "IC17") (pin "12") (pinfunction "OUT_12") (pintype "output"))
      (node (ref "IC17") (pin "15") (pinfunction "IN_15") (pintype "input"))
      (node (ref "R126") (pin "2") (pinfunction "2_2") (pintype "passive"))
      (node (ref "R133") (pin "2") (pinfunction "2_2") (pintype "passive"))
    )
    (net (code "163") (name "Net-(IC17E-MODE)") (class "Default")
      (node (ref "IC17") (pin "1") (pinfunction "MODE_1") (pintype "input"))
      (node (ref "R124") (pin "1") (pinfunction "1_1") (pintype "passive"))
    )
    (net (code "164") (name "Net-(IC18B--IN)") (class "Default")
      (node (ref "IC18") (pin "6") (pinfunction "-IN_6") (pintype "input"))
      (node (ref "IC18") (pin "7") (pinfunction "OUT_7") (pintype "output"))
    )
    (net (code "165") (name "Net-(IC18C-OUT)") (class "Default")
      (node (ref "D45") (pin "C") (pinfunction "C_C") (pintype "passive"))
      (node (ref "D48") (pin "A") (pinfunction "A_A") (pintype "passive"))
      (node (ref "IC18") (pin "8") (pinfunction "OUT_8") (pintype "output"))
    )
    (net (code "166") (name "Net-(IC18D-OUT)") (class "Default")
      (node (ref "D25") (pin "A") (pinfunction "A_A") (pintype "passive"))
      (node (ref "D27") (pin "C") (pinfunction "C_C") (pintype "passive"))
      (node (ref "IC18") (pin "14") (pinfunction "OUT_14") (pintype "output"))
    )
    (net (code "167") (name "Net-(IC19A--IN)") (class "Default")
      (node (ref "C90") (pin "1") (pinfunction "1_1") (pintype "passive"))
      (node (ref "D34") (pin "A") (pinfunction "A_A") (pintype "passive"))
      (node (ref "IC19") (pin "2") (pinfunction "-IN_2") (pintype "input"))
      (node (ref "R147") (pin "1") (pinfunction "1_1") (pintype "passive"))
      (node (ref "R156") (pin "2") (pinfunction "2_2") (pintype "passive"))
      (node (ref "R161") (pin "2") (pinfunction "2_2") (pintype "passive"))
      (node (ref "R165") (pin "2") (pinfunction "2_2") (pintype "passive"))
      (node (ref "R177") (pin "P$1") (pinfunction "E_P$1") (pintype "passive"))
    )
    (net (code "168") (name "Net-(IC19A-OUT)") (class "Default")
      (node (ref "D32") (pin "A") (pinfunction "A_A") (pintype "passive"))
      (node (ref "D34") (pin "C") (pinfunction "C_C") (pintype "passive"))
      (node (ref "IC19") (pin "1") (pinfunction "OUT_1") (pintype "output"))
    )
    (net (code "169") (name "Net-(IC19B--IN)") (class "Default")
      (node (ref "IC19") (pin "6") (pinfunction "-IN_6") (pintype "input"))
      (node (ref "R166") (pin "1") (pinfunction "1_1") (pintype "passive"))
      (node (ref "R177") (pin "P$3") (pinfunction "A_P$3") (pintype "passive"))
    )
    (net (code "170") (name "Net-(IC19B-OUT)") (class "Default")
      (node (ref "IC19") (pin "7") (pinfunction "OUT_7") (pintype "output"))
      (node (ref "R165") (pin "1") (pinfunction "1_1") (pintype "passive"))
      (node (ref "R166") (pin "2") (pinfunction "2_2") (pintype "passive"))
    )
    (net (code "171") (name "Net-(IC19C--IN)") (class "Default")
      (node (ref "IC19") (pin "9") (pinfunction "-IN_9") (pintype "input"))
      (node (ref "R167") (pin "1") (pinfunction "1_1") (pintype "passive"))
      (node (ref "R178") (pin "P$1") (pinfunction "E_P$1") (pintype "passive"))
    )
    (net (code "172") (name "Net-(IC19C-OUT)") (class "Default")
      (node (ref "IC19") (pin "8") (pinfunction "OUT_8") (pintype "output"))
      (node (ref "R164") (pin "1") (pinfunction "1_1") (pintype "passive"))
      (node (ref "R167") (pin "2") (pinfunction "2_2") (pintype "passive"))
    )
    (net (code "173") (name "Net-(IC19D--IN)") (class "Default")
      (node (ref "C91") (pin "1") (pinfunction "1_1") (pintype "passive"))
      (node (ref "D35") (pin "A") (pinfunction "A_A") (pintype "passive"))
      (node (ref "IC19") (pin "13") (pinfunction "-IN_13") (pintype "input"))
      (node (ref "R148") (pin "1") (pinfunction "1_1") (pintype "passive"))
      (node (ref "R155") (pin "2") (pinfunction "2_2") (pintype "passive"))
      (node (ref "R164") (pin "2") (pinfunction "2_2") (pintype "passive"))
      (node (ref "R178") (pin "P$3") (pinfunction "A_P$3") (pintype "passive"))
    )
    (net (code "174") (name "Net-(IC19D-OUT)") (class "Default")
      (node (ref "D29") (pin "A") (pinfunction "A_A") (pintype "passive"))
      (node (ref "D35") (pin "C") (pinfunction "C_C") (pintype "passive"))
      (node (ref "IC19") (pin "14") (pinfunction "OUT_14") (pintype "output"))
    )
    (net (code "175") (name "Net-(IC20A--IN)") (class "Default")
      (node (ref "C88") (pin "1") (pinfunction "1_1") (pintype "passive"))
      (node (ref "D33") (pin "A") (pinfunction "A_A") (pintype "passive"))
      (node (ref "IC20") (pin "2") (pinfunction "-IN_2") (pintype "input"))
      (node (ref "R150") (pin "1") (pinfunction "1_1") (pintype "passive"))
      (node (ref "R157") (pin "2") (pinfunction "2_2") (pintype "passive"))
      (node (ref "R168") (pin "2") (pinfunction "2_2") (pintype "passive"))
      (node (ref "R180") (pin "P$3") (pinfunction "A_P$3") (pintype "passive"))
    )
    (net (code "176") (name "Net-(IC20A-OUT)") (class "Default")
      (node (ref "D30") (pin "A") (pinfunction "A_A") (pintype "passive"))
      (node (ref "D33") (pin "C") (pinfunction "C_C") (pintype "passive"))
      (node (ref "IC20") (pin "1") (pinfunction "OUT_1") (pintype "output"))
    )
    (net (code "177") (name "Net-(IC20B--IN)") (class "Default")
      (node (ref "IC20") (pin "6") (pinfunction "-IN_6") (pintype "input"))
      (node (ref "R171") (pin "1") (pinfunction "1_1") (pintype "passive"))
      (node (ref "R180") (pin "P$1") (pinfunction "E_P$1") (pintype "passive"))
    )
    (net (code "178") (name "Net-(IC20B-OUT)") (class "Default")
      (node (ref "IC20") (pin "7") (pinfunction "OUT_7") (pintype "output"))
      (node (ref "R168") (pin "1") (pinfunction "1_1") (pintype "passive"))
      (node (ref "R171") (pin "2") (pinfunction "2_2") (pintype "passive"))
    )
    (net (code "179") (name "Net-(IC20C--IN)") (class "Default")
      (node (ref "IC20") (pin "9") (pinfunction "-IN_9") (pintype "input"))
      (node (ref "R163") (pin "1") (pinfunction "1_1") (pintype "passive"))
      (node (ref "R181") (pin "P$3") (pinfunction "A_P$3") (pintype "passive"))
      (node (ref "SW1") (pin "P2") (pinfunction "A2_P2") (pintype "passive"))
    )
    (net (code "180") (name "Net-(IC20C-OUT)") (class "Default")
      (node (ref "IC20") (pin "8") (pinfunction "OUT_8") (pintype "output"))
      (node (ref "R163") (pin "2") (pinfunction "2_2") (pintype "passive"))
      (node (ref "R172") (pin "1") (pinfunction "1_1") (pintype "passive"))
    )
    (net (code "181") (name "Net-(IC20D--IN)") (class "Default")
      (node (ref "C89") (pin "1") (pinfunction "1_1") (pintype "passive"))
      (node (ref "D36") (pin "A") (pinfunction "A_A") (pintype "passive"))
      (node (ref "IC20") (pin "13") (pinfunction "-IN_13") (pintype "input"))
      (node (ref "R149") (pin "1") (pinfunction "1_1") (pintype "passive"))
      (node (ref "R158") (pin "2") (pinfunction "2_2") (pintype "passive"))
      (node (ref "R162") (pin "2") (pinfunction "2_2") (pintype "passive"))
      (node (ref "R172") (pin "2") (pinfunction "2_2") (pintype "passive"))
      (node (ref "R181") (pin "P$1") (pinfunction "E_P$1") (pintype "passive"))
    )
    (net (code "182") (name "Net-(IC20D-OUT)") (class "Default")
      (node (ref "D31") (pin "A") (pinfunction "A_A") (pintype "passive"))
      (node (ref "D36") (pin "C") (pinfunction "C_C") (pintype "passive"))
      (node (ref "IC20") (pin "14") (pinfunction "OUT_14") (pintype "output"))
    )
    (net (code "183") (name "Net-(IC21A-OUT)") (class "Default")
      (node (ref "D26") (pin "A") (pinfunction "A_A") (pintype "passive"))
      (node (ref "D28") (pin "C") (pinfunction "C_C") (pintype "passive"))
      (node (ref "IC21") (pin "1") (pinfunction "OUT_1") (pintype "output"))
    )
    (net (code "184") (name "Net-(IC21B-OUT)") (class "Default")
      (node (ref "D46") (pin "C") (pinfunction "C_C") (pintype "passive"))
      (node (ref "D47") (pin "A") (pinfunction "A_A") (pintype "passive"))
      (node (ref "IC21") (pin "7") (pinfunction "OUT_7") (pintype "output"))
    )
    (net (code "185") (name "Net-(IC21C--IN)") (class "Default")
      (node (ref "IC21") (pin "8") (pinfunction "OUT_8") (pintype "output"))
      (node (ref "IC21") (pin "9") (pinfunction "-IN_9") (pintype "input"))
    )
    (net (code "186") (name "Net-(J3-2)") (class "Default")
      (node (ref "J3") (pin "P2") (pinfunction "2_P2") (pintype "passive"))
      (node (ref "R182") (pin "1") (pinfunction "1_1") (pintype "passive"))
    )
    (net (code "187") (name "Net-(J4-2)") (class "Default")
      (node (ref "J4") (pin "P2") (pinfunction "2_P2") (pintype "passive"))
      (node (ref "R184") (pin "2") (pinfunction "2_2") (pintype "passive"))
    )
    (net (code "188") (name "Net-(J8-2)") (class "Default")
      (node (ref "J8") (pin "P2") (pinfunction "2_P2") (pintype "passive"))
      (node (ref "R188") (pin "2") (pinfunction "2_2") (pintype "passive"))
    )
    (net (code "189") (name "Net-(J9-2)") (class "Default")
      (node (ref "J9") (pin "P2") (pinfunction "2_P2") (pintype "passive"))
      (node (ref "R190") (pin "1") (pinfunction "1_1") (pintype "passive"))
    )
    (net (code "190") (name "Net-(J12-3)") (class "Default")
      (node (ref "J12") (pin "P3") (pinfunction "3_P3") (pintype "passive"))
      (node (ref "R191") (pin "2") (pinfunction "2_2") (pintype "passive"))
    )
    (net (code "191") (name "Net-(J13-3)") (class "Default")
      (node (ref "J13") (pin "P3") (pinfunction "3_P3") (pintype "passive"))
      (node (ref "R192") (pin "2") (pinfunction "2_2") (pintype "passive"))
    )
    (net (code "192") (name "Net-(J14-3)") (class "Default")
      (node (ref "J14") (pin "P3") (pinfunction "3_P3") (pintype "passive"))
      (node (ref "R193") (pin "2") (pinfunction "2_2") (pintype "passive"))
    )
    (net (code "193") (name "Net-(JP1-Pad1)") (class "Default")
      (node (ref "JP1") (pin "1") (pinfunction "1_1") (pintype "passive"))
      (node (ref "JP1") (pin "2") (pinfunction "2_2") (pintype "passive"))
      (node (ref "P1") (pin "2") (pinfunction "2_2") (pintype "bidirectional"))
    )
    (net (code "194") (name "Net-(L1-Pad2)") (class "Default")
      (node (ref "L1") (pin "2") (pinfunction "2_2") (pintype "passive"))
      (node (ref "P1") (pin "1") (pinfunction "1_1") (pintype "bidirectional"))
    )
    (net (code "195") (name "Net-(R14-S)") (class "Default")
      (node (ref "R14") (pin "P$2") (pinfunction "S_P$2") (pintype "passive"))
      (node (ref "R155") (pin "1") (pinfunction "1_1") (pintype "passive"))
    )
    (net (code "196") (name "Net-(R15-S)") (class "Default")
      (node (ref "R15") (pin "P$2") (pinfunction "S_P$2") (pintype "passive"))
      (node (ref "R157") (pin "1") (pinfunction "1_1") (pintype "passive"))
    )
    (net (code "197") (name "Net-(R17-S)") (class "Default")
      (node (ref "R11") (pin "1") (pinfunction "1_1") (pintype "passive"))
      (node (ref "R17") (pin "P$2") (pinfunction "S_P$2") (pintype "passive"))
    )
    (net (code "198") (name "Net-(R18-S)") (class "Default")
      (node (ref "R13") (pin "1") (pinfunction "1_1") (pintype "passive"))
      (node (ref "R18") (pin "P$2") (pinfunction "S_P$2") (pintype "passive"))
    )
    (net (code "199") (name "Net-(R75-Pad2)") (class "Default")
      (node (ref "R75") (pin "2") (pinfunction "2_2") (pintype "passive"))
      (node (ref "SW1") (pin "L1") (pinfunction "L1_L1") (pintype "passive"))
    )
    (net (code "200") (name "Net-(R80-A)") (class "Default")
      (node (ref "R3") (pin "1") (pinfunction "1_1") (pintype "passive"))
      (node (ref "R80") (pin "P$3") (pinfunction "A_P$3") (pintype "passive"))
      (node (ref "R88") (pin "2") (pinfunction "2_2") (pintype "passive"))
    )
    (net (code "201") (name "Net-(R80-E)") (class "Default")
      (node (ref "R10") (pin "1") (pinfunction "1_1") (pintype "passive"))
      (node (ref "R80") (pin "P$1") (pinfunction "E_P$1") (pintype "passive"))
      (node (ref "R89") (pin "2") (pinfunction "2_2") (pintype "passive"))
    )
    (net (code "202") (name "Net-(R81-A)") (class "Default")
      (node (ref "R81") (pin "P$3") (pinfunction "A_P$3") (pintype "passive"))
      (node (ref "R9") (pin "1") (pinfunction "1_1") (pintype "passive"))
      (node (ref "R90") (pin "2") (pinfunction "2_2") (pintype "passive"))
    )
    (net (code "203") (name "Net-(R81-E)") (class "Default")
      (node (ref "R4") (pin "1") (pinfunction "1_1") (pintype "passive"))
      (node (ref "R81") (pin "P$1") (pinfunction "E_P$1") (pintype "passive"))
      (node (ref "R91") (pin "2") (pinfunction "2_2") (pintype "passive"))
    )
    (net (code "204") (name "Net-(R86-S)") (class "Default")
      (node (ref "R156") (pin "1") (pinfunction "1_1") (pintype "passive"))
      (node (ref "R86") (pin "P$2") (pinfunction "S_P$2") (pintype "passive"))
    )
    (net (code "205") (name "Net-(R87-S)") (class "Default")
      (node (ref "R158") (pin "1") (pinfunction "1_1") (pintype "passive"))
      (node (ref "R87") (pin "P$2") (pinfunction "S_P$2") (pintype "passive"))
    )
    (net (code "206") (name "Net-(R128-S)") (class "Default")
      (node (ref "R128") (pin "P$2") (pinfunction "S_P$2") (pintype "passive"))
      (node (ref "R29") (pin "1") (pinfunction "1_1") (pintype "passive"))
    )
    (net (code "207") (name "Net-(R139-E)") (class "Default")
      (node (ref "R139") (pin "1") (pinfunction "E_1") (pintype "passive"))
      (node (ref "R139") (pin "2") (pinfunction "S_2") (pintype "passive"))
      (node (ref "R77") (pin "1") (pinfunction "1_1") (pintype "passive"))
    )
    (net (code "208") (name "Net-(R177-S)") (class "Default")
      (node (ref "R177") (pin "P$2") (pinfunction "S_P$2") (pintype "passive"))
      (node (ref "R183") (pin "2") (pinfunction "2_2") (pintype "passive"))
    )
    (net (code "209") (name "Net-(R178-S)") (class "Default")
      (node (ref "R178") (pin "P$2") (pinfunction "S_P$2") (pintype "passive"))
      (node (ref "R185") (pin "2") (pinfunction "2_2") (pintype "passive"))
    )
    (net (code "210") (name "Net-(R179-S)") (class "Default")
      (node (ref "R179") (pin "P$2") (pinfunction "S_P$2") (pintype "passive"))
      (node (ref "R186") (pin "2") (pinfunction "2_2") (pintype "passive"))
    )
    (net (code "211") (name "Net-(R180-S)") (class "Default")
      (node (ref "R180") (pin "P$2") (pinfunction "S_P$2") (pintype "passive"))
      (node (ref "R187") (pin "2") (pinfunction "2_2") (pintype "passive"))
    )
    (net (code "212") (name "Net-(R181-S)") (class "Default")
      (node (ref "R181") (pin "P$2") (pinfunction "S_P$2") (pintype "passive"))
      (node (ref "R189") (pin "2") (pinfunction "2_2") (pintype "passive"))
    )
    (net (code "213") (name "Net-(R195-A)") (class "Default")
      (node (ref "C89") (pin "2") (pinfunction "2_2") (pintype "passive"))
      (node (ref "D31") (pin "C") (pinfunction "C_C") (pintype "passive"))
      (node (ref "R149") (pin "2") (pinfunction "2_2") (pintype "passive"))
      (node (ref "R195") (pin "3") (pinfunction "A_3") (pintype "passive"))
    )
    (net (code "214") (name "Net-(R198-E)") (class "Default")
      (node (ref "R198") (pin "1") (pinfunction "E_1") (pintype "passive"))
      (node (ref "R198") (pin "2") (pinfunction "S_2") (pintype "passive"))
      (node (ref "R76") (pin "1") (pinfunction "1_1") (pintype "passive"))
    )
    (net (code "215") (name "Net-(SW1B-A1)") (class "Default")
      (node (ref "R63") (pin "1") (pinfunction "1_1") (pintype "passive"))
      (node (ref "SW1") (pin "P1") (pinfunction "A1_P1") (pintype "passive"))
    )
    (net (code "216") (name "Net-(SW1B-A3)") (class "Default")
      (node (ref "R54") (pin "2") (pinfunction "2_2") (pintype "passive"))
      (node (ref "R62") (pin "2") (pinfunction "2_2") (pintype "passive"))
      (node (ref "SW1") (pin "P3") (pinfunction "A3_P3") (pintype "passive"))
    )
    (net (code "217") (name "Net-(SW1B-B2)") (class "Default")
      (node (ref "R75") (pin "1") (pinfunction "1_1") (pintype "passive"))
      (node (ref "SW1") (pin "P5") (pinfunction "B2_P5") (pintype "passive"))
    )
    (net (code "218") (name "OUT") (class "Default")
      (node (ref "C32") (pin "2") (pinfunction "2_2") (pintype "passive"))
      (node (ref "IC8") (pin "14") (pinfunction "OUT_14") (pintype "output"))
      (node (ref "R192") (pin "1") (pinfunction "1_1") (pintype "passive"))
      (node (ref "R69") (pin "2") (pinfunction "2_2") (pintype "passive"))
    )
    (net (code "219") (name "OUT_1") (class "Default")
      (node (ref "C86") (pin "2") (pinfunction "2_2") (pintype "passive"))
      (node (ref "D38") (pin "A") (pinfunction "A_A") (pintype "passive"))
      (node (ref "IC18") (pin "1") (pinfunction "OUT_1") (pintype "output"))
      (node (ref "R153") (pin "2") (pinfunction "2_2") (pintype "passive"))
      (node (ref "R188") (pin "1") (pinfunction "1_1") (pintype "passive"))
      (node (ref "R191") (pin "1") (pinfunction "1_1") (pintype "passive"))
      (node (ref "R198") (pin "3") (pinfunction "A_3") (pintype "passive"))
      (node (ref "R71") (pin "1") (pinfunction "1_1") (pintype "passive"))
    )
    (net (code "220") (name "OUT_2") (class "Default")
      (node (ref "C87") (pin "2") (pinfunction "2_2") (pintype "passive"))
      (node (ref "D37") (pin "A") (pinfunction "A_A") (pintype "passive"))
      (node (ref "IC21") (pin "14") (pinfunction "OUT_14") (pintype "output"))
      (node (ref "R139") (pin "3") (pinfunction "A_3") (pintype "passive"))
      (node (ref "R154") (pin "2") (pinfunction "2_2") (pintype "passive"))
      (node (ref "R184") (pin "1") (pinfunction "1_1") (pintype "passive"))
      (node (ref "R193") (pin "1") (pinfunction "1_1") (pintype "passive"))
      (node (ref "R44") (pin "1") (pinfunction "1_1") (pintype "passive"))
    )
    (net (code "221") (name "RAW_IN_1") (class "Default")
      (node (ref "D49") (pin "2") (pinfunction "C_2") (pintype "passive"))
      (node (ref "J10") (pin "P3") (pinfunction "3_P3") (pintype "passive"))
      (node (ref "R33") (pin "1") (pinfunction "1_1") (pintype "passive"))
      (node (ref "R78") (pin "1") (pinfunction "1_1") (pintype "passive"))
    )
    (net (code "222") (name "VCC") (class "Default")
      (node (ref "C14") (pin "1") (pinfunction "1_1") (pintype "passive"))
      (node (ref "C15") (pin "1") (pinfunction "1_1") (pintype "passive"))
      (node (ref "C17") (pin "1") (pinfunction "1_1") (pintype "passive"))
      (node (ref "C2") (pin "1") (pinfunction "1_1") (pintype "passive"))
      (node (ref "C27") (pin "1") (pinfunction "1_1") (pintype "passive"))
      (node (ref "C29") (pin "1") (pinfunction "1_1") (pintype "passive"))
      (node (ref "C36") (pin "1") (pinfunction "1_1") (pintype "passive"))
      (node (ref "C37") (pin "1") (pinfunction "1_1") (pintype "passive"))
      (node (ref "C44") (pin "1") (pinfunction "1_1") (pintype "passive"))
      (node (ref "C45") (pin "1") (pinfunction "1_1") (pintype "passive"))
      (node (ref "C46") (pin "1") (pinfunction "1_1") (pintype "passive"))
      (node (ref "C47") (pin "1") (pinfunction "1_1") (pintype "passive"))
      (node (ref "C55") (pin "+") (pinfunction "+_+") (pintype "passive"))
      (node (ref "C66") (pin "1") (pinfunction "1_1") (pintype "passive"))
      (node (ref "C68") (pin "1") (pinfunction "1_1") (pintype "passive"))
      (node (ref "C70") (pin "1") (pinfunction "1_1") (pintype "passive"))
      (node (ref "C71") (pin "1") (pinfunction "1_1") (pintype "passive"))
      (node (ref "C8") (pin "1") (pinfunction "1_1") (pintype "passive"))
      (node (ref "C92") (pin "1") (pinfunction "1_1") (pintype "passive"))
      (node (ref "C94") (pin "1") (pinfunction "1_1") (pintype "passive"))
      (node (ref "C96") (pin "1") (pinfunction "1_1") (pintype "passive"))
      (node (ref "C98") (pin "1") (pinfunction "1_1") (pintype "passive"))
      (node (ref "IC1") (pin "4") (pinfunction "V+_4") (pintype "power_in"))
      (node (ref "IC12") (pin "16") (pinfunction "V+_16") (pintype "power_in"))
      (node (ref "IC13") (pin "16") (pinfunction "V+_16") (pintype "power_in"))
      (node (ref "IC14") (pin "4") (pinfunction "V+_4") (pintype "power_in"))
      (node (ref "IC15") (pin "4") (pinfunction "V+_4") (pintype "power_in"))
      (node (ref "IC16") (pin "16") (pinfunction "V+_16") (pintype "power_in"))
      (node (ref "IC17") (pin "16") (pinfunction "V+_16") (pintype "power_in"))
      (node (ref "IC18") (pin "4") (pinfunction "V+_4") (pintype "power_in"))
      (node (ref "IC19") (pin "4") (pinfunction "V+_4") (pintype "power_in"))
      (node (ref "IC2") (pin "4") (pinfunction "V+_4") (pintype "power_in"))
      (node (ref "IC20") (pin "4") (pinfunction "V+_4") (pintype "power_in"))
      (node (ref "IC21") (pin "4") (pinfunction "V+_4") (pintype "power_in"))
      (node (ref "IC3") (pin "4") (pinfunction "V+_4") (pintype "power_in"))
      (node (ref "IC4") (pin "16") (pinfunction "V+_16") (pintype "power_in"))
      (node (ref "IC5") (pin "16") (pinfunction "V+_16") (pintype "power_in"))
      (node (ref "IC6") (pin "8") (pinfunction "V+_8") (pintype "power_in"))
      (node (ref "IC7") (pin "8") (pinfunction "V+_8") (pintype "power_in"))
      (node (ref "IC8") (pin "4") (pinfunction "V+_4") (pintype "power_in"))
      (node (ref "IC9") (pin "8") (pinfunction "V+_8") (pintype "power_in"))
      (node (ref "L2") (pin "1") (pinfunction "1_1") (pintype "passive"))
      (node (ref "R124") (pin "2") (pinfunction "2_2") (pintype "passive"))
      (node (ref "R125") (pin "2") (pinfunction "2_2") (pintype "passive"))
      (node (ref "R30") (pin "2") (pinfunction "2_2") (pintype "passive"))
      (node (ref "R31") (pin "2") (pinfunction "2_2") (pintype "passive"))
      (node (ref "R83") (pin "1") (pinfunction "1_1") (pintype "passive"))
      (node (ref "R84") (pin "2") (pinfunction "2_2") (pintype "passive"))
      (node (ref "R85") (pin "2") (pinfunction "2_2") (pintype "passive"))
      (node (ref "SW1") (pin "P6") (pinfunction "B3_P6") (pintype "passive"))
    )
    (net (code "223") (name "VEE") (class "Default")
      (node (ref "C1") (pin "2") (pinfunction "2_2") (pintype "passive"))
      (node (ref "C16") (pin "2") (pinfunction "2_2") (pintype "passive"))
      (node (ref "C30") (pin "2") (pinfunction "2_2") (pintype "passive"))
      (node (ref "C31") (pin "2") (pinfunction "2_2") (pintype "passive"))
      (node (ref "C34") (pin "2") (pinfunction "2_2") (pintype "passive"))
      (node (ref "C35") (pin "2") (pinfunction "2_2") (pintype "passive"))
      (node (ref "C40") (pin "2") (pinfunction "2_2") (pintype "passive"))
      (node (ref "C41") (pin "2") (pinfunction "2_2") (pintype "passive"))
      (node (ref "C52") (pin "2") (pinfunction "2_2") (pintype "passive"))
      (node (ref "C53") (pin "2") (pinfunction "2_2") (pintype "passive"))
      (node (ref "C54") (pin "-") (pinfunction "-_-") (pintype "passive"))
      (node (ref "C58") (pin "2") (pinfunction "2_2") (pintype "passive"))
      (node (ref "C59") (pin "2") (pinfunction "2_2") (pintype "passive"))
      (node (ref "C67") (pin "2") (pinfunction "2_2") (pintype "passive"))
      (node (ref "C69") (pin "2") (pinfunction "2_2") (pintype "passive"))
      (node (ref "C7") (pin "2") (pinfunction "2_2") (pintype "passive"))
      (node (ref "C84") (pin "2") (pinfunction "2_2") (pintype "passive"))
      (node (ref "C85") (pin "2") (pinfunction "2_2") (pintype "passive"))
      (node (ref "C93") (pin "2") (pinfunction "2_2") (pintype "passive"))
      (node (ref "C95") (pin "2") (pinfunction "2_2") (pintype "passive"))
      (node (ref "C97") (pin "2") (pinfunction "2_2") (pintype "passive"))
      (node (ref "C99") (pin "2") (pinfunction "2_2") (pintype "passive"))
      (node (ref "D20") (pin "A") (pinfunction "A_A") (pintype "passive"))
      (node (ref "IC1") (pin "11") (pinfunction "V-_11") (pintype "power_in"))
      (node (ref "IC12") (pin "9") (pinfunction "V-_9") (pintype "power_in"))
      (node (ref "IC13") (pin "9") (pinfunction "V-_9") (pintype "power_in"))
      (node (ref "IC14") (pin "11") (pinfunction "V-_11") (pintype "power_in"))
      (node (ref "IC15") (pin "11") (pinfunction "V-_11") (pintype "power_in"))
      (node (ref "IC16") (pin "9") (pinfunction "V-_9") (pintype "power_in"))
      (node (ref "IC17") (pin "9") (pinfunction "V-_9") (pintype "power_in"))
      (node (ref "IC18") (pin "11") (pinfunction "V-_11") (pintype "power_in"))
      (node (ref "IC19") (pin "11") (pinfunction "V-_11") (pintype "power_in"))
      (node (ref "IC2") (pin "11") (pinfunction "V-_11") (pintype "power_in"))
      (node (ref "IC20") (pin "11") (pinfunction "V-_11") (pintype "power_in"))
      (node (ref "IC21") (pin "11") (pinfunction "V-_11") (pintype "power_in"))
      (node (ref "IC3") (pin "11") (pinfunction "V-_11") (pintype "power_in"))
      (node (ref "IC4") (pin "9") (pinfunction "V-_9") (pintype "power_in"))
      (node (ref "IC5") (pin "9") (pinfunction "V-_9") (pintype "power_in"))
      (node (ref "IC6") (pin "4") (pinfunction "V-_4") (pintype "power_in"))
      (node (ref "IC7") (pin "4") (pinfunction "V-_4") (pintype "power_in"))
      (node (ref "IC8") (pin "11") (pinfunction "V-_11") (pintype "power_in"))
      (node (ref "IC9") (pin "4") (pinfunction "V-_4") (pintype "power_in"))
      (node (ref "L1") (pin "1") (pinfunction "1_1") (pintype "passive"))
      (node (ref "R82") (pin "1") (pinfunction "1_1") (pintype "passive"))
    )
    (net (code "224") (name "unconnected-(IC16C-CTRL-Pad11)") (class "Default")
      (node (ref "IC16") (pin "11") (pinfunction "CTRL_11") (pintype "input"))
    )
    (net (code "225") (name "unconnected-(IC17B-CTRL-Pad6)") (class "Default")
      (node (ref "IC17") (pin "6") (pinfunction "CTRL_6") (pintype "input"))
    )
    (net (code "226") (name "unconnected-(J12-2-PadP2)") (class "Default")
      (node (ref "J12") (pin "P2") (pinfunction "2_P2") (pintype "passive"))
    )
    (net (code "227") (name "unconnected-(J13-2-PadP2)") (class "Default")
      (node (ref "J13") (pin "P2") (pinfunction "2_P2") (pintype "passive"))
    )
    (net (code "228") (name "unconnected-(J14-2-PadP2)") (class "Default")
      (node (ref "J14") (pin "P2") (pinfunction "2_P2") (pintype "passive"))
    )
    (net (code "229") (name "unconnected-(SW1B-B1-PadP4)") (class "Default")
      (node (ref "SW1") (pin "P4") (pinfunction "B1_P4") (pintype "passive"))
    )
    (net (code "230") (name "~{OUT_1}") (class "Default")
      (node (ref "IC9") (pin "1") (pinfunction "OUT_1") (pintype "output"))
      (node (ref "R197") (pin "2") (pinfunction "2_2") (pintype "passive"))
      (node (ref "R46") (pin "1") (pinfunction "1_1") (pintype "passive"))
      (node (ref "R70") (pin "1") (pinfunction "1_1") (pintype "passive"))
      (node (ref "R72") (pin "2") (pinfunction "2_2") (pintype "passive"))
    )
    (net (code "231") (name "~{TOPOLOGY_CV}") (class "Default")
      (node (ref "C11") (pin "2") (pinfunction "2_2") (pintype "passive"))
      (node (ref "IC3") (pin "1") (pinfunction "OUT_1") (pintype "output"))
      (node (ref "R16") (pin "2") (pinfunction "2_2") (pintype "passive"))
      (node (ref "R42") (pin "1") (pinfunction "1_1") (pintype "passive"))
      (node (ref "R43") (pin "1") (pinfunction "1_1") (pintype "passive"))
    )
  )
)
